# BeagleBone_Black_Wireless.net
KiCad netlist of a schematic drawn in EAGLE
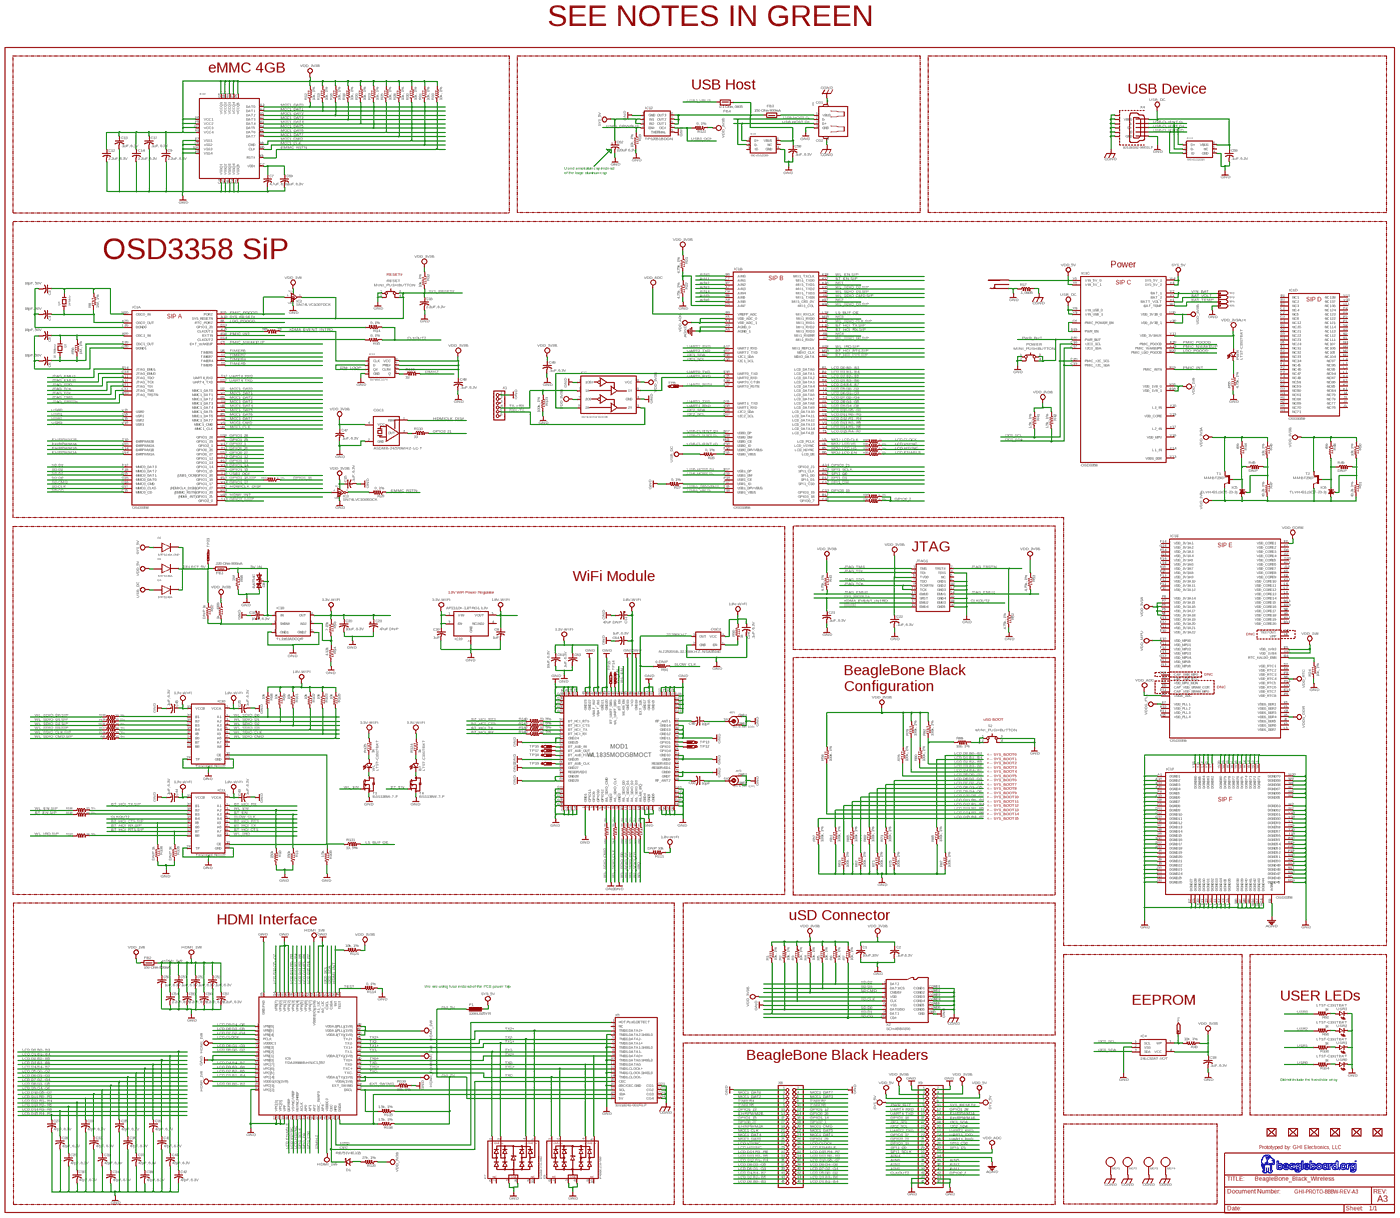
[diagram p0: schematic, sheet 1, overview]
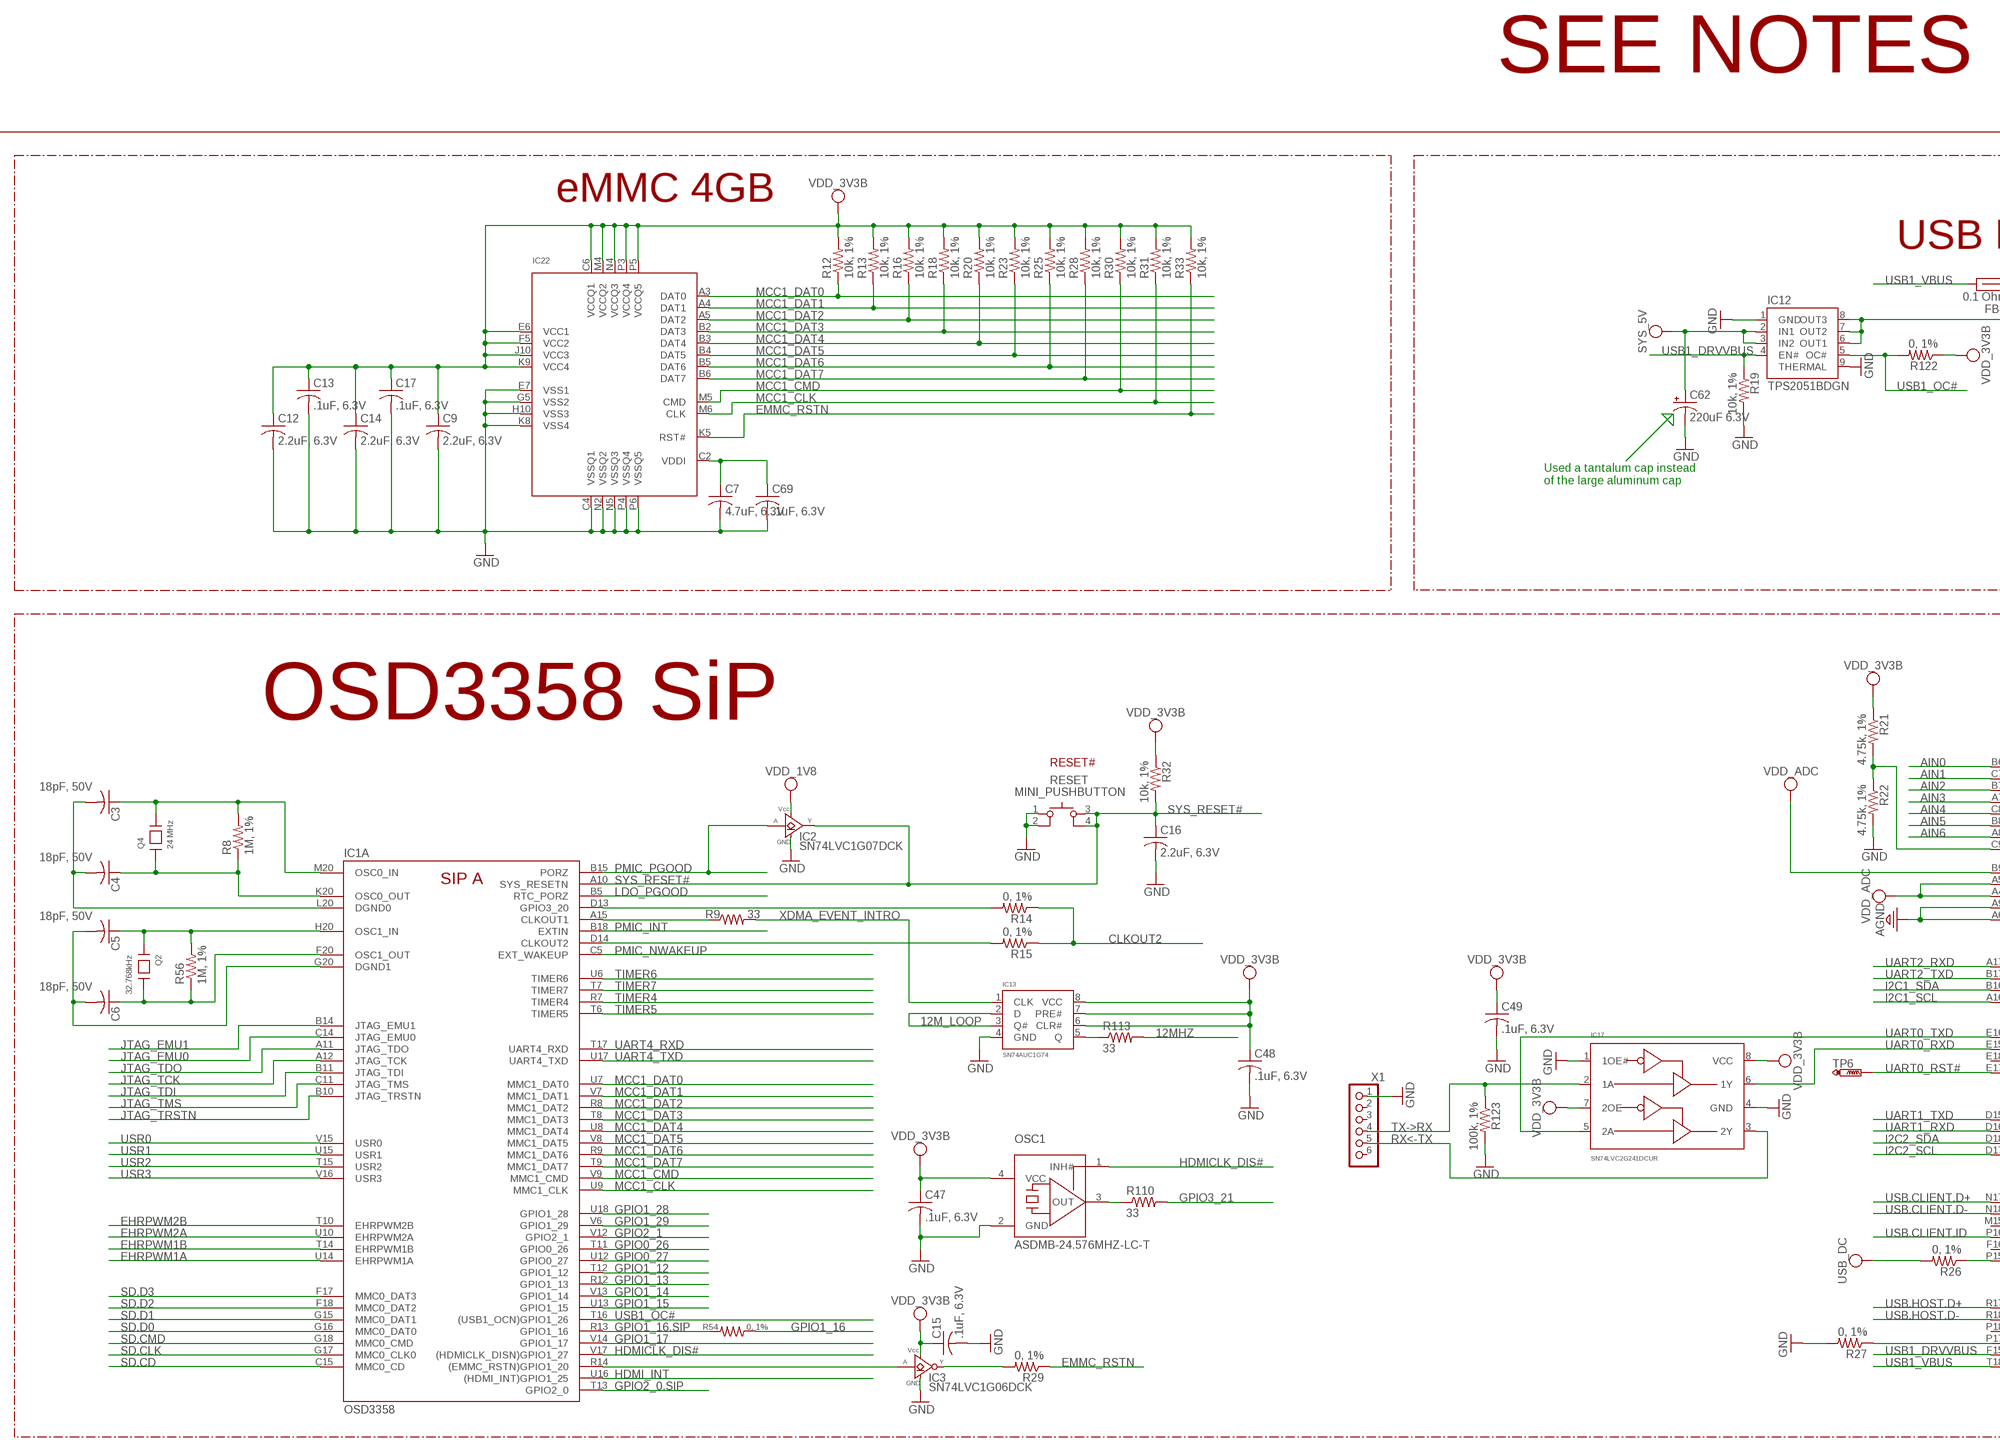
[diagram p1: schematic, sheet 1, part 1 of 4]
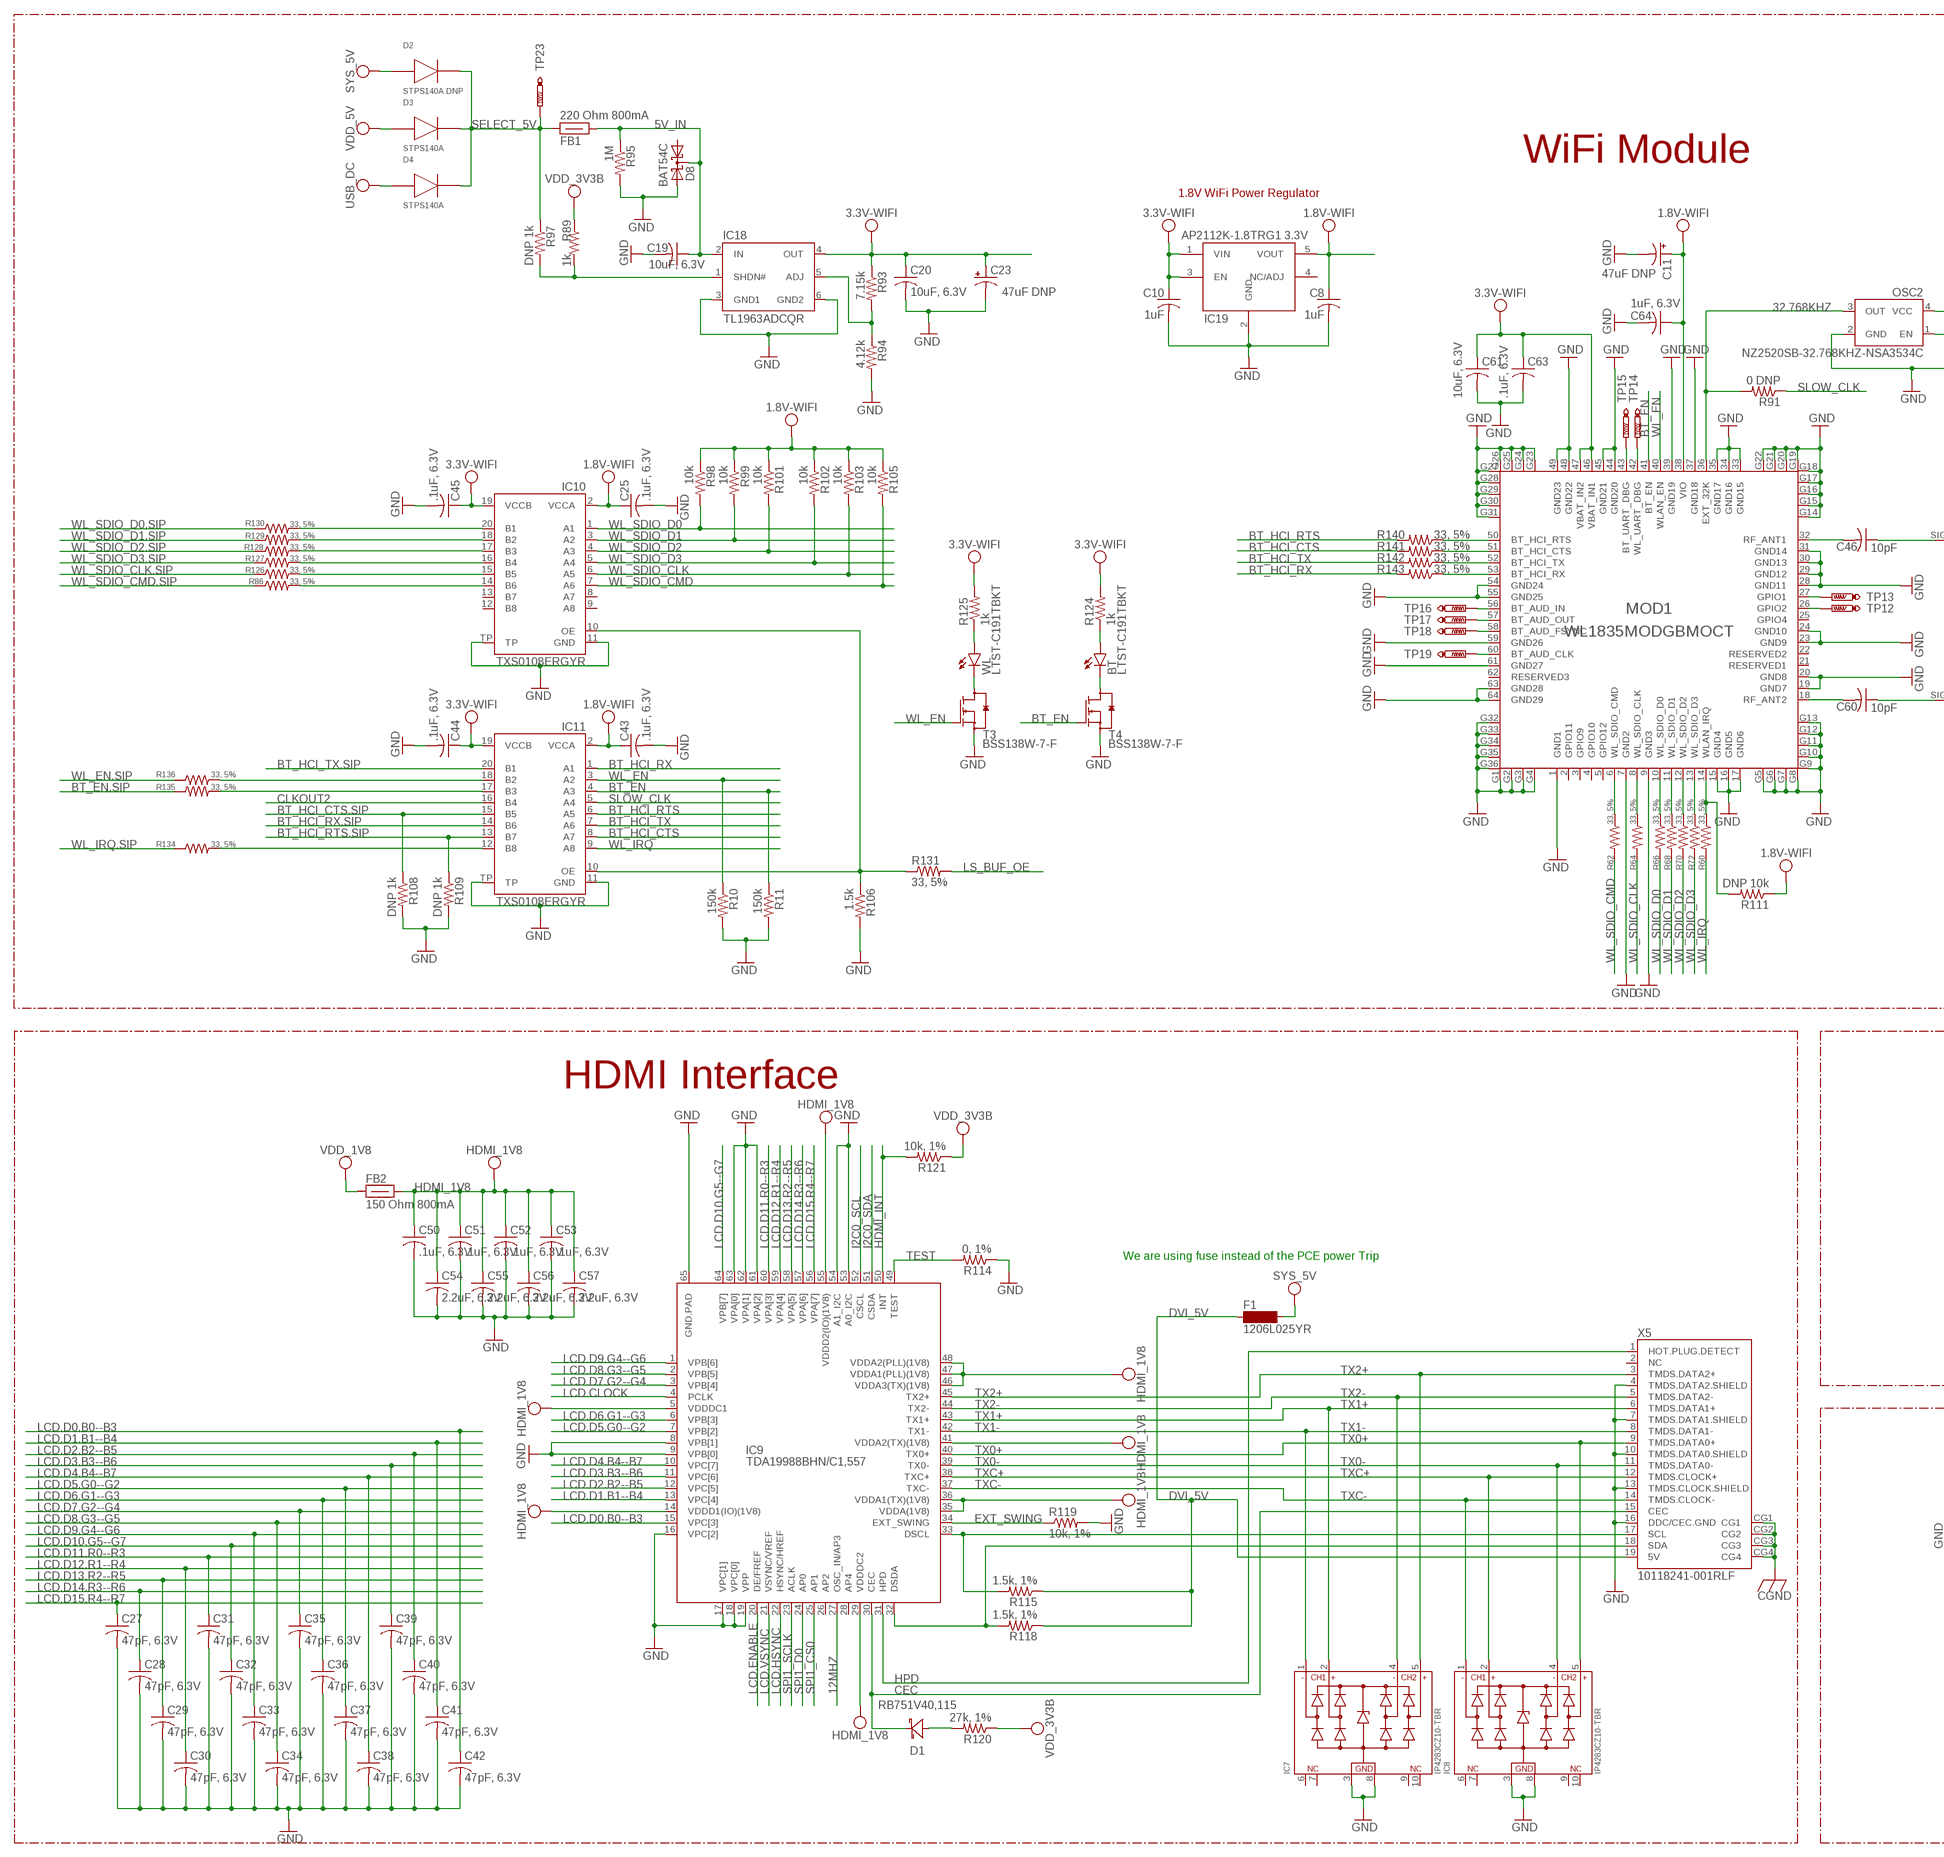
[diagram p2: schematic, sheet 1, part 2 of 4]
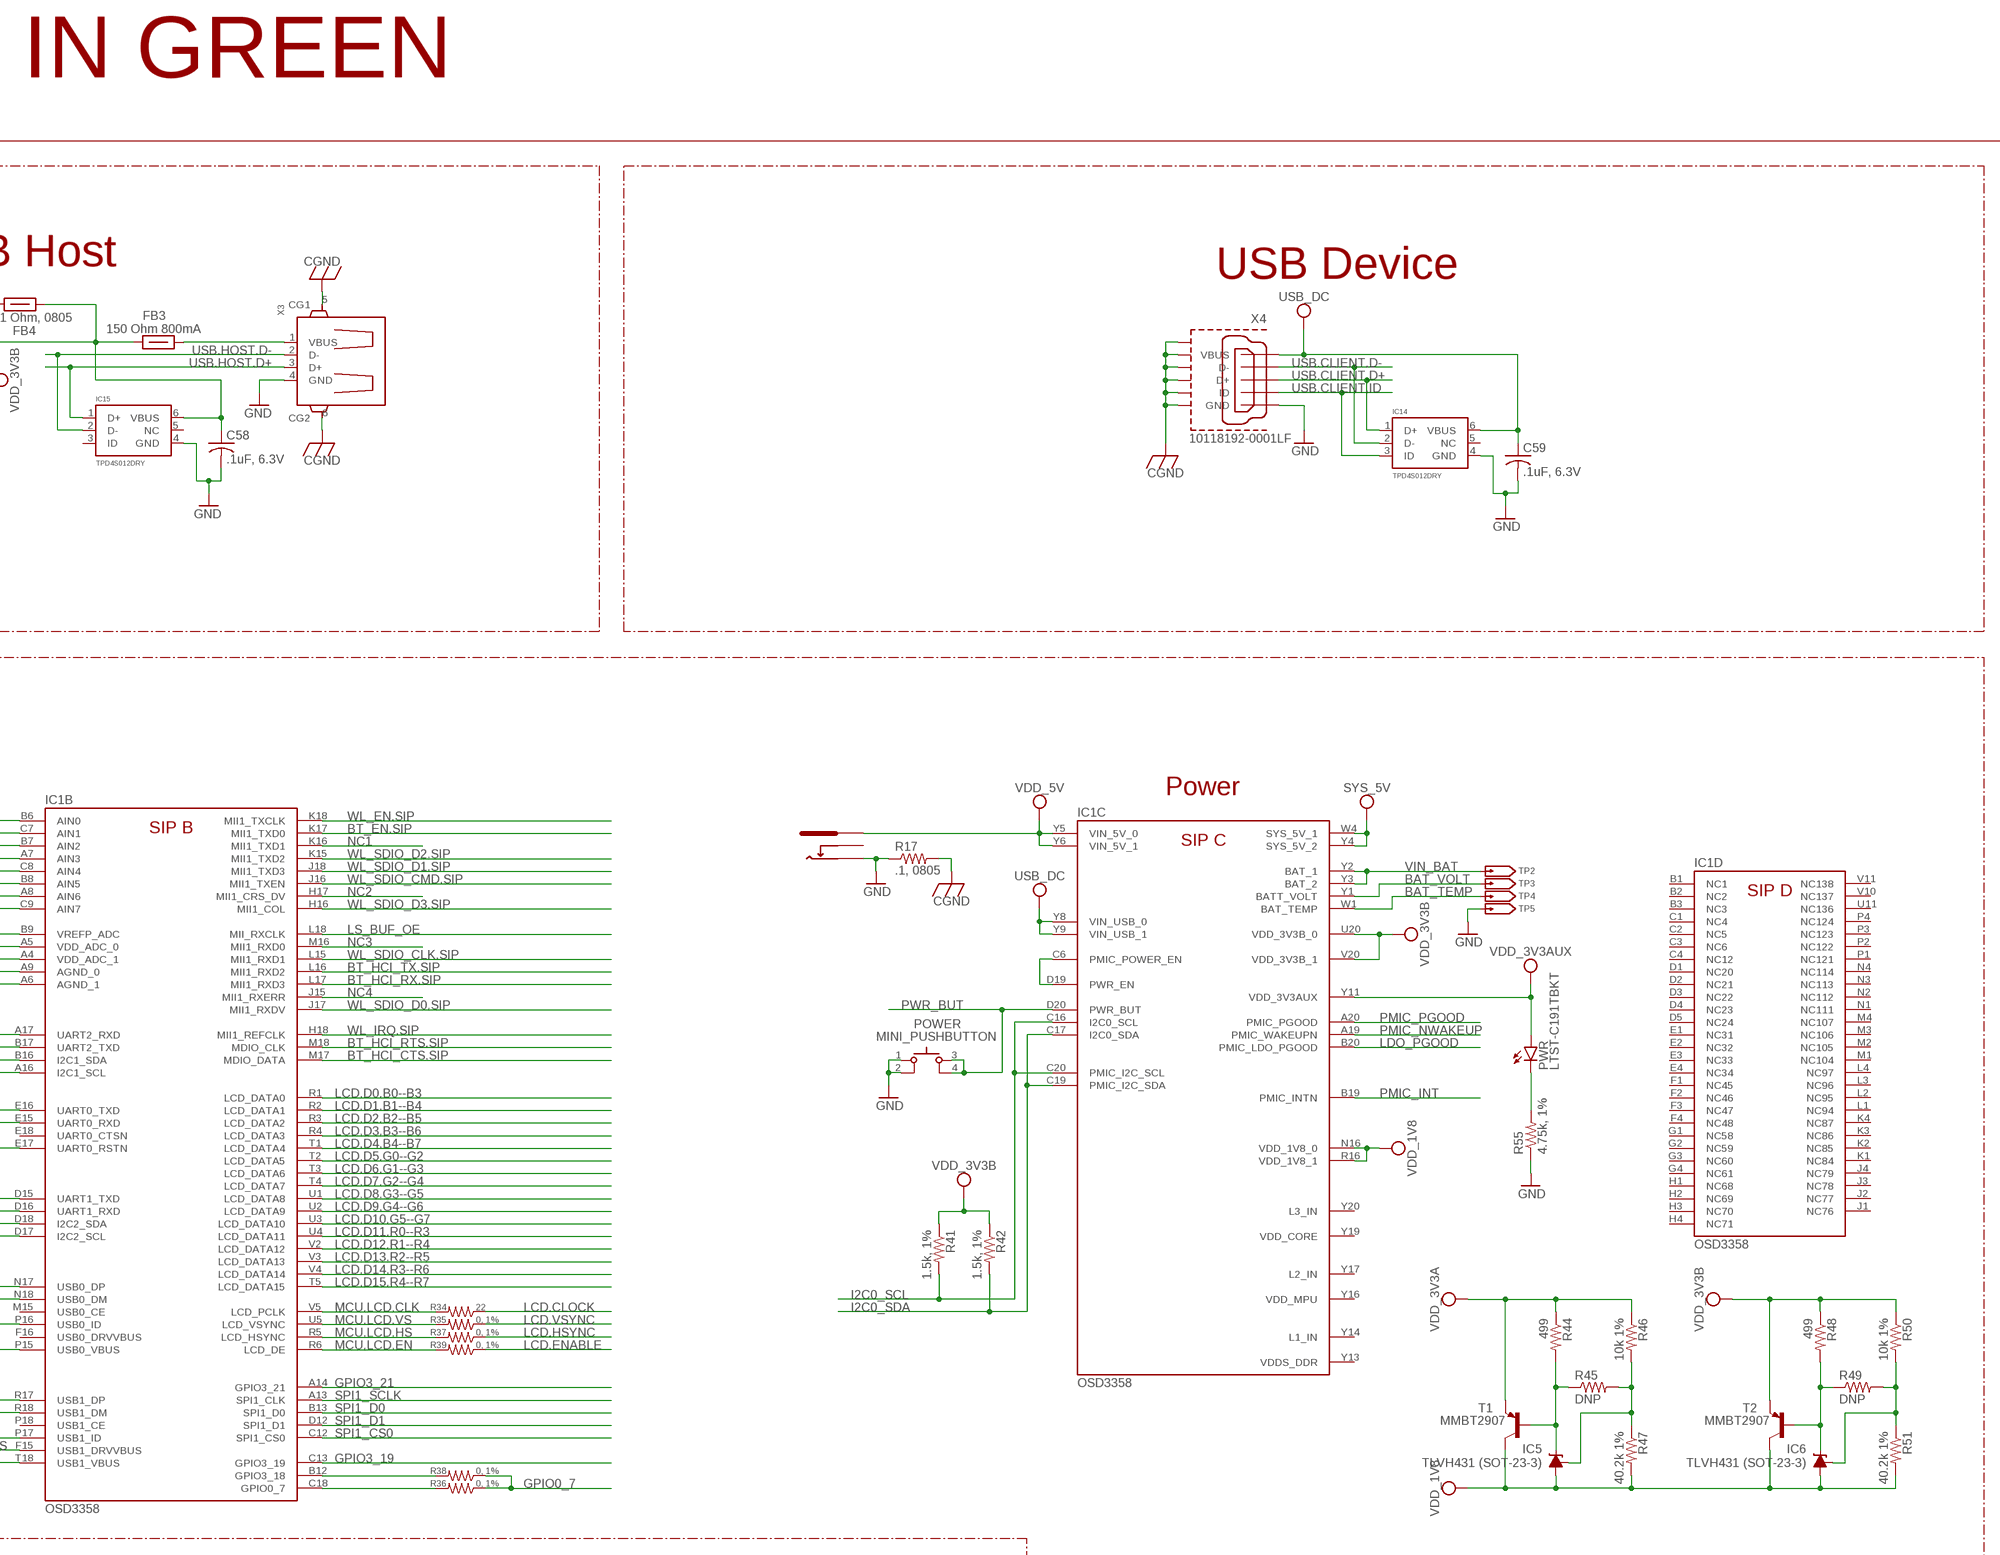
[diagram p3: schematic, sheet 1, part 3 of 4]
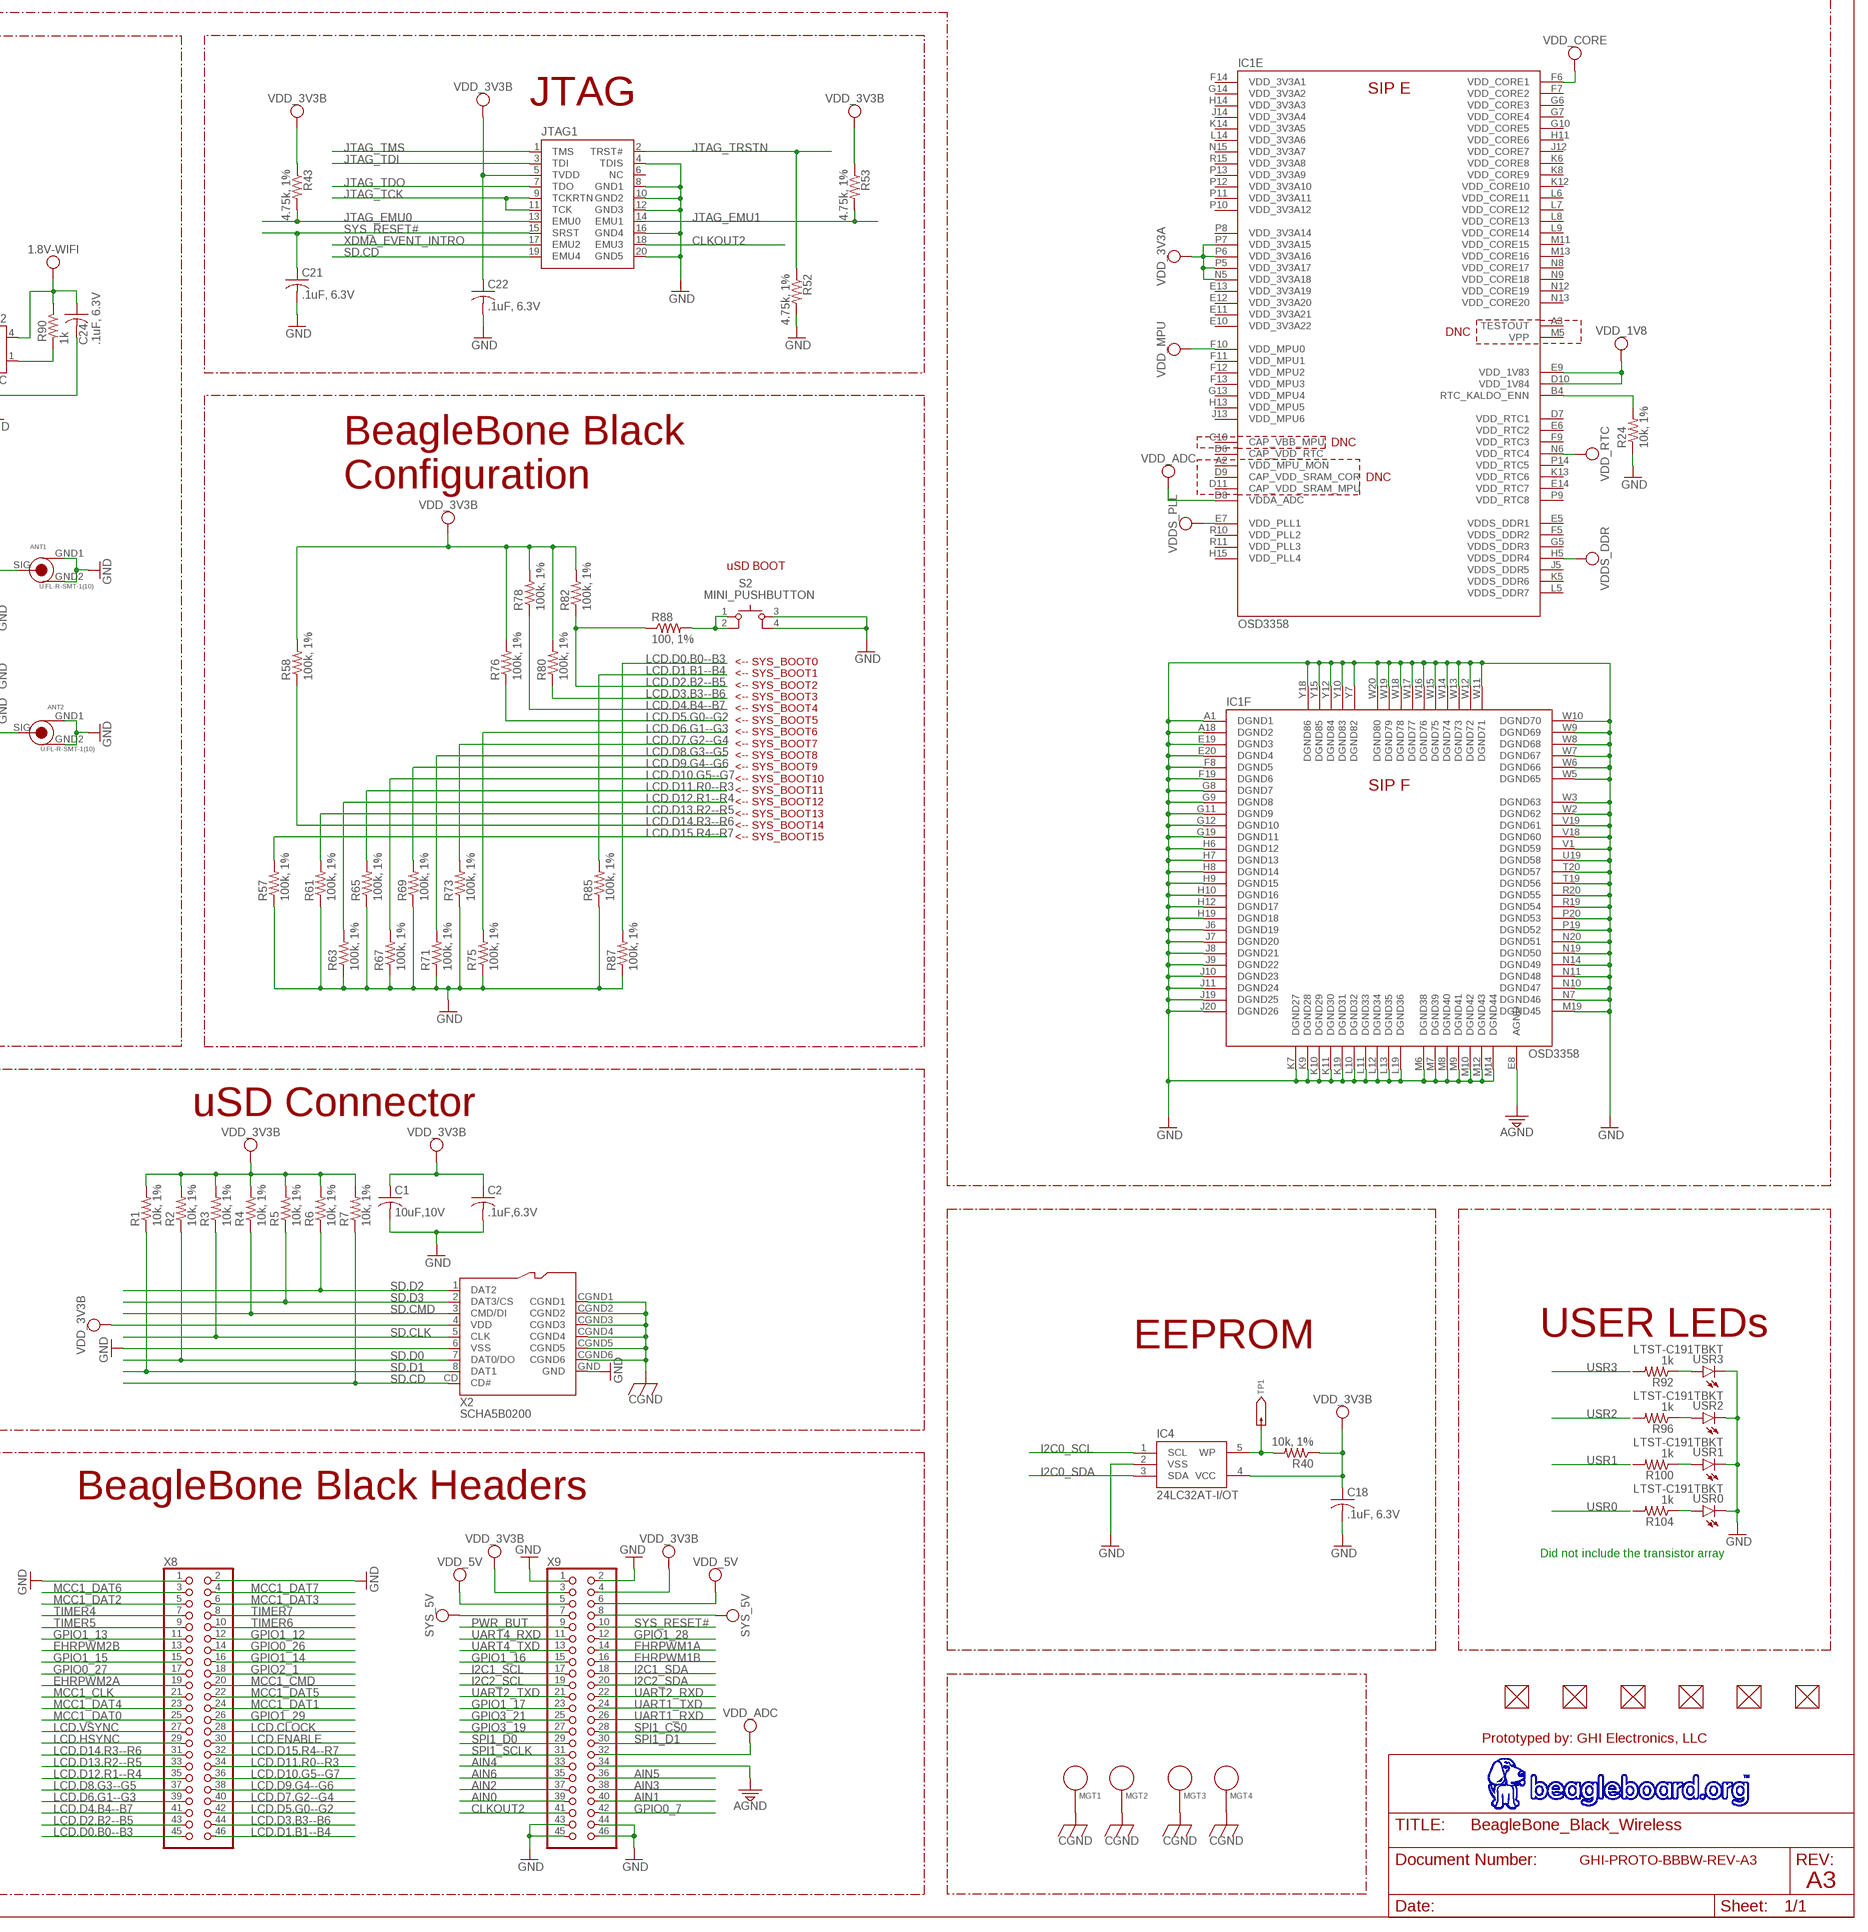
[diagram p4: schematic, sheet 1, part 4 of 4]

(export (version "E")
  (design (tool "Eeschema 10.0.6"))
  (components
    (comp (ref "ANT1")
      (value "U.FL-R-SMT-1(10)")
      (footprint "eagle-import:U.FL-R-SMT-1")
      (libsource (lib "eagle-import") (part "U.FL-R-SMT-1"))
    )
    (comp (ref "ANT2")
      (value "U.FL-R-SMT-1(10)")
      (footprint "eagle-import:U.FL-R-SMT-1")
      (libsource (lib "eagle-import") (part "U.FL-R-SMT-1"))
    )
    (comp (ref "BT")
      (value "LTST-C191TBKT")
      (footprint "eagle-import:0603-LED")
      (libsource (lib "eagle-import") (part "LED-(INCH)-0603"))
    )
    (comp (ref "C1")
      (value "10uF,10V")
      (footprint "eagle-import:C0603K")
      (libsource (lib "eagle-import") (part "C-USC0603K"))
    )
    (comp (ref "C2")
      (value ".1uF,6.3V")
      (footprint "eagle-import:C0402K")
      (libsource (lib "eagle-import") (part "C-USC0402K"))
    )
    (comp (ref "C3")
      (value "18pF, 50V")
      (footprint "eagle-import:C0402K")
      (libsource (lib "eagle-import") (part "C-USC0402K"))
    )
    (comp (ref "C4")
      (value "18pF, 50V")
      (footprint "eagle-import:C0402K")
      (libsource (lib "eagle-import") (part "C-USC0402K"))
    )
    (comp (ref "C5")
      (value "18pF, 50V")
      (footprint "eagle-import:C0402K")
      (libsource (lib "eagle-import") (part "C-USC0402K"))
    )
    (comp (ref "C6")
      (value "18pF, 50V")
      (footprint "eagle-import:C0402K")
      (libsource (lib "eagle-import") (part "C-USC0402K"))
    )
    (comp (ref "C7")
      (value "4.7uF, 6.3V")
      (footprint "eagle-import:C0805K")
      (libsource (lib "eagle-import") (part "C-USC0805K"))
    )
    (comp (ref "C8")
      (value "1uF")
      (footprint "eagle-import:C0402K")
      (libsource (lib "eagle-import") (part "C-USC0402K"))
    )
    (comp (ref "C9")
      (value "2.2uF, 6.3V")
      (footprint "eagle-import:C0805K")
      (libsource (lib "eagle-import") (part "C-USC0805K"))
    )
    (comp (ref "C10")
      (value "1uF")
      (footprint "eagle-import:C0402K")
      (libsource (lib "eagle-import") (part "C-USC0402K"))
    )
    (comp (ref "C11")
      (value "47uF DNP")
      (footprint "eagle-import:CT3528")
      (libsource (lib "eagle-import") (part "CPOL-USCT3528"))
    )
    (comp (ref "C12")
      (value "2.2uF, 6.3V")
      (footprint "eagle-import:C0805K")
      (libsource (lib "eagle-import") (part "C-USC0805K"))
    )
    (comp (ref "C13")
      (value ".1uF, 6.3V")
      (footprint "eagle-import:C0402K")
      (libsource (lib "eagle-import") (part "C-USC0402K"))
    )
    (comp (ref "C14")
      (value "2.2uF, 6.3V")
      (footprint "eagle-import:C0805K")
      (libsource (lib "eagle-import") (part "C-USC0805K"))
    )
    (comp (ref "C15")
      (value ".1uF, 6.3V")
      (footprint "eagle-import:C0402K")
      (libsource (lib "eagle-import") (part "C-USC0402K"))
    )
    (comp (ref "C16")
      (value "2.2uF, 6.3V")
      (footprint "eagle-import:C0603K")
      (libsource (lib "eagle-import") (part "C-USC0603K"))
    )
    (comp (ref "C17")
      (value ".1uF, 6.3V")
      (footprint "eagle-import:C0402K")
      (libsource (lib "eagle-import") (part "C-USC0402K"))
    )
    (comp (ref "C18")
      (value ".1uF, 6.3V")
      (footprint "eagle-import:C0402K")
      (libsource (lib "eagle-import") (part "C-USC0402K"))
    )
    (comp (ref "C19")
      (value "10uF, 6.3V")
      (footprint "eagle-import:C0603K")
      (libsource (lib "eagle-import") (part "C-USC0603K"))
    )
    (comp (ref "C20")
      (value "10uF, 6.3V")
      (footprint "eagle-import:C0603K")
      (libsource (lib "eagle-import") (part "C-USC0603K"))
    )
    (comp (ref "C21")
      (value ".1uF, 6.3V")
      (footprint "eagle-import:C0402K")
      (libsource (lib "eagle-import") (part "C-USC0402K"))
    )
    (comp (ref "C22")
      (value ".1uF, 6.3V")
      (footprint "eagle-import:C0402K")
      (libsource (lib "eagle-import") (part "C-USC0402K"))
    )
    (comp (ref "C23")
      (value "47uF DNP")
      (footprint "eagle-import:CT3528")
      (libsource (lib "eagle-import") (part "CPOL-USCT3528"))
    )
    (comp (ref "C24")
      (value ".1uF, 6.3V")
      (footprint "eagle-import:C0402K")
      (libsource (lib "eagle-import") (part "C-USC0402K"))
    )
    (comp (ref "C25")
      (value ".1uF, 6.3V")
      (footprint "eagle-import:C0402K")
      (libsource (lib "eagle-import") (part "C-USC0402K"))
    )
    (comp (ref "C27")
      (value "47pF, 6.3V")
      (footprint "eagle-import:C0402K")
      (libsource (lib "eagle-import") (part "C-USC0402K"))
    )
    (comp (ref "C28")
      (value "47pF, 6.3V")
      (footprint "eagle-import:C0402K")
      (libsource (lib "eagle-import") (part "C-USC0402K"))
    )
    (comp (ref "C29")
      (value "47pF, 6.3V")
      (footprint "eagle-import:C0402K")
      (libsource (lib "eagle-import") (part "C-USC0402K"))
    )
    (comp (ref "C30")
      (value "47pF, 6.3V")
      (footprint "eagle-import:C0402K")
      (libsource (lib "eagle-import") (part "C-USC0402K"))
    )
    (comp (ref "C31")
      (value "47pF, 6.3V")
      (footprint "eagle-import:C0402K")
      (libsource (lib "eagle-import") (part "C-USC0402K"))
    )
    (comp (ref "C32")
      (value "47pF, 6.3V")
      (footprint "eagle-import:C0402K")
      (libsource (lib "eagle-import") (part "C-USC0402K"))
    )
    (comp (ref "C33")
      (value "47pF, 6.3V")
      (footprint "eagle-import:C0402K")
      (libsource (lib "eagle-import") (part "C-USC0402K"))
    )
    (comp (ref "C34")
      (value "47pF, 6.3V")
      (footprint "eagle-import:C0402K")
      (libsource (lib "eagle-import") (part "C-USC0402K"))
    )
    (comp (ref "C35")
      (value "47pF, 6.3V")
      (footprint "eagle-import:C0402K")
      (libsource (lib "eagle-import") (part "C-USC0402K"))
    )
    (comp (ref "C36")
      (value "47pF, 6.3V")
      (footprint "eagle-import:C0402K")
      (libsource (lib "eagle-import") (part "C-USC0402K"))
    )
    (comp (ref "C37")
      (value "47pF, 6.3V")
      (footprint "eagle-import:C0402K")
      (libsource (lib "eagle-import") (part "C-USC0402K"))
    )
    (comp (ref "C38")
      (value "47pF, 6.3V")
      (footprint "eagle-import:C0402K")
      (libsource (lib "eagle-import") (part "C-USC0402K"))
    )
    (comp (ref "C39")
      (value "47pF, 6.3V")
      (footprint "eagle-import:C0402K")
      (libsource (lib "eagle-import") (part "C-USC0402K"))
    )
    (comp (ref "C40")
      (value "47pF, 6.3V")
      (footprint "eagle-import:C0402K")
      (libsource (lib "eagle-import") (part "C-USC0402K"))
    )
    (comp (ref "C41")
      (value "47pF, 6.3V")
      (footprint "eagle-import:C0402K")
      (libsource (lib "eagle-import") (part "C-USC0402K"))
    )
    (comp (ref "C42")
      (value "47pF, 6.3V")
      (footprint "eagle-import:C0402K")
      (libsource (lib "eagle-import") (part "C-USC0402K"))
    )
    (comp (ref "C43")
      (value ".1uF, 6.3V")
      (footprint "eagle-import:C0402K")
      (libsource (lib "eagle-import") (part "C-USC0402K"))
    )
    (comp (ref "C44")
      (value ".1uF, 6.3V")
      (footprint "eagle-import:C0402K")
      (libsource (lib "eagle-import") (part "C-USC0402K"))
    )
    (comp (ref "C45")
      (value ".1uF, 6.3V")
      (footprint "eagle-import:C0402K")
      (libsource (lib "eagle-import") (part "C-USC0402K"))
    )
    (comp (ref "C46")
      (value "10pF")
      (footprint "eagle-import:C0402K")
      (libsource (lib "eagle-import") (part "C-USC0402K"))
    )
    (comp (ref "C47")
      (value ".1uF, 6.3V")
      (footprint "eagle-import:C0402K")
      (libsource (lib "eagle-import") (part "C-USC0402K"))
    )
    (comp (ref "C48")
      (value ".1uF, 6.3V")
      (footprint "eagle-import:C0402K")
      (libsource (lib "eagle-import") (part "C-USC0402K"))
    )
    (comp (ref "C49")
      (value ".1uF, 6.3V")
      (footprint "eagle-import:C0402K")
      (libsource (lib "eagle-import") (part "C-USC0402K"))
    )
    (comp (ref "C50")
      (value ".1uF, 6.3V")
      (footprint "eagle-import:C0402K")
      (libsource (lib "eagle-import") (part "C-USC0402K"))
    )
    (comp (ref "C51")
      (value ".1uF, 6.3V")
      (footprint "eagle-import:C0402K")
      (libsource (lib "eagle-import") (part "C-USC0402K"))
    )
    (comp (ref "C52")
      (value ".1uF, 6.3V")
      (footprint "eagle-import:C0402K")
      (libsource (lib "eagle-import") (part "C-USC0402K"))
    )
    (comp (ref "C53")
      (value ".1uF, 6.3V")
      (footprint "eagle-import:C0402K")
      (libsource (lib "eagle-import") (part "C-USC0402K"))
    )
    (comp (ref "C54")
      (value "2.2uF, 6.3V")
      (footprint "eagle-import:C0603K")
      (libsource (lib "eagle-import") (part "C-USC0603K"))
    )
    (comp (ref "C55")
      (value "2.2uF, 6.3V")
      (footprint "eagle-import:C0603K")
      (libsource (lib "eagle-import") (part "C-USC0603K"))
    )
    (comp (ref "C56")
      (value "2.2uF, 6.3V")
      (footprint "eagle-import:C0603K")
      (libsource (lib "eagle-import") (part "C-USC0603K"))
    )
    (comp (ref "C57")
      (value "2.2uF, 6.3V")
      (footprint "eagle-import:C0603K")
      (libsource (lib "eagle-import") (part "C-USC0603K"))
    )
    (comp (ref "C58")
      (value ".1uF, 6.3V")
      (footprint "eagle-import:C0402K")
      (libsource (lib "eagle-import") (part "C-USC0402K"))
    )
    (comp (ref "C59")
      (value ".1uF, 6.3V")
      (footprint "eagle-import:C0402K")
      (libsource (lib "eagle-import") (part "C-USC0402K"))
    )
    (comp (ref "C60")
      (value "10pF")
      (footprint "eagle-import:C0402K")
      (libsource (lib "eagle-import") (part "C-USC0402K"))
    )
    (comp (ref "C61")
      (value "10uF, 6.3V")
      (footprint "eagle-import:C0603K")
      (libsource (lib "eagle-import") (part "C-USC0603K"))
    )
    (comp (ref "C62")
      (value "220uF 6.3V")
      (footprint "eagle-import:D_7343-31W")
      (libsource (lib "eagle-import") (part "CPOL-USD/7343-31W"))
    )
    (comp (ref "C63")
      (value ".1uF, 6.3V")
      (footprint "eagle-import:C0402K")
      (libsource (lib "eagle-import") (part "C-USC0402K"))
    )
    (comp (ref "C64")
      (value "1uF, 6.3V")
      (footprint "eagle-import:C0402K")
      (libsource (lib "eagle-import") (part "C-USC0402K"))
    )
    (comp (ref "C69")
      (value ".1uF, 6.3V")
      (footprint "eagle-import:C0402K")
      (libsource (lib "eagle-import") (part "C-USC0402K"))
    )
    (comp (ref "D1")
      (value "RB751V40,115")
      (footprint "eagle-import:SOD323(NXP)REFLOW")
      (libsource (lib "eagle-import") (part "DIODE-SCHOTTKY-(NXP)-SOD323-(REFLOW)"))
    )
    (comp (ref "D2")
      (value "STPS140A DNP")
      (footprint "eagle-import:DIODE_SMA")
      (libsource (lib "eagle-import") (part "DIODE_SMA"))
    )
    (comp (ref "D3")
      (value "STPS140A")
      (footprint "eagle-import:DIODE_SMA")
      (libsource (lib "eagle-import") (part "DIODE_SMA"))
    )
    (comp (ref "D4")
      (value "STPS140A")
      (footprint "eagle-import:DIODE_SMA")
      (libsource (lib "eagle-import") (part "DIODE_SMA"))
    )
    (comp (ref "D8")
      (value "BAT54C")
      (footprint "eagle-import:SOT23")
      (libsource (lib "eagle-import") (part "BAT54C"))
    )
    (comp (ref "F1")
      (value "1206L025YR")
      (footprint "eagle-import:SM-1206")
      (libsource (lib "eagle-import") (part "SM-1206"))
    )
    (comp (ref "FB1")
      (value "220 Ohm 800mA")
      (footprint "eagle-import:0805-RESISTOR")
      (libsource (lib "eagle-import") (part "FB-(INCH)-0805"))
    )
    (comp (ref "FB2")
      (value "150 Ohm 800mA")
      (footprint "eagle-import:0805-RESISTOR")
      (libsource (lib "eagle-import") (part "FB-(INCH)-0805"))
    )
    (comp (ref "FB3")
      (value "150 Ohm 800mA")
      (footprint "eagle-import:0805-RESISTOR")
      (libsource (lib "eagle-import") (part "FB-(INCH)-0805"))
    )
    (comp (ref "FB4")
      (value "0.1 Ohm, 0805")
      (footprint "eagle-import:0805-RESISTOR")
      (libsource (lib "eagle-import") (part "FB-(INCH)-0805"))
    )
    (comp (ref "FUD1")
      (value "FIDUCIAL")
      (footprint "eagle-import:FIDUCIAL_40MIL")
      (libsource (lib "eagle-import") (part "FIDUCIAL"))
    )
    (comp (ref "FUD2")
      (value "FIDUCIAL")
      (footprint "eagle-import:FIDUCIAL_40MIL")
      (libsource (lib "eagle-import") (part "FIDUCIAL"))
    )
    (comp (ref "FUD3")
      (value "FIDUCIAL")
      (footprint "eagle-import:FIDUCIAL_40MIL")
      (libsource (lib "eagle-import") (part "FIDUCIAL"))
    )
    (comp (ref "FUD4")
      (value "FIDUCIAL")
      (footprint "eagle-import:FIDUCIAL_40MIL")
      (libsource (lib "eagle-import") (part "FIDUCIAL"))
    )
    (comp (ref "FUD5")
      (value "FIDUCIAL")
      (footprint "eagle-import:FIDUCIAL_40MIL")
      (libsource (lib "eagle-import") (part "FIDUCIAL"))
    )
    (comp (ref "FUD6")
      (value "FIDUCIAL")
      (footprint "eagle-import:FIDUCIAL_40MIL")
      (libsource (lib "eagle-import") (part "FIDUCIAL"))
    )
    (comp (ref "IC1")
      (value "OSD3358")
      (footprint "eagle-import:OSD3358")
      (libsource (lib "eagle-import") (part "SIP1000"))
    )
    (comp (ref "IC2")
      (value "SN74LVC1G07DCK")
      (footprint "eagle-import:SC70(TI-DCK)")
      (libsource (lib "eagle-import") (part "SN74LVC1G07DCK"))
    )
    (comp (ref "IC3")
      (value "SN74LVC1G06DCK")
      (footprint "eagle-import:SC70(TI-DCK)")
      (libsource (lib "eagle-import") (part "SN74LVC1G06DCK"))
    )
    (comp (ref "IC4")
      (value "24LC32AT-I/OT")
      (footprint "eagle-import:SOT23-5(MICROCHIP)")
      (libsource (lib "eagle-import") (part "24LC32A{dblquote}"))
    )
    (comp (ref "IC5")
      (value "TLVH431 (SOT-23-3)")
      (footprint "eagle-import:DBZ_R-PDSO-G3")
      (fields (field (name "MF") "TEXAS INSTRUMENT CONNECTORS") (field (name "MPN") "LM4041DIDBZR"))
      (libsource (lib "eagle-import") (part "LM4041IDBZD"))
    )
    (comp (ref "IC6")
      (value "TLVH431 (SOT-23-3)")
      (footprint "eagle-import:DBZ_R-PDSO-G3")
      (fields (field (name "MF") "TEXAS INSTRUMENT CONNECTORS") (field (name "MPN") "LM4041DIDBZR"))
      (libsource (lib "eagle-import") (part "LM4041IDBZD"))
    )
    (comp (ref "IC7")
      (value "IP4283CZ10-TBR")
      (footprint "eagle-import:SOT1176-1(NXP)")
      (libsource (lib "eagle-import") (part "IP4283CZ10IP4283CZ10-TBR"))
    )
    (comp (ref "IC8")
      (value "IP4283CZ10-TBR")
      (footprint "eagle-import:SOT1176-1(NXP)")
      (libsource (lib "eagle-import") (part "IP4283CZ10IP4283CZ10-TBR"))
    )
    (comp (ref "IC9")
      (value "TDA19988BHN/C1,557")
      (footprint "eagle-import:SOT804-4(NXP)")
      (libsource (lib "eagle-import") (part "TDA19988BHN/C1"))
    )
    (comp (ref "IC10")
      (value "TXS0108ERGYR")
      (footprint "eagle-import:R-PVQFN-N20(TI)")
      (libsource (lib "eagle-import") (part "TXS0108ERGYR"))
    )
    (comp (ref "IC11")
      (value "TXS0108ERGYR")
      (footprint "eagle-import:R-PVQFN-N20(TI)")
      (libsource (lib "eagle-import") (part "TXS0108ERGYR"))
    )
    (comp (ref "IC12")
      (value "TPS2051BDGN")
      (footprint "eagle-import:MSOP-POWER.PAD-8(TI)")
      (libsource (lib "eagle-import") (part "TPS2051B"))
    )
    (comp (ref "IC13")
      (value "SN74AUC1G74")
      (footprint "eagle-import:SM8-8(TI)")
      (libsource (lib "eagle-import") (part "SN74AUC1G74"))
    )
    (comp (ref "IC14")
      (value "TPD4S012DRY")
      (footprint "eagle-import:SON-6(TI)-DRY")
      (libsource (lib "eagle-import") (part "TPD4S012DRYR"))
    )
    (comp (ref "IC15")
      (value "TPD4S012DRY")
      (footprint "eagle-import:SON-6(TI)-DRY")
      (libsource (lib "eagle-import") (part "TPD4S012DRYR"))
    )
    (comp (ref "IC17")
      (value "SN74LVC2G241DCUR")
      (footprint "eagle-import:VSSOP8(TI)")
      (libsource (lib "eagle-import") (part "SN74LVC2G241DCUR"))
    )
    (comp (ref "IC18")
      (value "TL1963ADCQR")
      (footprint "eagle-import:SOT-223(DCQ_R-PDSO-G6_TI)")
      (libsource (lib "eagle-import") (part "TL1963A"))
    )
    (comp (ref "IC19")
      (value "AP2112K-1.8TRG1 3.3V")
      (footprint "eagle-import:SOT23-5")
      (libsource (lib "eagle-import") (part "5PIN_REG"))
    )
    (comp (ref "IC22")
      (value "EMMC04G-S100-B08U")
      (footprint "eagle-import:MICRON_EMMC_153")
      (libsource (lib "eagle-import") (part "EMMC04G-S100-B08U"))
    )
    (comp (ref "JTAG1")
      (value "JTAG")
      (footprint "eagle-import:JTAG")
      (libsource (lib "eagle-import") (part "JTAG"))
    )
    (comp (ref "MGT1")
      (value "MOUNTING_HOLE")
      (footprint "eagle-import:MOUNTING_HOLE")
      (libsource (lib "eagle-import") (part "MOUNTING_HOLE"))
    )
    (comp (ref "MGT2")
      (value "MOUNTING_HOLE")
      (footprint "eagle-import:MOUNTING_HOLE")
      (libsource (lib "eagle-import") (part "MOUNTING_HOLE"))
    )
    (comp (ref "MGT3")
      (value "MOUNTING_HOLE")
      (footprint "eagle-import:MOUNTING_HOLE")
      (libsource (lib "eagle-import") (part "MOUNTING_HOLE"))
    )
    (comp (ref "MGT4")
      (value "MOUNTING_HOLE")
      (footprint "eagle-import:MOUNTING_HOLE")
      (libsource (lib "eagle-import") (part "MOUNTING_HOLE"))
    )
    (comp (ref "MOD1")
      (value "WL1835MODGBMOCT")
      (footprint "eagle-import:MOC-100(TI)")
      (libsource (lib "eagle-import") (part "WL1835MOD"))
    )
    (comp (ref "OSC1")
      (value "ASDMB-24.576MHZ-LC-T")
      (footprint "eagle-import:OSCILLATOR-2.5X2.0-BBB")
      (libsource (lib "eagle-import") (part "OSC-2.5X2.0"))
    )
    (comp (ref "OSC2")
      (value "NZ2520SB-32.768KHZ-NSA3534C")
      (footprint "eagle-import:NZ2520S")
      (libsource (lib "eagle-import") (part "OSCILLATOR"))
    )
    (comp (ref "POWER")
      (value "MINI_PUSHBUTTON")
      (footprint "eagle-import:MINI_PUSHBUTTON")
      (libsource (lib "eagle-import") (part "MINI_PUSHBUTTON"))
    )
    (comp (ref "PWR")
      (value "LTST-C191TBKT")
      (footprint "eagle-import:0603-LED")
      (libsource (lib "eagle-import") (part "LED-(INCH)-0603"))
    )
    (comp (ref "Q2")
      (value "32.768kHz")
      (footprint "eagle-import:CRYSTAL_3.2X1.5")
      (libsource (lib "eagle-import") (part "CRYSTAL_3.2X1.5"))
    )
    (comp (ref "Q4")
      (value "24 MHz")
      (footprint "eagle-import:CRYSTAL_5X3.2MM")
      (libsource (lib "eagle-import") (part "CRYSTAL_5X3.2MM"))
    )
    (comp (ref "R1")
      (value "10k, 1%")
      (footprint "eagle-import:R0402")
      (libsource (lib "eagle-import") (part "R-US_R0402"))
    )
    (comp (ref "R2")
      (value "10k, 1%")
      (footprint "eagle-import:R0402")
      (libsource (lib "eagle-import") (part "R-US_R0402"))
    )
    (comp (ref "R3")
      (value "10k, 1%")
      (footprint "eagle-import:R0402")
      (libsource (lib "eagle-import") (part "R-US_R0402"))
    )
    (comp (ref "R4")
      (value "10k, 1%")
      (footprint "eagle-import:R0402")
      (libsource (lib "eagle-import") (part "R-US_R0402"))
    )
    (comp (ref "R5")
      (value "10k, 1%")
      (footprint "eagle-import:R0402")
      (libsource (lib "eagle-import") (part "R-US_R0402"))
    )
    (comp (ref "R6")
      (value "10k, 1%")
      (footprint "eagle-import:R0402")
      (libsource (lib "eagle-import") (part "R-US_R0402"))
    )
    (comp (ref "R7")
      (value "10k, 1%")
      (footprint "eagle-import:R0402")
      (libsource (lib "eagle-import") (part "R-US_R0402"))
    )
    (comp (ref "R8")
      (value "1M, 1%")
      (footprint "eagle-import:R0402")
      (libsource (lib "eagle-import") (part "R-US_R0402"))
    )
    (comp (ref "R9")
      (value "33")
      (footprint "eagle-import:R0402")
      (libsource (lib "eagle-import") (part "R-US_R0402"))
    )
    (comp (ref "R10")
      (value "150k")
      (footprint "eagle-import:R0402")
      (libsource (lib "eagle-import") (part "R-US_R0402"))
    )
    (comp (ref "R11")
      (value "150k")
      (footprint "eagle-import:R0402")
      (libsource (lib "eagle-import") (part "R-US_R0402"))
    )
    (comp (ref "R12")
      (value "10k, 1%")
      (footprint "eagle-import:R0402")
      (libsource (lib "eagle-import") (part "R-US_R0402"))
    )
    (comp (ref "R13")
      (value "10k, 1%")
      (footprint "eagle-import:R0402")
      (libsource (lib "eagle-import") (part "R-US_R0402"))
    )
    (comp (ref "R14")
      (value "0, 1%")
      (footprint "eagle-import:R0402")
      (libsource (lib "eagle-import") (part "R-US_R0402"))
    )
    (comp (ref "R15")
      (value "0, 1%")
      (footprint "eagle-import:R0402")
      (libsource (lib "eagle-import") (part "R-US_R0402"))
    )
    (comp (ref "R16")
      (value "10k, 1%")
      (footprint "eagle-import:R0402")
      (libsource (lib "eagle-import") (part "R-US_R0402"))
    )
    (comp (ref "R17")
      (value ".1, 0805")
      (footprint "eagle-import:R0805")
      (libsource (lib "eagle-import") (part "R-US_R0805"))
    )
    (comp (ref "R18")
      (value "10k, 1%")
      (footprint "eagle-import:R0402")
      (libsource (lib "eagle-import") (part "R-US_R0402"))
    )
    (comp (ref "R19")
      (value "10k, 1%")
      (footprint "eagle-import:R0402")
      (libsource (lib "eagle-import") (part "R-US_R0402"))
    )
    (comp (ref "R20")
      (value "10k, 1%")
      (footprint "eagle-import:R0402")
      (libsource (lib "eagle-import") (part "R-US_R0402"))
    )
    (comp (ref "R21")
      (value "4.75k, 1%")
      (footprint "eagle-import:R0402")
      (libsource (lib "eagle-import") (part "R-US_R0402"))
    )
    (comp (ref "R22")
      (value "4.75k, 1%")
      (footprint "eagle-import:R0402")
      (libsource (lib "eagle-import") (part "R-US_R0402"))
    )
    (comp (ref "R23")
      (value "10k, 1%")
      (footprint "eagle-import:R0402")
      (libsource (lib "eagle-import") (part "R-US_R0402"))
    )
    (comp (ref "R24")
      (value "10k, 1%")
      (footprint "eagle-import:R0402")
      (libsource (lib "eagle-import") (part "R-US_R0402"))
    )
    (comp (ref "R25")
      (value "10k, 1%")
      (footprint "eagle-import:R0402")
      (libsource (lib "eagle-import") (part "R-US_R0402"))
    )
    (comp (ref "R26")
      (value "0, 1%")
      (footprint "eagle-import:R0402")
      (libsource (lib "eagle-import") (part "R-US_R0402"))
    )
    (comp (ref "R27")
      (value "0, 1%")
      (footprint "eagle-import:R0402")
      (libsource (lib "eagle-import") (part "R-US_R0402"))
    )
    (comp (ref "R28")
      (value "10k, 1%")
      (footprint "eagle-import:R0402")
      (libsource (lib "eagle-import") (part "R-US_R0402"))
    )
    (comp (ref "R29")
      (value "0, 1%")
      (footprint "eagle-import:R0402")
      (libsource (lib "eagle-import") (part "R-US_R0402"))
    )
    (comp (ref "R30")
      (value "10k, 1%")
      (footprint "eagle-import:R0402")
      (libsource (lib "eagle-import") (part "R-US_R0402"))
    )
    (comp (ref "R31")
      (value "10k, 1%")
      (footprint "eagle-import:R0402")
      (libsource (lib "eagle-import") (part "R-US_R0402"))
    )
    (comp (ref "R32")
      (value "10k, 1%")
      (footprint "eagle-import:R0402")
      (libsource (lib "eagle-import") (part "R-US_R0402"))
    )
    (comp (ref "R33")
      (value "10k, 1%")
      (footprint "eagle-import:R0402")
      (libsource (lib "eagle-import") (part "R-US_R0402"))
    )
    (comp (ref "R34")
      (value "22")
      (footprint "eagle-import:R0402")
      (libsource (lib "eagle-import") (part "R-US_R0402"))
    )
    (comp (ref "R35")
      (value "0, 1%")
      (footprint "eagle-import:R0402")
      (libsource (lib "eagle-import") (part "R-US_R0402"))
    )
    (comp (ref "R36")
      (value "0, 1%")
      (footprint "eagle-import:R0402")
      (libsource (lib "eagle-import") (part "R-US_R0402"))
    )
    (comp (ref "R37")
      (value "0, 1%")
      (footprint "eagle-import:R0402")
      (libsource (lib "eagle-import") (part "R-US_R0402"))
    )
    (comp (ref "R38")
      (value "0, 1%")
      (footprint "eagle-import:R0402")
      (libsource (lib "eagle-import") (part "R-US_R0402"))
    )
    (comp (ref "R39")
      (value "0, 1%")
      (footprint "eagle-import:R0402")
      (libsource (lib "eagle-import") (part "R-US_R0402"))
    )
    (comp (ref "R40")
      (value "10k, 1%")
      (footprint "eagle-import:R0402")
      (libsource (lib "eagle-import") (part "R-US_R0402"))
    )
    (comp (ref "R41")
      (value "1.5k, 1%")
      (footprint "eagle-import:R0402")
      (libsource (lib "eagle-import") (part "R-US_R0402"))
    )
    (comp (ref "R42")
      (value "1.5k, 1%")
      (footprint "eagle-import:R0402")
      (libsource (lib "eagle-import") (part "R-US_R0402"))
    )
    (comp (ref "R43")
      (value "4.75k, 1%")
      (footprint "eagle-import:R0402")
      (libsource (lib "eagle-import") (part "R-US_R0402"))
    )
    (comp (ref "R44")
      (value "499")
      (footprint "eagle-import:R0402")
      (libsource (lib "eagle-import") (part "R-US_R0402"))
    )
    (comp (ref "R45")
      (value "DNP")
      (footprint "eagle-import:R0402")
      (libsource (lib "eagle-import") (part "R-US_R0402"))
    )
    (comp (ref "R46")
      (value "10k 1%")
      (footprint "eagle-import:R0402")
      (libsource (lib "eagle-import") (part "R-US_R0402"))
    )
    (comp (ref "R47")
      (value "40.2k 1%")
      (footprint "eagle-import:R0402")
      (libsource (lib "eagle-import") (part "R-US_R0402"))
    )
    (comp (ref "R48")
      (value "499")
      (footprint "eagle-import:R0402")
      (libsource (lib "eagle-import") (part "R-US_R0402"))
    )
    (comp (ref "R49")
      (value "DNP")
      (footprint "eagle-import:R0402")
      (libsource (lib "eagle-import") (part "R-US_R0402"))
    )
    (comp (ref "R50")
      (value "10k 1%")
      (footprint "eagle-import:R0402")
      (libsource (lib "eagle-import") (part "R-US_R0402"))
    )
    (comp (ref "R51")
      (value "40.2k 1%")
      (footprint "eagle-import:R0402")
      (libsource (lib "eagle-import") (part "R-US_R0402"))
    )
    (comp (ref "R52")
      (value "4.75k, 1%")
      (footprint "eagle-import:R0402")
      (libsource (lib "eagle-import") (part "R-US_R0402"))
    )
    (comp (ref "R53")
      (value "4.75k, 1%")
      (footprint "eagle-import:R0402")
      (libsource (lib "eagle-import") (part "R-US_R0402"))
    )
    (comp (ref "R54")
      (value "0, 1%")
      (footprint "eagle-import:R0402")
      (libsource (lib "eagle-import") (part "R-US_R0402"))
    )
    (comp (ref "R55")
      (value "4.75k, 1%")
      (footprint "eagle-import:R0402")
      (libsource (lib "eagle-import") (part "R-US_R0402"))
    )
    (comp (ref "R56")
      (value "1M, 1%")
      (footprint "eagle-import:R0402")
      (libsource (lib "eagle-import") (part "R-US_R0402"))
    )
    (comp (ref "R57")
      (value "100k, 1%")
      (footprint "eagle-import:R0402")
      (libsource (lib "eagle-import") (part "R-US_R0402"))
    )
    (comp (ref "R58")
      (value "100k, 1%")
      (footprint "eagle-import:R0402")
      (libsource (lib "eagle-import") (part "R-US_R0402"))
    )
    (comp (ref "R60")
      (value "33, 5%")
      (footprint "eagle-import:R0402")
      (libsource (lib "eagle-import") (part "R-US_R0402"))
    )
    (comp (ref "R61")
      (value "100k, 1%")
      (footprint "eagle-import:R0402")
      (libsource (lib "eagle-import") (part "R-US_R0402"))
    )
    (comp (ref "R62")
      (value "33, 5%")
      (footprint "eagle-import:R0402")
      (libsource (lib "eagle-import") (part "R-US_R0402"))
    )
    (comp (ref "R63")
      (value "100k, 1%")
      (footprint "eagle-import:R0402")
      (libsource (lib "eagle-import") (part "R-US_R0402"))
    )
    (comp (ref "R64")
      (value "33, 5%")
      (footprint "eagle-import:R0402")
      (libsource (lib "eagle-import") (part "R-US_R0402"))
    )
    (comp (ref "R65")
      (value "100k, 1%")
      (footprint "eagle-import:R0402")
      (libsource (lib "eagle-import") (part "R-US_R0402"))
    )
    (comp (ref "R66")
      (value "33, 5%")
      (footprint "eagle-import:R0402")
      (libsource (lib "eagle-import") (part "R-US_R0402"))
    )
    (comp (ref "R67")
      (value "100k, 1%")
      (footprint "eagle-import:R0402")
      (libsource (lib "eagle-import") (part "R-US_R0402"))
    )
    (comp (ref "R68")
      (value "33, 5%")
      (footprint "eagle-import:R0402")
      (libsource (lib "eagle-import") (part "R-US_R0402"))
    )
    (comp (ref "R69")
      (value "100k, 1%")
      (footprint "eagle-import:R0402")
      (libsource (lib "eagle-import") (part "R-US_R0402"))
    )
    (comp (ref "R70")
      (value "33, 5%")
      (footprint "eagle-import:R0402")
      (libsource (lib "eagle-import") (part "R-US_R0402"))
    )
    (comp (ref "R71")
      (value "100k, 1%")
      (footprint "eagle-import:R0402")
      (libsource (lib "eagle-import") (part "R-US_R0402"))
    )
    (comp (ref "R72")
      (value "33, 5%")
      (footprint "eagle-import:R0402")
      (libsource (lib "eagle-import") (part "R-US_R0402"))
    )
    (comp (ref "R73")
      (value "100k, 1%")
      (footprint "eagle-import:R0402")
      (libsource (lib "eagle-import") (part "R-US_R0402"))
    )
    (comp (ref "R75")
      (value "100k, 1%")
      (footprint "eagle-import:R0402")
      (libsource (lib "eagle-import") (part "R-US_R0402"))
    )
    (comp (ref "R76")
      (value "100k, 1%")
      (footprint "eagle-import:R0402")
      (libsource (lib "eagle-import") (part "R-US_R0402"))
    )
    (comp (ref "R78")
      (value "100k, 1%")
      (footprint "eagle-import:R0402")
      (libsource (lib "eagle-import") (part "R-US_R0402"))
    )
    (comp (ref "R80")
      (value "100k, 1%")
      (footprint "eagle-import:R0402")
      (libsource (lib "eagle-import") (part "R-US_R0402"))
    )
    (comp (ref "R82")
      (value "100k, 1%")
      (footprint "eagle-import:R0402")
      (libsource (lib "eagle-import") (part "R-US_R0402"))
    )
    (comp (ref "R85")
      (value "100k, 1%")
      (footprint "eagle-import:R0402")
      (libsource (lib "eagle-import") (part "R-US_R0402"))
    )
    (comp (ref "R86")
      (value "33, 5%")
      (footprint "eagle-import:R0603")
      (libsource (lib "eagle-import") (part "R-US_R0603"))
    )
    (comp (ref "R87")
      (value "100k, 1%")
      (footprint "eagle-import:R0402")
      (libsource (lib "eagle-import") (part "R-US_R0402"))
    )
    (comp (ref "R88")
      (value "100, 1%")
      (footprint "eagle-import:R0402")
      (libsource (lib "eagle-import") (part "R-US_R0402"))
    )
    (comp (ref "R89")
      (value "1k")
      (footprint "eagle-import:R0402")
      (libsource (lib "eagle-import") (part "R-US_R0402"))
    )
    (comp (ref "R90")
      (value "1k")
      (footprint "eagle-import:R0402")
      (libsource (lib "eagle-import") (part "R-US_R0402"))
    )
    (comp (ref "R91")
      (value "0 DNP")
      (footprint "eagle-import:R0402")
      (libsource (lib "eagle-import") (part "R-US_R0402"))
    )
    (comp (ref "R92")
      (value "1k")
      (footprint "eagle-import:R0402")
      (libsource (lib "eagle-import") (part "R-US_R0402"))
    )
    (comp (ref "R93")
      (value "7.15k")
      (footprint "eagle-import:R0402")
      (libsource (lib "eagle-import") (part "R-US_R0402"))
    )
    (comp (ref "R94")
      (value "4.12k")
      (footprint "eagle-import:R0402")
      (libsource (lib "eagle-import") (part "R-US_R0402"))
    )
    (comp (ref "R95")
      (value "1M")
      (footprint "eagle-import:R0402")
      (libsource (lib "eagle-import") (part "R-US_R0402"))
    )
    (comp (ref "R96")
      (value "1k")
      (footprint "eagle-import:R0402")
      (libsource (lib "eagle-import") (part "R-US_R0402"))
    )
    (comp (ref "R97")
      (value "DNP 1k")
      (footprint "eagle-import:R0402")
      (libsource (lib "eagle-import") (part "R-US_R0402"))
    )
    (comp (ref "R98")
      (value "10k")
      (footprint "eagle-import:R0402")
      (libsource (lib "eagle-import") (part "R-US_R0402"))
    )
    (comp (ref "R99")
      (value "10k")
      (footprint "eagle-import:R0402")
      (libsource (lib "eagle-import") (part "R-US_R0402"))
    )
    (comp (ref "R100")
      (value "1k")
      (footprint "eagle-import:R0402")
      (libsource (lib "eagle-import") (part "R-US_R0402"))
    )
    (comp (ref "R101")
      (value "10k")
      (footprint "eagle-import:R0402")
      (libsource (lib "eagle-import") (part "R-US_R0402"))
    )
    (comp (ref "R102")
      (value "10k")
      (footprint "eagle-import:R0402")
      (libsource (lib "eagle-import") (part "R-US_R0402"))
    )
    (comp (ref "R103")
      (value "10k")
      (footprint "eagle-import:R0402")
      (libsource (lib "eagle-import") (part "R-US_R0402"))
    )
    (comp (ref "R104")
      (value "1k")
      (footprint "eagle-import:R0402")
      (libsource (lib "eagle-import") (part "R-US_R0402"))
    )
    (comp (ref "R105")
      (value "10k")
      (footprint "eagle-import:R0402")
      (libsource (lib "eagle-import") (part "R-US_R0402"))
    )
    (comp (ref "R106")
      (value "1.5k")
      (footprint "eagle-import:R0402")
      (libsource (lib "eagle-import") (part "R-US_R0402"))
    )
    (comp (ref "R108")
      (value "DNP 1k")
      (footprint "eagle-import:R0402")
      (libsource (lib "eagle-import") (part "R-US_R0402"))
    )
    (comp (ref "R109")
      (value "DNP 1k")
      (footprint "eagle-import:R0402")
      (libsource (lib "eagle-import") (part "R-US_R0402"))
    )
    (comp (ref "R110")
      (value "33")
      (footprint "eagle-import:R0402")
      (libsource (lib "eagle-import") (part "R-US_R0402"))
    )
    (comp (ref "R111")
      (value "DNP 10k")
      (footprint "eagle-import:R0402")
      (libsource (lib "eagle-import") (part "R-US_R0402"))
    )
    (comp (ref "R113")
      (value "33")
      (footprint "eagle-import:R0402")
      (libsource (lib "eagle-import") (part "R-US_R0402"))
    )
    (comp (ref "R114")
      (value "0, 1%")
      (footprint "eagle-import:R0402")
      (libsource (lib "eagle-import") (part "R-US_R0402"))
    )
    (comp (ref "R115")
      (value "1.5k, 1%")
      (footprint "eagle-import:R0402")
      (libsource (lib "eagle-import") (part "R-US_R0402"))
    )
    (comp (ref "R118")
      (value "1.5k, 1%")
      (footprint "eagle-import:R0402")
      (libsource (lib "eagle-import") (part "R-US_R0402"))
    )
    (comp (ref "R119")
      (value "10k, 1%")
      (footprint "eagle-import:R0402")
      (libsource (lib "eagle-import") (part "R-US_R0402"))
    )
    (comp (ref "R120")
      (value "27k, 1%")
      (footprint "eagle-import:R0402")
      (libsource (lib "eagle-import") (part "R-US_R0402"))
    )
    (comp (ref "R121")
      (value "10k, 1%")
      (footprint "eagle-import:R0402")
      (libsource (lib "eagle-import") (part "R-US_R0402"))
    )
    (comp (ref "R122")
      (value "0, 1%")
      (footprint "eagle-import:R0402")
      (libsource (lib "eagle-import") (part "R-US_R0402"))
    )
    (comp (ref "R123")
      (value "100k, 1%")
      (footprint "eagle-import:R0402")
      (libsource (lib "eagle-import") (part "R-US_R0402"))
    )
    (comp (ref "R124")
      (value "1k")
      (footprint "eagle-import:R0402")
      (libsource (lib "eagle-import") (part "R-US_R0402"))
    )
    (comp (ref "R125")
      (value "1k")
      (footprint "eagle-import:R0402")
      (libsource (lib "eagle-import") (part "R-US_R0402"))
    )
    (comp (ref "R126")
      (value "33, 5%")
      (footprint "eagle-import:R0603")
      (libsource (lib "eagle-import") (part "R-US_R0603"))
    )
    (comp (ref "R127")
      (value "33, 5%")
      (footprint "eagle-import:R0603")
      (libsource (lib "eagle-import") (part "R-US_R0603"))
    )
    (comp (ref "R128")
      (value "33, 5%")
      (footprint "eagle-import:R0603")
      (libsource (lib "eagle-import") (part "R-US_R0603"))
    )
    (comp (ref "R129")
      (value "33, 5%")
      (footprint "eagle-import:R0603")
      (libsource (lib "eagle-import") (part "R-US_R0603"))
    )
    (comp (ref "R130")
      (value "33, 5%")
      (footprint "eagle-import:R0603")
      (libsource (lib "eagle-import") (part "R-US_R0603"))
    )
    (comp (ref "R131")
      (value "33, 5%")
      (footprint "eagle-import:R0603")
      (libsource (lib "eagle-import") (part "R-US_R0603"))
    )
    (comp (ref "R134")
      (value "33, 5%")
      (footprint "eagle-import:R0603")
      (libsource (lib "eagle-import") (part "R-US_R0603"))
    )
    (comp (ref "R135")
      (value "33, 5%")
      (footprint "eagle-import:R0603")
      (libsource (lib "eagle-import") (part "R-US_R0603"))
    )
    (comp (ref "R136")
      (value "33, 5%")
      (footprint "eagle-import:R0603")
      (libsource (lib "eagle-import") (part "R-US_R0603"))
    )
    (comp (ref "R140")
      (value "33, 5%")
      (footprint "eagle-import:R0402")
      (libsource (lib "eagle-import") (part "R-US_R0402"))
    )
    (comp (ref "R141")
      (value "33, 5%")
      (footprint "eagle-import:R0402")
      (libsource (lib "eagle-import") (part "R-US_R0402"))
    )
    (comp (ref "R142")
      (value "33, 5%")
      (footprint "eagle-import:R0402")
      (libsource (lib "eagle-import") (part "R-US_R0402"))
    )
    (comp (ref "R143")
      (value "33, 5%")
      (footprint "eagle-import:R0402")
      (libsource (lib "eagle-import") (part "R-US_R0402"))
    )
    (comp (ref "RESET")
      (value "MINI_PUSHBUTTON")
      (footprint "eagle-import:MINI_PUSHBUTTON")
      (libsource (lib "eagle-import") (part "MINI_PUSHBUTTON"))
    )
    (comp (ref "S2")
      (value "MINI_PUSHBUTTON")
      (footprint "eagle-import:MINI_PUSHBUTTON")
      (libsource (lib "eagle-import") (part "MINI_PUSHBUTTON"))
    )
    (comp (ref "T1")
      (value "MMBT2907")
      (footprint "eagle-import:SOT23-BEC")
      (libsource (lib "eagle-import") (part "MMBT2907SMDALT1"))
    )
    (comp (ref "T2")
      (value "MMBT2907")
      (footprint "eagle-import:SOT23-BEC")
      (libsource (lib "eagle-import") (part "MMBT2907SMDALT1"))
    )
    (comp (ref "T3")
      (value "BSS138W-7-F")
      (footprint "eagle-import:SOT-323(DIODES)")
      (libsource (lib "eagle-import") (part "BSS138W-7-F"))
    )
    (comp (ref "T4")
      (value "BSS138W-7-F")
      (footprint "eagle-import:SOT-323(DIODES)")
      (libsource (lib "eagle-import") (part "BSS138W-7-F"))
    )
    (comp (ref "TP1")
      (value "TESTPAD/W_HOLE_1X1")
      (footprint "eagle-import:TESTPAD_W_HOLE_1X1")
      (libsource (lib "eagle-import") (part "TESTPAD/W_HOLE_1X1"))
    )
    (comp (ref "TP2")
      (value "TESTPAD/W_HOLE_1X1")
      (footprint "eagle-import:TESTPAD_W_HOLE_1X1")
      (libsource (lib "eagle-import") (part "TESTPAD/W_HOLE_1X1"))
    )
    (comp (ref "TP3")
      (value "TESTPAD/W_HOLE_1X1")
      (footprint "eagle-import:TESTPAD_W_HOLE_1X1")
      (libsource (lib "eagle-import") (part "TESTPAD/W_HOLE_1X1"))
    )
    (comp (ref "TP4")
      (value "TESTPAD/W_HOLE_1X1")
      (footprint "eagle-import:TESTPAD_W_HOLE_1X1")
      (libsource (lib "eagle-import") (part "TESTPAD/W_HOLE_1X1"))
    )
    (comp (ref "TP5")
      (value "TESTPAD/W_HOLE_1X1")
      (footprint "eagle-import:TESTPAD_W_HOLE_1X1")
      (libsource (lib "eagle-import") (part "TESTPAD/W_HOLE_1X1"))
    )
    (comp (ref "TP6")
      (value "PTR1B1,27")
      (footprint "eagle-import:B1,27")
      (libsource (lib "eagle-import") (part "PTR1B1,27"))
    )
    (comp (ref "TP12")
      (value "PTR1B1,27")
      (footprint "eagle-import:B1,27")
      (libsource (lib "eagle-import") (part "PTR1B1,27"))
    )
    (comp (ref "TP13")
      (value "PTR1B1,27")
      (footprint "eagle-import:B1,27")
      (libsource (lib "eagle-import") (part "PTR1B1,27"))
    )
    (comp (ref "TP14")
      (value "PTR1B1,27")
      (footprint "eagle-import:B1,27")
      (libsource (lib "eagle-import") (part "PTR1B1,27"))
    )
    (comp (ref "TP15")
      (value "PTR1B1,27")
      (footprint "eagle-import:B1,27")
      (libsource (lib "eagle-import") (part "PTR1B1,27"))
    )
    (comp (ref "TP16")
      (value "PTR1B1,27")
      (footprint "eagle-import:B1,27")
      (libsource (lib "eagle-import") (part "PTR1B1,27"))
    )
    (comp (ref "TP17")
      (value "PTR1B1,27")
      (footprint "eagle-import:B1,27")
      (libsource (lib "eagle-import") (part "PTR1B1,27"))
    )
    (comp (ref "TP18")
      (value "PTR1B1,27")
      (footprint "eagle-import:B1,27")
      (libsource (lib "eagle-import") (part "PTR1B1,27"))
    )
    (comp (ref "TP19")
      (value "PTR1B1,27")
      (footprint "eagle-import:B1,27")
      (libsource (lib "eagle-import") (part "PTR1B1,27"))
    )
    (comp (ref "TP23")
      (value "PTR1B1,27")
      (footprint "eagle-import:B1,27")
      (libsource (lib "eagle-import") (part "PTR1B1,27"))
    )
    (comp (ref "USR0")
      (value "LTST-C191TBKT")
      (footprint "eagle-import:0603-LED")
      (libsource (lib "eagle-import") (part "LED-(INCH)-0603"))
    )
    (comp (ref "USR1")
      (value "LTST-C191TBKT")
      (footprint "eagle-import:0603-LED")
      (libsource (lib "eagle-import") (part "LED-(INCH)-0603"))
    )
    (comp (ref "USR2")
      (value "LTST-C191TBKT")
      (footprint "eagle-import:0603-LED")
      (libsource (lib "eagle-import") (part "LED-(INCH)-0603"))
    )
    (comp (ref "USR3")
      (value "LTST-C191TBKT")
      (footprint "eagle-import:0603-LED")
      (libsource (lib "eagle-import") (part "LED-(INCH)-0603"))
    )
    (comp (ref "WL")
      (value "LTST-C191TBKT")
      (footprint "eagle-import:0603-LED")
      (libsource (lib "eagle-import") (part "LED-(INCH)-0603"))
    )
    (comp (ref "X1")
      (value "1X6-(INCH)-0.1-TH")
      (footprint "eagle-import:TH-1X6")
      (libsource (lib "eagle-import") (part "1X6-(INCH)-0.1-TH"))
    )
    (comp (ref "X2")
      (value "SCHA5B0200")
      (footprint "eagle-import:SCHA5B0200")
      (libsource (lib "eagle-import") (part "SCHA5B0200(ALPS_USD)"))
    )
    (comp (ref "X3")
      (value "USB_HOST_W/CHASSIS_GND")
      (footprint "eagle-import:USB_HOST_HORIZONTAL_W_CHASSIS_GND")
      (libsource (lib "eagle-import") (part "USB_HOST_W/CHASSIS_GND"))
    )
    (comp (ref "X4")
      (value "10118192-0001LF")
      (footprint "eagle-import:10118192-0001LF(MICRO-USB-B-AMPHENOL-FCI)")
      (libsource (lib "eagle-import") (part "10118192-0001LF"))
    )
    (comp (ref "X5")
      (value "10118241-001RLF")
      (footprint "eagle-import:HDMI-TYPE-D-10118241")
      (libsource (lib "eagle-import") (part "HDMI-TYPE-D-10118241"))
    )
    (comp (ref "X8")
      (value "HEADER-2X23-(INCH)-0.1-TH")
      (footprint "eagle-import:TH-2X23")
      (libsource (lib "eagle-import") (part "HEADER-2X23-(INCH)-0.1-TH"))
    )
    (comp (ref "X9")
      (value "HEADER-2X23-(INCH)-0.1-TH")
      (footprint "eagle-import:TH-2X23")
      (libsource (lib "eagle-import") (part "HEADER-2X23-(INCH)-0.1-TH"))
    )
    (comp (ref "X12")
      (value "PJ-102B_POWER_CON")
      (footprint "eagle-import:PJ-102B_POWER_CON")
      (libsource (lib "eagle-import") (part "PJ-102B_POWER_CON"))
    )
  )
  (nets
    (net (code "1") (name "/5V_IN") (class "Default")
      (node (ref "C19") (pin "1") (pinfunction "1_1") (pintype "passive"))
      (node (ref "D8") (pin "3") (pinfunction "CC_3") (pintype "passive"))
      (node (ref "FB1") (pin "2") (pinfunction "P$2_2") (pintype "bidirectional"))
      (node (ref "IC18") (pin "2") (pinfunction "IN_2") (pintype "bidirectional"))
      (node (ref "R95") (pin "1") (pinfunction "1_1") (pintype "passive"))
    )
    (net (code "2") (name "/12MHZ") (class "Default")
      (node (ref "IC9") (pin "27") (pinfunction "OSC_IN/AP3_27") (pintype "bidirectional"))
      (node (ref "R113") (pin "2") (pinfunction "2_2") (pintype "passive"))
    )
    (net (code "3") (name "/12M_LOOP") (class "Default")
      (node (ref "IC13") (pin "2") (pinfunction "D_2") (pintype "bidirectional"))
      (node (ref "IC13") (pin "3") (pinfunction "Q#_3") (pintype "bidirectional"))
    )
    (net (code "4") (name "/32.768KHZ") (class "Default")
      (node (ref "MOD1") (pin "36") (pinfunction "EXT_32K_36") (pintype "bidirectional"))
      (node (ref "OSC2") (pin "3") (pinfunction "OUT_3") (pintype "bidirectional"))
      (node (ref "R91") (pin "2") (pinfunction "2_2") (pintype "passive"))
    )
    (net (code "5") (name "/AIN0") (class "Default")
      (node (ref "IC1") (pin "B6") (pinfunction "AIN0_B6") (pintype "bidirectional"))
      (node (ref "X9") (pin "39") (pinfunction "39_39") (pintype "passive"))
    )
    (net (code "6") (name "/AIN1") (class "Default")
      (node (ref "IC1") (pin "C7") (pinfunction "AIN1_C7") (pintype "bidirectional"))
      (node (ref "X9") (pin "40") (pinfunction "40_40") (pintype "passive"))
    )
    (net (code "7") (name "/AIN2") (class "Default")
      (node (ref "IC1") (pin "B7") (pinfunction "AIN2_B7") (pintype "bidirectional"))
      (node (ref "X9") (pin "37") (pinfunction "37_37") (pintype "passive"))
    )
    (net (code "8") (name "/AIN3") (class "Default")
      (node (ref "IC1") (pin "A7") (pinfunction "AIN3_A7") (pintype "bidirectional"))
      (node (ref "X9") (pin "38") (pinfunction "38_38") (pintype "passive"))
    )
    (net (code "9") (name "/AIN4") (class "Default")
      (node (ref "IC1") (pin "C8") (pinfunction "AIN4_C8") (pintype "bidirectional"))
      (node (ref "X9") (pin "33") (pinfunction "33_33") (pintype "passive"))
    )
    (net (code "10") (name "/AIN5") (class "Default")
      (node (ref "IC1") (pin "B8") (pinfunction "AIN5_B8") (pintype "bidirectional"))
      (node (ref "X9") (pin "36") (pinfunction "36_36") (pintype "passive"))
    )
    (net (code "11") (name "/AIN6") (class "Default")
      (node (ref "IC1") (pin "A8") (pinfunction "AIN6_A8") (pintype "bidirectional"))
      (node (ref "X9") (pin "35") (pinfunction "35_35") (pintype "passive"))
    )
    (net (code "12") (name "/BAT_TEMP") (class "Default")
      (node (ref "IC1") (pin "W1") (pinfunction "BAT_TEMP_W1") (pintype "bidirectional"))
      (node (ref "TP4") (pin "P$1") (pinfunction "TP_P$1") (pintype "bidirectional"))
    )
    (net (code "13") (name "/BAT_VOLT") (class "Default")
      (node (ref "IC1") (pin "Y1") (pinfunction "BATT_VOLT_Y1") (pintype "bidirectional"))
      (node (ref "TP3") (pin "P$1") (pinfunction "TP_P$1") (pintype "bidirectional"))
    )
    (net (code "14") (name "/BT_EN") (class "Default")
      (node (ref "IC11") (pin "4") (pinfunction "A3_4") (pintype "bidirectional"))
      (node (ref "MOD1") (pin "41") (pinfunction "BT_EN_41") (pintype "bidirectional"))
      (node (ref "R11") (pin "1") (pinfunction "1_1") (pintype "passive"))
      (node (ref "T4") (pin "G") (pinfunction "G_G") (pintype "bidirectional"))
    )
    (net (code "15") (name "/BT_EN.SIP") (class "Default")
      (node (ref "IC1") (pin "K17") (pinfunction "MII1_TXD0_K17") (pintype "bidirectional"))
      (node (ref "R135") (pin "1") (pinfunction "1_1") (pintype "passive"))
    )
    (net (code "16") (name "/BT_HCI_CTS") (class "Default")
      (node (ref "IC11") (pin "8") (pinfunction "A7_8") (pintype "bidirectional"))
      (node (ref "R141") (pin "2") (pinfunction "2_2") (pintype "passive"))
    )
    (net (code "17") (name "/BT_HCI_CTS.SIP") (class "Default")
      (node (ref "IC1") (pin "M17") (pinfunction "MDIO_DATA_M17") (pintype "bidirectional"))
      (node (ref "IC11") (pin "15") (pinfunction "B5_15") (pintype "bidirectional"))
      (node (ref "R108") (pin "1") (pinfunction "1_1") (pintype "passive"))
    )
    (net (code "18") (name "/BT_HCI_RTS") (class "Default")
      (node (ref "IC11") (pin "6") (pinfunction "A5_6") (pintype "bidirectional"))
      (node (ref "R140") (pin "2") (pinfunction "2_2") (pintype "passive"))
    )
    (net (code "19") (name "/BT_HCI_RTS.SIP") (class "Default")
      (node (ref "IC1") (pin "M18") (pinfunction "MDIO_CLK_M18") (pintype "bidirectional"))
      (node (ref "IC11") (pin "13") (pinfunction "B7_13") (pintype "bidirectional"))
      (node (ref "R109") (pin "1") (pinfunction "1_1") (pintype "passive"))
    )
    (net (code "20") (name "/BT_HCI_RX") (class "Default")
      (node (ref "IC11") (pin "1") (pinfunction "A1_1") (pintype "bidirectional"))
      (node (ref "R143") (pin "2") (pinfunction "2_2") (pintype "passive"))
    )
    (net (code "21") (name "/BT_HCI_RX.SIP") (class "Default")
      (node (ref "IC1") (pin "L17") (pinfunction "MII1_RXD3_L17") (pintype "bidirectional"))
      (node (ref "IC11") (pin "14") (pinfunction "B6_14") (pintype "bidirectional"))
    )
    (net (code "22") (name "/BT_HCI_TX") (class "Default")
      (node (ref "IC11") (pin "7") (pinfunction "A6_7") (pintype "bidirectional"))
      (node (ref "R142") (pin "2") (pinfunction "2_2") (pintype "passive"))
    )
    (net (code "23") (name "/BT_HCI_TX.SIP") (class "Default")
      (node (ref "IC1") (pin "L16") (pinfunction "MII1_RXD2_L16") (pintype "bidirectional"))
      (node (ref "IC11") (pin "20") (pinfunction "B1_20") (pintype "bidirectional"))
    )
    (net (code "24") (name "/CEC") (class "Default")
      (node (ref "D1") (pin "C") (pinfunction "CATHODE_C") (pintype "bidirectional"))
      (node (ref "IC9") (pin "30") (pinfunction "CEC_30") (pintype "bidirectional"))
      (node (ref "X5") (pin "15") (pinfunction "CEC_15") (pintype "bidirectional"))
    )
    (net (code "25") (name "/CLKOUT2") (class "Default")
      (node (ref "IC11") (pin "16") (pinfunction "B4_16") (pintype "bidirectional"))
      (node (ref "JTAG1") (pin "18") (pinfunction "EMU3_18") (pintype "bidirectional"))
      (node (ref "R14") (pin "1") (pinfunction "1_1") (pintype "passive"))
      (node (ref "R15") (pin "1") (pinfunction "1_1") (pintype "passive"))
      (node (ref "X9") (pin "41") (pinfunction "41_41") (pintype "passive"))
    )
    (net (code "26") (name "/DVI_5V") (class "Default")
      (node (ref "F1") (pin "1") (pinfunction "1_1") (pintype "passive"))
      (node (ref "R115") (pin "1") (pinfunction "1_1") (pintype "passive"))
      (node (ref "R118") (pin "1") (pinfunction "1_1") (pintype "passive"))
      (node (ref "X5") (pin "19") (pinfunction "5V_19") (pintype "bidirectional"))
    )
    (net (code "27") (name "/EHRPWM1A") (class "Default")
      (node (ref "IC1") (pin "U14") (pinfunction "EHRPWM1A_U14") (pintype "bidirectional"))
      (node (ref "X9") (pin "14") (pinfunction "14_14") (pintype "passive"))
    )
    (net (code "28") (name "/EHRPWM1B") (class "Default")
      (node (ref "IC1") (pin "T14") (pinfunction "EHRPWM1B_T14") (pintype "bidirectional"))
      (node (ref "X9") (pin "16") (pinfunction "16_16") (pintype "passive"))
    )
    (net (code "29") (name "/EHRPWM2A") (class "Default")
      (node (ref "IC1") (pin "U10") (pinfunction "EHRPWM2A_U10") (pintype "bidirectional"))
      (node (ref "X8") (pin "19") (pinfunction "19_19") (pintype "passive"))
    )
    (net (code "30") (name "/EHRPWM2B") (class "Default")
      (node (ref "IC1") (pin "T10") (pinfunction "EHRPWM2B_T10") (pintype "bidirectional"))
      (node (ref "X8") (pin "13") (pinfunction "13_13") (pintype "passive"))
    )
    (net (code "31") (name "/EMMC_RSTN") (class "Default")
      (node (ref "IC22") (pin "K5") (pinfunction "RST#_K5") (pintype "bidirectional"))
      (node (ref "R29") (pin "1") (pinfunction "1_1") (pintype "passive"))
      (node (ref "R33") (pin "1") (pinfunction "1_1") (pintype "passive"))
    )
    (net (code "32") (name "/EXT_SWING") (class "Default")
      (node (ref "IC9") (pin "34") (pinfunction "EXT_SWING_34") (pintype "bidirectional"))
      (node (ref "R119") (pin "1") (pinfunction "1_1") (pintype "passive"))
    )
    (net (code "33") (name "/GPIO0_7") (class "Default")
      (node (ref "R36") (pin "1") (pinfunction "1_1") (pintype "passive"))
      (node (ref "R38") (pin "1") (pinfunction "1_1") (pintype "passive"))
      (node (ref "X9") (pin "42") (pinfunction "42_42") (pintype "passive"))
    )
    (net (code "34") (name "/GPIO0_26") (class "Default")
      (node (ref "IC1") (pin "T11") (pinfunction "GPIO0_26_T11") (pintype "bidirectional"))
      (node (ref "X8") (pin "14") (pinfunction "14_14") (pintype "passive"))
    )
    (net (code "35") (name "/GPIO0_27") (class "Default")
      (node (ref "IC1") (pin "U12") (pinfunction "GPIO0_27_U12") (pintype "bidirectional"))
      (node (ref "X8") (pin "17") (pinfunction "17_17") (pintype "passive"))
    )
    (net (code "36") (name "/GPIO1_12") (class "Default")
      (node (ref "IC1") (pin "T12") (pinfunction "GPIO1_12_T12") (pintype "bidirectional"))
      (node (ref "X8") (pin "12") (pinfunction "12_12") (pintype "passive"))
    )
    (net (code "37") (name "/GPIO1_13") (class "Default")
      (node (ref "IC1") (pin "R12") (pinfunction "GPIO1_13_R12") (pintype "bidirectional"))
      (node (ref "X8") (pin "11") (pinfunction "11_11") (pintype "passive"))
    )
    (net (code "38") (name "/GPIO1_14") (class "Default")
      (node (ref "IC1") (pin "V13") (pinfunction "GPIO1_14_V13") (pintype "bidirectional"))
      (node (ref "X8") (pin "16") (pinfunction "16_16") (pintype "passive"))
    )
    (net (code "39") (name "/GPIO1_15") (class "Default")
      (node (ref "IC1") (pin "U13") (pinfunction "GPIO1_15_U13") (pintype "bidirectional"))
      (node (ref "X8") (pin "15") (pinfunction "15_15") (pintype "passive"))
    )
    (net (code "40") (name "/GPIO1_16") (class "Default")
      (node (ref "R54") (pin "1") (pinfunction "1_1") (pintype "passive"))
      (node (ref "X9") (pin "15") (pinfunction "15_15") (pintype "passive"))
    )
    (net (code "41") (name "/GPIO1_16.SIP") (class "Default")
      (node (ref "IC1") (pin "R13") (pinfunction "GPIO1_16_R13") (pintype "bidirectional"))
      (node (ref "R54") (pin "2") (pinfunction "2_2") (pintype "passive"))
    )
    (net (code "42") (name "/GPIO1_17") (class "Default")
      (node (ref "IC1") (pin "V14") (pinfunction "GPIO1_17_V14") (pintype "bidirectional"))
      (node (ref "X9") (pin "23") (pinfunction "23_23") (pintype "passive"))
    )
    (net (code "43") (name "/GPIO1_28") (class "Default")
      (node (ref "IC1") (pin "U18") (pinfunction "GPIO1_28_U18") (pintype "bidirectional"))
      (node (ref "X9") (pin "12") (pinfunction "12_12") (pintype "passive"))
    )
    (net (code "44") (name "/GPIO1_29") (class "Default")
      (node (ref "IC1") (pin "V6") (pinfunction "GPIO1_29_V6") (pintype "bidirectional"))
      (node (ref "X8") (pin "26") (pinfunction "26_26") (pintype "passive"))
    )
    (net (code "45") (name "/GPIO2_0.SIP") (class "Default")
      (node (ref "IC1") (pin "T13") (pinfunction "GPIO2_0_T13") (pintype "bidirectional"))
    )
    (net (code "46") (name "/GPIO2_1") (class "Default")
      (node (ref "IC1") (pin "V12") (pinfunction "GPIO2_1_V12") (pintype "bidirectional"))
      (node (ref "X8") (pin "18") (pinfunction "18_18") (pintype "passive"))
    )
    (net (code "47") (name "/GPIO3_19") (class "Default")
      (node (ref "IC1") (pin "C13") (pinfunction "GPIO3_19_C13") (pintype "bidirectional"))
      (node (ref "X9") (pin "27") (pinfunction "27_27") (pintype "passive"))
    )
    (net (code "48") (name "/GPIO3_21") (class "Default")
      (node (ref "IC1") (pin "A14") (pinfunction "GPIO3_21_A14") (pintype "bidirectional"))
      (node (ref "R110") (pin "2") (pinfunction "2_2") (pintype "passive"))
      (node (ref "X9") (pin "25") (pinfunction "25_25") (pintype "passive"))
    )
    (net (code "49") (name "/HDMICLK_DIS#") (class "Default")
      (node (ref "IC1") (pin "V17") (pinfunction "(HDMICLK_DISN)GPIO1_27_V17") (pintype "bidirectional"))
      (node (ref "OSC1") (pin "1") (pinfunction "INH#_1") (pintype "bidirectional"))
    )
    (net (code "50") (name "/HDMI_INT") (class "Default")
      (node (ref "IC1") (pin "U16") (pinfunction "(HDMI_INT)GPIO1_25_U16") (pintype "bidirectional"))
      (node (ref "IC9") (pin "50") (pinfunction "INT_50") (pintype "bidirectional"))
      (node (ref "R121") (pin "2") (pinfunction "2_2") (pintype "passive"))
    )
    (net (code "51") (name "/HPD") (class "Default")
      (node (ref "IC9") (pin "31") (pinfunction "HPD_31") (pintype "bidirectional"))
      (node (ref "X5") (pin "1") (pinfunction "HOT.PLUG.DETECT_1") (pintype "bidirectional"))
    )
    (net (code "52") (name "/I2C0_SCL") (class "Default")
      (node (ref "IC1") (pin "C16") (pinfunction "I2C0_SCL_C16") (pintype "bidirectional"))
      (node (ref "IC1") (pin "C20") (pinfunction "PMIC_I2C_SCL_C20") (pintype "bidirectional"))
      (node (ref "IC4") (pin "1") (pinfunction "SCL_1") (pintype "bidirectional"))
      (node (ref "IC9") (pin "52") (pinfunction "CSCL_52") (pintype "bidirectional"))
      (node (ref "R41") (pin "2") (pinfunction "2_2") (pintype "passive"))
    )
    (net (code "53") (name "/I2C0_SDA") (class "Default")
      (node (ref "IC1") (pin "C17") (pinfunction "I2C0_SDA_C17") (pintype "bidirectional"))
      (node (ref "IC1") (pin "C19") (pinfunction "PMIC_I2C_SDA_C19") (pintype "bidirectional"))
      (node (ref "IC4") (pin "3") (pinfunction "SDA_3") (pintype "bidirectional"))
      (node (ref "IC9") (pin "51") (pinfunction "CSDA_51") (pintype "bidirectional"))
      (node (ref "R42") (pin "2") (pinfunction "2_2") (pintype "passive"))
    )
    (net (code "54") (name "/I2C1_SCL") (class "Default")
      (node (ref "IC1") (pin "A16") (pinfunction "I2C1_SCL_A16") (pintype "bidirectional"))
      (node (ref "X9") (pin "17") (pinfunction "17_17") (pintype "passive"))
    )
    (net (code "55") (name "/I2C1_SDA") (class "Default")
      (node (ref "IC1") (pin "B16") (pinfunction "I2C1_SDA_B16") (pintype "bidirectional"))
      (node (ref "X9") (pin "18") (pinfunction "18_18") (pintype "passive"))
    )
    (net (code "56") (name "/I2C2_SCL") (class "Default")
      (node (ref "IC1") (pin "D17") (pinfunction "I2C2_SCL_D17") (pintype "bidirectional"))
      (node (ref "X9") (pin "19") (pinfunction "19_19") (pintype "passive"))
    )
    (net (code "57") (name "/I2C2_SDA") (class "Default")
      (node (ref "IC1") (pin "D18") (pinfunction "I2C2_SDA_D18") (pintype "bidirectional"))
      (node (ref "X9") (pin "20") (pinfunction "20_20") (pintype "passive"))
    )
    (net (code "58") (name "/JTAG_EMU0") (class "Default")
      (node (ref "IC1") (pin "C14") (pinfunction "JTAG_EMU0_C14") (pintype "bidirectional"))
      (node (ref "JTAG1") (pin "13") (pinfunction "EMU0_13") (pintype "bidirectional"))
      (node (ref "R43") (pin "2") (pinfunction "2_2") (pintype "passive"))
    )
    (net (code "59") (name "/JTAG_EMU1") (class "Default")
      (node (ref "IC1") (pin "B14") (pinfunction "JTAG_EMU1_B14") (pintype "bidirectional"))
      (node (ref "JTAG1") (pin "14") (pinfunction "EMU1_14") (pintype "bidirectional"))
      (node (ref "R53") (pin "2") (pinfunction "2_2") (pintype "passive"))
    )
    (net (code "60") (name "/JTAG_TCK") (class "Default")
      (node (ref "IC1") (pin "A12") (pinfunction "JTAG_TCK_A12") (pintype "bidirectional"))
      (node (ref "JTAG1") (pin "11") (pinfunction "TCK_11") (pintype "bidirectional"))
      (node (ref "JTAG1") (pin "9") (pinfunction "TCKRTN_9") (pintype "bidirectional"))
    )
    (net (code "61") (name "/JTAG_TDI") (class "Default")
      (node (ref "IC1") (pin "B11") (pinfunction "JTAG_TDI_B11") (pintype "bidirectional"))
      (node (ref "JTAG1") (pin "3") (pinfunction "TDI_3") (pintype "bidirectional"))
    )
    (net (code "62") (name "/JTAG_TDO") (class "Default")
      (node (ref "IC1") (pin "A11") (pinfunction "JTAG_TDO_A11") (pintype "bidirectional"))
      (node (ref "JTAG1") (pin "7") (pinfunction "TDO_7") (pintype "bidirectional"))
    )
    (net (code "63") (name "/JTAG_TMS") (class "Default")
      (node (ref "IC1") (pin "C11") (pinfunction "JTAG_TMS_C11") (pintype "bidirectional"))
      (node (ref "JTAG1") (pin "1") (pinfunction "TMS_1") (pintype "bidirectional"))
    )
    (net (code "64") (name "/JTAG_TRSTN") (class "Default")
      (node (ref "IC1") (pin "B10") (pinfunction "JTAG_TRSTN_B10") (pintype "bidirectional"))
      (node (ref "JTAG1") (pin "2") (pinfunction "TRST#_2") (pintype "bidirectional"))
      (node (ref "R52") (pin "1") (pinfunction "1_1") (pintype "passive"))
    )
    (net (code "65") (name "/LCD.CLOCK") (class "Default")
      (node (ref "IC9") (pin "4") (pinfunction "PCLK_4") (pintype "bidirectional"))
      (node (ref "R34") (pin "1") (pinfunction "1_1") (pintype "passive"))
      (node (ref "X8") (pin "28") (pinfunction "28_28") (pintype "passive"))
    )
    (net (code "66") (name "/LCD.D0.B0--B3") (class "Default")
      (node (ref "C42") (pin "1") (pinfunction "1_1") (pintype "passive"))
      (node (ref "IC1") (pin "R1") (pinfunction "LCD_DATA0_R1") (pintype "bidirectional"))
      (node (ref "IC9") (pin "15") (pinfunction "VPC[3]_15") (pintype "bidirectional"))
      (node (ref "R87") (pin "2") (pinfunction "2_2") (pintype "passive"))
      (node (ref "X8") (pin "45") (pinfunction "45_45") (pintype "passive"))
    )
    (net (code "67") (name "/LCD.D1.B1--B4") (class "Default")
      (node (ref "C41") (pin "1") (pinfunction "1_1") (pintype "passive"))
      (node (ref "IC1") (pin "R2") (pinfunction "LCD_DATA1_R2") (pintype "bidirectional"))
      (node (ref "IC9") (pin "13") (pinfunction "VPC[4]_13") (pintype "bidirectional"))
      (node (ref "R85") (pin "2") (pinfunction "2_2") (pintype "passive"))
      (node (ref "X8") (pin "46") (pinfunction "46_46") (pintype "passive"))
    )
    (net (code "68") (name "/LCD.D2.B2--B5") (class "Default")
      (node (ref "C40") (pin "1") (pinfunction "1_1") (pintype "passive"))
      (node (ref "IC1") (pin "R3") (pinfunction "LCD_DATA2_R3") (pintype "bidirectional"))
      (node (ref "IC9") (pin "12") (pinfunction "VPC[5]_12") (pintype "bidirectional"))
      (node (ref "R82") (pin "1") (pinfunction "1_1") (pintype "passive"))
      (node (ref "R88") (pin "1") (pinfunction "1_1") (pintype "passive"))
      (node (ref "X8") (pin "43") (pinfunction "43_43") (pintype "passive"))
    )
    (net (code "69") (name "/LCD.D3.B3--B6") (class "Default")
      (node (ref "C39") (pin "1") (pinfunction "1_1") (pintype "passive"))
      (node (ref "IC1") (pin "R4") (pinfunction "LCD_DATA3_R4") (pintype "bidirectional"))
      (node (ref "IC9") (pin "11") (pinfunction "VPC[6]_11") (pintype "bidirectional"))
      (node (ref "R80") (pin "1") (pinfunction "1_1") (pintype "passive"))
      (node (ref "X8") (pin "44") (pinfunction "44_44") (pintype "passive"))
    )
    (net (code "70") (name "/LCD.D4.B4--B7") (class "Default")
      (node (ref "C38") (pin "1") (pinfunction "1_1") (pintype "passive"))
      (node (ref "IC1") (pin "T1") (pinfunction "LCD_DATA4_T1") (pintype "bidirectional"))
      (node (ref "IC9") (pin "10") (pinfunction "VPC[7]_10") (pintype "bidirectional"))
      (node (ref "R78") (pin "1") (pinfunction "1_1") (pintype "passive"))
      (node (ref "X8") (pin "41") (pinfunction "41_41") (pintype "passive"))
    )
    (net (code "71") (name "/LCD.D5.G0--G2") (class "Default")
      (node (ref "C37") (pin "1") (pinfunction "1_1") (pintype "passive"))
      (node (ref "IC1") (pin "T2") (pinfunction "LCD_DATA5_T2") (pintype "bidirectional"))
      (node (ref "IC9") (pin "7") (pinfunction "VPB[2]_7") (pintype "bidirectional"))
      (node (ref "R76") (pin "1") (pinfunction "1_1") (pintype "passive"))
      (node (ref "X8") (pin "42") (pinfunction "42_42") (pintype "passive"))
    )
    (net (code "72") (name "/LCD.D6.G1--G3") (class "Default")
      (node (ref "C36") (pin "1") (pinfunction "1_1") (pintype "passive"))
      (node (ref "IC1") (pin "T3") (pinfunction "LCD_DATA6_T3") (pintype "bidirectional"))
      (node (ref "IC9") (pin "6") (pinfunction "VPB[3]_6") (pintype "bidirectional"))
      (node (ref "R75") (pin "2") (pinfunction "2_2") (pintype "passive"))
      (node (ref "X8") (pin "39") (pinfunction "39_39") (pintype "passive"))
    )
    (net (code "73") (name "/LCD.D7.G2--G4") (class "Default")
      (node (ref "C35") (pin "1") (pinfunction "1_1") (pintype "passive"))
      (node (ref "IC1") (pin "T4") (pinfunction "LCD_DATA7_T4") (pintype "bidirectional"))
      (node (ref "IC9") (pin "3") (pinfunction "VPB[4]_3") (pintype "bidirectional"))
      (node (ref "R73") (pin "2") (pinfunction "2_2") (pintype "passive"))
      (node (ref "X8") (pin "40") (pinfunction "40_40") (pintype "passive"))
    )
    (net (code "74") (name "/LCD.D8.G3--G5") (class "Default")
      (node (ref "C34") (pin "1") (pinfunction "1_1") (pintype "passive"))
      (node (ref "IC1") (pin "U1") (pinfunction "LCD_DATA8_U1") (pintype "bidirectional"))
      (node (ref "IC9") (pin "2") (pinfunction "VPB[5]_2") (pintype "bidirectional"))
      (node (ref "R71") (pin "2") (pinfunction "2_2") (pintype "passive"))
      (node (ref "X8") (pin "37") (pinfunction "37_37") (pintype "passive"))
    )
    (net (code "75") (name "/LCD.D9.G4--G6") (class "Default")
      (node (ref "C33") (pin "1") (pinfunction "1_1") (pintype "passive"))
      (node (ref "IC1") (pin "U2") (pinfunction "LCD_DATA9_U2") (pintype "bidirectional"))
      (node (ref "IC9") (pin "1") (pinfunction "VPB[6]_1") (pintype "bidirectional"))
      (node (ref "R69") (pin "2") (pinfunction "2_2") (pintype "passive"))
      (node (ref "X8") (pin "38") (pinfunction "38_38") (pintype "passive"))
    )
    (net (code "76") (name "/LCD.D10.G5--G7") (class "Default")
      (node (ref "C32") (pin "1") (pinfunction "1_1") (pintype "passive"))
      (node (ref "IC1") (pin "U3") (pinfunction "LCD_DATA10_U3") (pintype "bidirectional"))
      (node (ref "IC9") (pin "64") (pinfunction "VPB[7]_64") (pintype "bidirectional"))
      (node (ref "R67") (pin "2") (pinfunction "2_2") (pintype "passive"))
      (node (ref "X8") (pin "36") (pinfunction "36_36") (pintype "passive"))
    )
    (net (code "77") (name "/LCD.D11.R0--R3") (class "Default")
      (node (ref "C31") (pin "1") (pinfunction "1_1") (pintype "passive"))
      (node (ref "IC1") (pin "U4") (pinfunction "LCD_DATA11_U4") (pintype "bidirectional"))
      (node (ref "IC9") (pin "60") (pinfunction "VPA[3]_60") (pintype "bidirectional"))
      (node (ref "R65") (pin "2") (pinfunction "2_2") (pintype "passive"))
      (node (ref "X8") (pin "34") (pinfunction "34_34") (pintype "passive"))
    )
    (net (code "78") (name "/LCD.D12.R1--R4") (class "Default")
      (node (ref "C30") (pin "1") (pinfunction "1_1") (pintype "passive"))
      (node (ref "IC1") (pin "V2") (pinfunction "LCD_DATA12_V2") (pintype "bidirectional"))
      (node (ref "IC9") (pin "59") (pinfunction "VPA[4]_59") (pintype "bidirectional"))
      (node (ref "R63") (pin "2") (pinfunction "2_2") (pintype "passive"))
      (node (ref "X8") (pin "35") (pinfunction "35_35") (pintype "passive"))
    )
    (net (code "79") (name "/LCD.D13.R2--R5") (class "Default")
      (node (ref "C29") (pin "1") (pinfunction "1_1") (pintype "passive"))
      (node (ref "IC1") (pin "V3") (pinfunction "LCD_DATA13_V3") (pintype "bidirectional"))
      (node (ref "IC9") (pin "58") (pinfunction "VPA[5]_58") (pintype "bidirectional"))
      (node (ref "R61") (pin "2") (pinfunction "2_2") (pintype "passive"))
      (node (ref "X8") (pin "33") (pinfunction "33_33") (pintype "passive"))
    )
    (net (code "80") (name "/LCD.D14.R3--R6") (class "Default")
      (node (ref "C28") (pin "1") (pinfunction "1_1") (pintype "passive"))
      (node (ref "IC1") (pin "V4") (pinfunction "LCD_DATA14_V4") (pintype "bidirectional"))
      (node (ref "IC9") (pin "57") (pinfunction "VPA[6]_57") (pintype "bidirectional"))
      (node (ref "R58") (pin "1") (pinfunction "1_1") (pintype "passive"))
      (node (ref "X8") (pin "31") (pinfunction "31_31") (pintype "passive"))
    )
    (net (code "81") (name "/LCD.D15.R4--R7") (class "Default")
      (node (ref "C27") (pin "1") (pinfunction "1_1") (pintype "passive"))
      (node (ref "IC1") (pin "T5") (pinfunction "LCD_DATA15_T5") (pintype "bidirectional"))
      (node (ref "IC9") (pin "56") (pinfunction "VPA[7]_56") (pintype "bidirectional"))
      (node (ref "R57") (pin "2") (pinfunction "2_2") (pintype "passive"))
      (node (ref "X8") (pin "32") (pinfunction "32_32") (pintype "passive"))
    )
    (net (code "82") (name "/LCD.ENABLE") (class "Default")
      (node (ref "IC9") (pin "20") (pinfunction "DE/FREF_20") (pintype "bidirectional"))
      (node (ref "R39") (pin "1") (pinfunction "1_1") (pintype "passive"))
      (node (ref "X8") (pin "30") (pinfunction "30_30") (pintype "passive"))
    )
    (net (code "83") (name "/LCD.HSYNC") (class "Default")
      (node (ref "IC9") (pin "22") (pinfunction "HSYNC/HREF_22") (pintype "bidirectional"))
      (node (ref "R37") (pin "1") (pinfunction "1_1") (pintype "passive"))
      (node (ref "X8") (pin "29") (pinfunction "29_29") (pintype "passive"))
    )
    (net (code "84") (name "/LCD.VSYNC") (class "Default")
      (node (ref "IC9") (pin "21") (pinfunction "VSYNC/VREF_21") (pintype "bidirectional"))
      (node (ref "R35") (pin "1") (pinfunction "1_1") (pintype "passive"))
      (node (ref "X8") (pin "27") (pinfunction "27_27") (pintype "passive"))
    )
    (net (code "85") (name "/LDO_PGOOD") (class "Default")
      (node (ref "IC1") (pin "B20") (pinfunction "PMIC_LDO_PGOOD_B20") (pintype "bidirectional"))
      (node (ref "IC1") (pin "B5") (pinfunction "RTC_PORZ_B5") (pintype "bidirectional"))
    )
    (net (code "86") (name "/LS_BUF_OE") (class "Default")
      (node (ref "IC1") (pin "L18") (pinfunction "MII_RXCLK_L18") (pintype "bidirectional"))
      (node (ref "R131") (pin "2") (pinfunction "2_2") (pintype "passive"))
    )
    (net (code "87") (name "/MCC1_CLK") (class "Default")
      (node (ref "IC1") (pin "U9") (pinfunction "MMC1_CLK_U9") (pintype "bidirectional"))
      (node (ref "IC22") (pin "M6") (pinfunction "CLK_M6") (pintype "bidirectional"))
      (node (ref "R31") (pin "1") (pinfunction "1_1") (pintype "passive"))
      (node (ref "X8") (pin "21") (pinfunction "21_21") (pintype "passive"))
    )
    (net (code "88") (name "/MCC1_CMD") (class "Default")
      (node (ref "IC1") (pin "V9") (pinfunction "MMC1_CMD_V9") (pintype "bidirectional"))
      (node (ref "IC22") (pin "M5") (pinfunction "CMD_M5") (pintype "bidirectional"))
      (node (ref "R30") (pin "1") (pinfunction "1_1") (pintype "passive"))
      (node (ref "X8") (pin "20") (pinfunction "20_20") (pintype "passive"))
    )
    (net (code "89") (name "/MCC1_DAT0") (class "Default")
      (node (ref "IC1") (pin "U7") (pinfunction "MMC1_DAT0_U7") (pintype "bidirectional"))
      (node (ref "IC22") (pin "A3") (pinfunction "DAT0_A3") (pintype "bidirectional"))
      (node (ref "R12") (pin "1") (pinfunction "1_1") (pintype "passive"))
      (node (ref "X8") (pin "25") (pinfunction "25_25") (pintype "passive"))
    )
    (net (code "90") (name "/MCC1_DAT1") (class "Default")
      (node (ref "IC1") (pin "V7") (pinfunction "MMC1_DAT1_V7") (pintype "bidirectional"))
      (node (ref "IC22") (pin "A4") (pinfunction "DAT1_A4") (pintype "bidirectional"))
      (node (ref "R13") (pin "1") (pinfunction "1_1") (pintype "passive"))
      (node (ref "X8") (pin "24") (pinfunction "24_24") (pintype "passive"))
    )
    (net (code "91") (name "/MCC1_DAT2") (class "Default")
      (node (ref "IC1") (pin "R8") (pinfunction "MMC1_DAT2_R8") (pintype "bidirectional"))
      (node (ref "IC22") (pin "A5") (pinfunction "DAT2_A5") (pintype "bidirectional"))
      (node (ref "R16") (pin "1") (pinfunction "1_1") (pintype "passive"))
      (node (ref "X8") (pin "5") (pinfunction "5_5") (pintype "passive"))
    )
    (net (code "92") (name "/MCC1_DAT3") (class "Default")
      (node (ref "IC1") (pin "T8") (pinfunction "MMC1_DAT3_T8") (pintype "bidirectional"))
      (node (ref "IC22") (pin "B2") (pinfunction "DAT3_B2") (pintype "bidirectional"))
      (node (ref "R18") (pin "1") (pinfunction "1_1") (pintype "passive"))
      (node (ref "X8") (pin "6") (pinfunction "6_6") (pintype "passive"))
    )
    (net (code "93") (name "/MCC1_DAT4") (class "Default")
      (node (ref "IC1") (pin "U8") (pinfunction "MMC1_DAT4_U8") (pintype "bidirectional"))
      (node (ref "IC22") (pin "B3") (pinfunction "DAT4_B3") (pintype "bidirectional"))
      (node (ref "R20") (pin "1") (pinfunction "1_1") (pintype "passive"))
      (node (ref "X8") (pin "23") (pinfunction "23_23") (pintype "passive"))
    )
    (net (code "94") (name "/MCC1_DAT5") (class "Default")
      (node (ref "IC1") (pin "V8") (pinfunction "MMC1_DAT5_V8") (pintype "bidirectional"))
      (node (ref "IC22") (pin "B4") (pinfunction "DAT5_B4") (pintype "bidirectional"))
      (node (ref "R23") (pin "1") (pinfunction "1_1") (pintype "passive"))
      (node (ref "X8") (pin "22") (pinfunction "22_22") (pintype "passive"))
    )
    (net (code "95") (name "/MCC1_DAT6") (class "Default")
      (node (ref "IC1") (pin "R9") (pinfunction "MMC1_DAT6_R9") (pintype "bidirectional"))
      (node (ref "IC22") (pin "B5") (pinfunction "DAT6_B5") (pintype "bidirectional"))
      (node (ref "R25") (pin "1") (pinfunction "1_1") (pintype "passive"))
      (node (ref "X8") (pin "3") (pinfunction "3_3") (pintype "passive"))
    )
    (net (code "96") (name "/MCC1_DAT7") (class "Default")
      (node (ref "IC1") (pin "T9") (pinfunction "MMC1_DAT7_T9") (pintype "bidirectional"))
      (node (ref "IC22") (pin "B6") (pinfunction "DAT7_B6") (pintype "bidirectional"))
      (node (ref "R28") (pin "1") (pinfunction "1_1") (pintype "passive"))
      (node (ref "X8") (pin "4") (pinfunction "4_4") (pintype "passive"))
    )
    (net (code "97") (name "/MCU.LCD.CLK") (class "Default")
      (node (ref "IC1") (pin "V5") (pinfunction "LCD_PCLK_V5") (pintype "bidirectional"))
      (node (ref "R34") (pin "2") (pinfunction "2_2") (pintype "passive"))
    )
    (net (code "98") (name "/MCU.LCD.EN") (class "Default")
      (node (ref "IC1") (pin "R6") (pinfunction "LCD_DE_R6") (pintype "bidirectional"))
      (node (ref "R39") (pin "2") (pinfunction "2_2") (pintype "passive"))
    )
    (net (code "99") (name "/MCU.LCD.HS") (class "Default")
      (node (ref "IC1") (pin "R5") (pinfunction "LCD_HSYNC_R5") (pintype "bidirectional"))
      (node (ref "R37") (pin "2") (pinfunction "2_2") (pintype "passive"))
    )
    (net (code "100") (name "/MCU.LCD.VS") (class "Default")
      (node (ref "IC1") (pin "U5") (pinfunction "LCD_VSYNC_U5") (pintype "bidirectional"))
      (node (ref "R35") (pin "2") (pinfunction "2_2") (pintype "passive"))
    )
    (net (code "101") (name "/NC1") (class "Default")
      (node (ref "IC1") (pin "K16") (pinfunction "MII1_TXD1_K16") (pintype "bidirectional"))
    )
    (net (code "102") (name "/NC2") (class "Default")
      (node (ref "IC1") (pin "H17") (pinfunction "MII1_CRS_DV_H17") (pintype "bidirectional"))
    )
    (net (code "103") (name "/NC3") (class "Default")
      (node (ref "IC1") (pin "M16") (pinfunction "MII1_RXD0_M16") (pintype "bidirectional"))
    )
    (net (code "104") (name "/NC4") (class "Default")
      (node (ref "IC1") (pin "J15") (pinfunction "MII1_RXERR_J15") (pintype "bidirectional"))
    )
    (net (code "105") (name "/PMIC_INT") (class "Default")
      (node (ref "IC1") (pin "B18") (pinfunction "EXTIN_B18") (pintype "bidirectional"))
      (node (ref "IC1") (pin "B19") (pinfunction "PMIC_INTN_B19") (pintype "bidirectional"))
    )
    (net (code "106") (name "/PMIC_NWAKEUP") (class "Default")
      (node (ref "IC1") (pin "A19") (pinfunction "PMIC_WAKEUPN_A19") (pintype "bidirectional"))
      (node (ref "IC1") (pin "C5") (pinfunction "EXT_WAKEUP_C5") (pintype "bidirectional"))
    )
    (net (code "107") (name "/PMIC_PGOOD") (class "Default")
      (node (ref "IC1") (pin "A20") (pinfunction "PMIC_PGOOD_A20") (pintype "bidirectional"))
      (node (ref "IC1") (pin "B15") (pinfunction "PORZ_B15") (pintype "bidirectional"))
      (node (ref "IC2") (pin "2") (pinfunction "A_2") (pintype "bidirectional"))
    )
    (net (code "108") (name "/PWR_BUT") (class "Default")
      (node (ref "IC1") (pin "D20") (pinfunction "PWR_BUT_D20") (pintype "bidirectional"))
      (node (ref "POWER") (pin "3") (pinfunction "3_3") (pintype "bidirectional"))
      (node (ref "POWER") (pin "4") (pinfunction "4_4") (pintype "bidirectional"))
      (node (ref "X9") (pin "9") (pinfunction "9_9") (pintype "passive"))
    )
    (net (code "109") (name "/RX<-TX") (class "Default")
      (node (ref "IC17") (pin "3") (pinfunction "2Y_3") (pintype "bidirectional"))
      (node (ref "X1") (pin "5") (pinfunction "5_5") (pintype "passive"))
    )
    (net (code "110") (name "/SD.CD") (class "Default")
      (node (ref "IC1") (pin "C15") (pinfunction "MMC0_CD_C15") (pintype "bidirectional"))
      (node (ref "JTAG1") (pin "19") (pinfunction "EMU4_19") (pintype "bidirectional"))
      (node (ref "R7") (pin "1") (pinfunction "1_1") (pintype "passive"))
      (node (ref "X2") (pin "CD") (pinfunction "CD#_CD") (pintype "bidirectional"))
    )
    (net (code "111") (name "/SD.CLK") (class "Default")
      (node (ref "IC1") (pin "G17") (pinfunction "MMC0_CLK0_G17") (pintype "bidirectional"))
      (node (ref "R3") (pin "1") (pinfunction "1_1") (pintype "passive"))
      (node (ref "X2") (pin "5") (pinfunction "CLK_5") (pintype "bidirectional"))
    )
    (net (code "112") (name "/SD.CMD") (class "Default")
      (node (ref "IC1") (pin "G18") (pinfunction "MMC0_CMD_G18") (pintype "bidirectional"))
      (node (ref "R4") (pin "1") (pinfunction "1_1") (pintype "passive"))
      (node (ref "X2") (pin "3") (pinfunction "CMD/DI_3") (pintype "bidirectional"))
    )
    (net (code "113") (name "/SD.D0") (class "Default")
      (node (ref "IC1") (pin "G16") (pinfunction "MMC0_DAT0_G16") (pintype "bidirectional"))
      (node (ref "R2") (pin "1") (pinfunction "1_1") (pintype "passive"))
      (node (ref "X2") (pin "7") (pinfunction "DAT0/DO_7") (pintype "bidirectional"))
    )
    (net (code "114") (name "/SD.D1") (class "Default")
      (node (ref "IC1") (pin "G15") (pinfunction "MMC0_DAT1_G15") (pintype "bidirectional"))
      (node (ref "R1") (pin "1") (pinfunction "1_1") (pintype "passive"))
      (node (ref "X2") (pin "8") (pinfunction "DAT1_8") (pintype "bidirectional"))
    )
    (net (code "115") (name "/SD.D2") (class "Default")
      (node (ref "IC1") (pin "F18") (pinfunction "MMC0_DAT2_F18") (pintype "bidirectional"))
      (node (ref "R6") (pin "1") (pinfunction "1_1") (pintype "passive"))
      (node (ref "X2") (pin "1") (pinfunction "DAT2_1") (pintype "bidirectional"))
    )
    (net (code "116") (name "/SD.D3") (class "Default")
      (node (ref "IC1") (pin "F17") (pinfunction "MMC0_DAT3_F17") (pintype "bidirectional"))
      (node (ref "R5") (pin "1") (pinfunction "1_1") (pintype "passive"))
      (node (ref "X2") (pin "2") (pinfunction "DAT3/CS_2") (pintype "bidirectional"))
    )
    (net (code "117") (name "/SELECT_5V") (class "Default")
      (node (ref "D2") (pin "K") (pinfunction "K_K") (pintype "bidirectional"))
      (node (ref "D3") (pin "K") (pinfunction "K_K") (pintype "bidirectional"))
      (node (ref "D4") (pin "K") (pinfunction "K_K") (pintype "bidirectional"))
      (node (ref "FB1") (pin "1") (pinfunction "P$1_1") (pintype "bidirectional"))
      (node (ref "R97") (pin "1") (pinfunction "1_1") (pintype "passive"))
      (node (ref "TP23") (pin "TP") (pinfunction "TP_TP") (pintype "input"))
    )
    (net (code "118") (name "/SLOW_CLK") (class "Default")
      (node (ref "IC11") (pin "5") (pinfunction "A4_5") (pintype "bidirectional"))
      (node (ref "R91") (pin "1") (pinfunction "1_1") (pintype "passive"))
    )
    (net (code "119") (name "/SPI1_CS0") (class "Default")
      (node (ref "IC1") (pin "C12") (pinfunction "SPI1_CS0_C12") (pintype "bidirectional"))
      (node (ref "IC9") (pin "25") (pinfunction "AP1_25") (pintype "bidirectional"))
      (node (ref "X9") (pin "28") (pinfunction "28_28") (pintype "passive"))
    )
    (net (code "120") (name "/SPI1_D0") (class "Default")
      (node (ref "IC1") (pin "B13") (pinfunction "SPI1_D0_B13") (pintype "bidirectional"))
      (node (ref "IC9") (pin "24") (pinfunction "AP0_24") (pintype "bidirectional"))
      (node (ref "X9") (pin "29") (pinfunction "29_29") (pintype "passive"))
    )
    (net (code "121") (name "/SPI1_D1") (class "Default")
      (node (ref "IC1") (pin "D12") (pinfunction "SPI1_D1_D12") (pintype "bidirectional"))
      (node (ref "X9") (pin "30") (pinfunction "30_30") (pintype "passive"))
    )
    (net (code "122") (name "/SPI1_SCLK") (class "Default")
      (node (ref "IC1") (pin "A13") (pinfunction "SPI1_CLK_A13") (pintype "bidirectional"))
      (node (ref "IC9") (pin "23") (pinfunction "ACLK_23") (pintype "bidirectional"))
      (node (ref "X9") (pin "31") (pinfunction "31_31") (pintype "passive"))
    )
    (net (code "123") (name "/SYS_RESET#") (class "Default")
      (node (ref "C16") (pin "1") (pinfunction "1_1") (pintype "passive"))
      (node (ref "C21") (pin "1") (pinfunction "1_1") (pintype "passive"))
      (node (ref "IC1") (pin "A10") (pinfunction "SYS_RESETN_A10") (pintype "bidirectional"))
      (node (ref "IC2") (pin "4") (pinfunction "Y_4") (pintype "bidirectional"))
      (node (ref "JTAG1") (pin "15") (pinfunction "SRST_15") (pintype "bidirectional"))
      (node (ref "R32") (pin "2") (pinfunction "2_2") (pintype "passive"))
      (node (ref "RESET") (pin "3") (pinfunction "3_3") (pintype "bidirectional"))
      (node (ref "RESET") (pin "4") (pinfunction "4_4") (pintype "bidirectional"))
      (node (ref "X9") (pin "10") (pinfunction "10_10") (pintype "passive"))
    )
    (net (code "124") (name "/TEST") (class "Default")
      (node (ref "IC9") (pin "49") (pinfunction "TEST_49") (pintype "bidirectional"))
      (node (ref "R114") (pin "2") (pinfunction "2_2") (pintype "passive"))
    )
    (net (code "125") (name "/TIMER4") (class "Default")
      (node (ref "IC1") (pin "R7") (pinfunction "TIMER4_R7") (pintype "bidirectional"))
      (node (ref "X8") (pin "7") (pinfunction "7_7") (pintype "passive"))
    )
    (net (code "126") (name "/TIMER5") (class "Default")
      (node (ref "IC1") (pin "T6") (pinfunction "TIMER5_T6") (pintype "bidirectional"))
      (node (ref "X8") (pin "9") (pinfunction "9_9") (pintype "passive"))
    )
    (net (code "127") (name "/TIMER6") (class "Default")
      (node (ref "IC1") (pin "U6") (pinfunction "TIMER6_U6") (pintype "bidirectional"))
      (node (ref "X8") (pin "10") (pinfunction "10_10") (pintype "passive"))
    )
    (net (code "128") (name "/TIMER7") (class "Default")
      (node (ref "IC1") (pin "T7") (pinfunction "TIMER7_T7") (pintype "bidirectional"))
      (node (ref "X8") (pin "8") (pinfunction "8_8") (pintype "passive"))
    )
    (net (code "129") (name "/TX->RX") (class "Default")
      (node (ref "IC17") (pin "2") (pinfunction "1A_2") (pintype "bidirectional"))
      (node (ref "R123") (pin "1") (pinfunction "1_1") (pintype "passive"))
      (node (ref "X1") (pin "4") (pinfunction "4_4") (pintype "passive"))
    )
    (net (code "130") (name "/TX0+") (class "Default")
      (node (ref "IC8") (pin "5") (pinfunction "TMDS.CH2+_5") (pintype "bidirectional"))
      (node (ref "IC9") (pin "40") (pinfunction "TX0+_40") (pintype "bidirectional"))
      (node (ref "X5") (pin "9") (pinfunction "TMDS.DATA0+_9") (pintype "bidirectional"))
    )
    (net (code "131") (name "/TX0-") (class "Default")
      (node (ref "IC8") (pin "4") (pinfunction "TMDS.CH2-_4") (pintype "bidirectional"))
      (node (ref "IC9") (pin "39") (pinfunction "TX0-_39") (pintype "bidirectional"))
      (node (ref "X5") (pin "11") (pinfunction "TMDS.DATA0-_11") (pintype "bidirectional"))
    )
    (net (code "132") (name "/TX1+") (class "Default")
      (node (ref "IC7") (pin "2") (pinfunction "TMDS.CH1+_2") (pintype "bidirectional"))
      (node (ref "IC9") (pin "43") (pinfunction "TX1+_43") (pintype "bidirectional"))
      (node (ref "X5") (pin "6") (pinfunction "TMDS.DATA1+_6") (pintype "bidirectional"))
    )
    (net (code "133") (name "/TX1-") (class "Default")
      (node (ref "IC7") (pin "1") (pinfunction "TMDS.CH1-_1") (pintype "bidirectional"))
      (node (ref "IC9") (pin "42") (pinfunction "TX1-_42") (pintype "bidirectional"))
      (node (ref "X5") (pin "8") (pinfunction "TMDS.DATA1-_8") (pintype "bidirectional"))
    )
    (net (code "134") (name "/TX2+") (class "Default")
      (node (ref "IC7") (pin "5") (pinfunction "TMDS.CH2+_5") (pintype "bidirectional"))
      (node (ref "IC9") (pin "45") (pinfunction "TX2+_45") (pintype "bidirectional"))
      (node (ref "X5") (pin "3") (pinfunction "TMDS.DATA2+_3") (pintype "bidirectional"))
    )
    (net (code "135") (name "/TX2-") (class "Default")
      (node (ref "IC7") (pin "4") (pinfunction "TMDS.CH2-_4") (pintype "bidirectional"))
      (node (ref "IC9") (pin "44") (pinfunction "TX2-_44") (pintype "bidirectional"))
      (node (ref "X5") (pin "5") (pinfunction "TMDS.DATA2-_5") (pintype "bidirectional"))
    )
    (net (code "136") (name "/TXC+") (class "Default")
      (node (ref "IC8") (pin "2") (pinfunction "TMDS.CH1+_2") (pintype "bidirectional"))
      (node (ref "IC9") (pin "38") (pinfunction "TXC+_38") (pintype "bidirectional"))
      (node (ref "X5") (pin "12") (pinfunction "TMDS.CLOCK+_12") (pintype "bidirectional"))
    )
    (net (code "137") (name "/TXC-") (class "Default")
      (node (ref "IC8") (pin "1") (pinfunction "TMDS.CH1-_1") (pintype "bidirectional"))
      (node (ref "IC9") (pin "37") (pinfunction "TXC-_37") (pintype "bidirectional"))
      (node (ref "X5") (pin "14") (pinfunction "TMDS.CLOCK-_14") (pintype "bidirectional"))
    )
    (net (code "138") (name "/UART0_RST#") (class "Default")
      (node (ref "IC1") (pin "E17") (pinfunction "UART0_RSTN_E17") (pintype "bidirectional"))
      (node (ref "TP6") (pin "TP") (pinfunction "TP_TP") (pintype "input"))
    )
    (net (code "139") (name "/UART0_RXD") (class "Default")
      (node (ref "IC1") (pin "E15") (pinfunction "UART0_RXD_E15") (pintype "bidirectional"))
      (node (ref "IC17") (pin "6") (pinfunction "1Y_6") (pintype "bidirectional"))
    )
    (net (code "140") (name "/UART0_TXD") (class "Default")
      (node (ref "IC1") (pin "E16") (pinfunction "UART0_TXD_E16") (pintype "bidirectional"))
      (node (ref "IC17") (pin "5") (pinfunction "2A_5") (pintype "bidirectional"))
    )
    (net (code "141") (name "/UART1_RXD") (class "Default")
      (node (ref "IC1") (pin "D16") (pinfunction "UART1_RXD_D16") (pintype "bidirectional"))
      (node (ref "X9") (pin "26") (pinfunction "26_26") (pintype "passive"))
    )
    (net (code "142") (name "/UART1_TXD") (class "Default")
      (node (ref "IC1") (pin "D15") (pinfunction "UART1_TXD_D15") (pintype "bidirectional"))
      (node (ref "X9") (pin "24") (pinfunction "24_24") (pintype "passive"))
    )
    (net (code "143") (name "/UART2_RXD") (class "Default")
      (node (ref "IC1") (pin "A17") (pinfunction "UART2_RXD_A17") (pintype "bidirectional"))
      (node (ref "X9") (pin "22") (pinfunction "22_22") (pintype "passive"))
    )
    (net (code "144") (name "/UART2_TXD") (class "Default")
      (node (ref "IC1") (pin "B17") (pinfunction "UART2_TXD_B17") (pintype "bidirectional"))
      (node (ref "X9") (pin "21") (pinfunction "21_21") (pintype "passive"))
    )
    (net (code "145") (name "/UART4_RXD") (class "Default")
      (node (ref "IC1") (pin "T17") (pinfunction "UART4_RXD_T17") (pintype "bidirectional"))
      (node (ref "X9") (pin "11") (pinfunction "11_11") (pintype "passive"))
    )
    (net (code "146") (name "/UART4_TXD") (class "Default")
      (node (ref "IC1") (pin "U17") (pinfunction "UART4_TXD_U17") (pintype "bidirectional"))
      (node (ref "X9") (pin "13") (pinfunction "13_13") (pintype "passive"))
    )
    (net (code "147") (name "/USB.CLIENT.D+") (class "Default")
      (node (ref "IC1") (pin "N17") (pinfunction "USB0_DP_N17") (pintype "bidirectional"))
      (node (ref "IC14") (pin "1") (pinfunction "D+_1") (pintype "bidirectional"))
      (node (ref "X4") (pin "D+") (pinfunction "D+_D+") (pintype "input"))
    )
    (net (code "148") (name "/USB.CLIENT.D-") (class "Default")
      (node (ref "IC1") (pin "N18") (pinfunction "USB0_DM_N18") (pintype "bidirectional"))
      (node (ref "IC14") (pin "2") (pinfunction "D-_2") (pintype "bidirectional"))
      (node (ref "X4") (pin "D-") (pinfunction "D-_D-") (pintype "input"))
    )
    (net (code "149") (name "/USB.CLIENT.ID") (class "Default")
      (node (ref "IC1") (pin "P16") (pinfunction "USB0_ID_P16") (pintype "bidirectional"))
      (node (ref "IC14") (pin "3") (pinfunction "ID_3") (pintype "bidirectional"))
      (node (ref "X4") (pin "ID") (pinfunction "ID_ID") (pintype "input"))
    )
    (net (code "150") (name "/USB.HOST.D+") (class "Default")
      (node (ref "IC1") (pin "R17") (pinfunction "USB1_DP_R17") (pintype "bidirectional"))
      (node (ref "IC15") (pin "1") (pinfunction "D+_1") (pintype "bidirectional"))
      (node (ref "X3") (pin "3") (pinfunction "D+_3") (pintype "bidirectional"))
    )
    (net (code "151") (name "/USB.HOST.D-") (class "Default")
      (node (ref "IC1") (pin "R18") (pinfunction "USB1_DM_R18") (pintype "bidirectional"))
      (node (ref "IC15") (pin "2") (pinfunction "D-_2") (pintype "bidirectional"))
      (node (ref "X3") (pin "2") (pinfunction "D-_2") (pintype "bidirectional"))
    )
    (net (code "152") (name "/USB1_DRVVBUS") (class "Default")
      (node (ref "IC1") (pin "F15") (pinfunction "USB1_DRVVBUS_F15") (pintype "bidirectional"))
      (node (ref "IC12") (pin "4") (pinfunction "EN#_4") (pintype "bidirectional"))
      (node (ref "R19") (pin "1") (pinfunction "1_1") (pintype "passive"))
    )
    (net (code "153") (name "/USB1_OC#") (class "Default")
      (node (ref "IC1") (pin "T16") (pinfunction "(USB1_OCN)GPIO1_26_T16") (pintype "bidirectional"))
      (node (ref "IC12") (pin "5") (pinfunction "OC#_5") (pintype "bidirectional"))
      (node (ref "R122") (pin "2") (pinfunction "2_2") (pintype "passive"))
    )
    (net (code "154") (name "/USB1_VBUS") (class "Default")
      (node (ref "FB4") (pin "2") (pinfunction "P$2_2") (pintype "bidirectional"))
      (node (ref "IC1") (pin "T18") (pinfunction "USB1_VBUS_T18") (pintype "bidirectional"))
    )
    (net (code "155") (name "/USR0") (class "Default")
      (node (ref "IC1") (pin "V15") (pinfunction "USR0_V15") (pintype "bidirectional"))
      (node (ref "R104") (pin "2") (pinfunction "2_2") (pintype "passive"))
    )
    (net (code "156") (name "/USR1") (class "Default")
      (node (ref "IC1") (pin "U15") (pinfunction "USR1_U15") (pintype "bidirectional"))
      (node (ref "R100") (pin "2") (pinfunction "2_2") (pintype "passive"))
    )
    (net (code "157") (name "/USR2") (class "Default")
      (node (ref "IC1") (pin "T15") (pinfunction "USR2_T15") (pintype "bidirectional"))
      (node (ref "R96") (pin "2") (pinfunction "2_2") (pintype "passive"))
    )
    (net (code "158") (name "/USR3") (class "Default")
      (node (ref "IC1") (pin "V16") (pinfunction "USR3_V16") (pintype "bidirectional"))
      (node (ref "R92") (pin "2") (pinfunction "2_2") (pintype "passive"))
    )
    (net (code "159") (name "/VIN_BAT") (class "Default")
      (node (ref "IC1") (pin "Y2") (pinfunction "BAT_1_Y2") (pintype "bidirectional"))
      (node (ref "IC1") (pin "Y3") (pinfunction "BAT_2_Y3") (pintype "bidirectional"))
      (node (ref "TP2") (pin "P$1") (pinfunction "TP_P$1") (pintype "bidirectional"))
    )
    (net (code "160") (name "/WL_EN") (class "Default")
      (node (ref "IC11") (pin "3") (pinfunction "A2_3") (pintype "bidirectional"))
      (node (ref "MOD1") (pin "40") (pinfunction "WLAN_EN_40") (pintype "bidirectional"))
      (node (ref "R10") (pin "1") (pinfunction "1_1") (pintype "passive"))
      (node (ref "T3") (pin "G") (pinfunction "G_G") (pintype "bidirectional"))
    )
    (net (code "161") (name "/WL_EN.SIP") (class "Default")
      (node (ref "IC1") (pin "K18") (pinfunction "MII1_TXCLK_K18") (pintype "bidirectional"))
      (node (ref "R136") (pin "1") (pinfunction "1_1") (pintype "passive"))
    )
    (net (code "162") (name "/WL_IRQ") (class "Default")
      (node (ref "IC11") (pin "9") (pinfunction "A8_9") (pintype "bidirectional"))
      (node (ref "R60") (pin "2") (pinfunction "2_2") (pintype "passive"))
    )
    (net (code "163") (name "/WL_IRQ.SIP") (class "Default")
      (node (ref "IC1") (pin "H18") (pinfunction "MII1_REFCLK_H18") (pintype "bidirectional"))
      (node (ref "R134") (pin "1") (pinfunction "1_1") (pintype "passive"))
    )
    (net (code "164") (name "/WL_SDIO_CLK") (class "Default")
      (node (ref "IC10") (pin "6") (pinfunction "A5_6") (pintype "bidirectional"))
      (node (ref "R103") (pin "2") (pinfunction "2_2") (pintype "passive"))
      (node (ref "R64") (pin "2") (pinfunction "2_2") (pintype "passive"))
    )
    (net (code "165") (name "/WL_SDIO_CLK.SIP") (class "Default")
      (node (ref "IC1") (pin "L15") (pinfunction "MII1_RXD1_L15") (pintype "bidirectional"))
      (node (ref "R126") (pin "1") (pinfunction "1_1") (pintype "passive"))
    )
    (net (code "166") (name "/WL_SDIO_CMD") (class "Default")
      (node (ref "IC10") (pin "7") (pinfunction "A6_7") (pintype "bidirectional"))
      (node (ref "R105") (pin "2") (pinfunction "2_2") (pintype "passive"))
      (node (ref "R62") (pin "2") (pinfunction "2_2") (pintype "passive"))
    )
    (net (code "167") (name "/WL_SDIO_CMD.SIP") (class "Default")
      (node (ref "IC1") (pin "J16") (pinfunction "MII1_TXEN_J16") (pintype "bidirectional"))
      (node (ref "R86") (pin "1") (pinfunction "1_1") (pintype "passive"))
    )
    (net (code "168") (name "/WL_SDIO_D0") (class "Default")
      (node (ref "IC10") (pin "1") (pinfunction "A1_1") (pintype "bidirectional"))
      (node (ref "R66") (pin "2") (pinfunction "2_2") (pintype "passive"))
      (node (ref "R98") (pin "2") (pinfunction "2_2") (pintype "passive"))
    )
    (net (code "169") (name "/WL_SDIO_D0.SIP") (class "Default")
      (node (ref "IC1") (pin "J17") (pinfunction "MII1_RXDV_J17") (pintype "bidirectional"))
      (node (ref "R130") (pin "1") (pinfunction "1_1") (pintype "passive"))
    )
    (net (code "170") (name "/WL_SDIO_D1") (class "Default")
      (node (ref "IC10") (pin "3") (pinfunction "A2_3") (pintype "bidirectional"))
      (node (ref "R68") (pin "2") (pinfunction "2_2") (pintype "passive"))
      (node (ref "R99") (pin "2") (pinfunction "2_2") (pintype "passive"))
    )
    (net (code "171") (name "/WL_SDIO_D1.SIP") (class "Default")
      (node (ref "IC1") (pin "J18") (pinfunction "MII1_TXD3_J18") (pintype "bidirectional"))
      (node (ref "R129") (pin "1") (pinfunction "1_1") (pintype "passive"))
    )
    (net (code "172") (name "/WL_SDIO_D2") (class "Default")
      (node (ref "IC10") (pin "4") (pinfunction "A3_4") (pintype "bidirectional"))
      (node (ref "R101") (pin "2") (pinfunction "2_2") (pintype "passive"))
      (node (ref "R70") (pin "2") (pinfunction "2_2") (pintype "passive"))
    )
    (net (code "173") (name "/WL_SDIO_D2.SIP") (class "Default")
      (node (ref "IC1") (pin "K15") (pinfunction "MII1_TXD2_K15") (pintype "bidirectional"))
      (node (ref "R128") (pin "1") (pinfunction "1_1") (pintype "passive"))
    )
    (net (code "174") (name "/WL_SDIO_D3") (class "Default")
      (node (ref "IC10") (pin "5") (pinfunction "A4_5") (pintype "bidirectional"))
      (node (ref "R102") (pin "2") (pinfunction "2_2") (pintype "passive"))
      (node (ref "R72") (pin "2") (pinfunction "2_2") (pintype "passive"))
    )
    (net (code "175") (name "/WL_SDIO_D3.SIP") (class "Default")
      (node (ref "IC1") (pin "H16") (pinfunction "MII1_COL_H16") (pintype "bidirectional"))
      (node (ref "R127") (pin "1") (pinfunction "1_1") (pintype "passive"))
    )
    (net (code "176") (name "/XDMA_EVENT_INTRO") (class "Default")
      (node (ref "IC13") (pin "1") (pinfunction "CLK_1") (pintype "bidirectional"))
      (node (ref "JTAG1") (pin "17") (pinfunction "EMU2_17") (pintype "bidirectional"))
      (node (ref "R9") (pin "2") (pinfunction "2_2") (pintype "passive"))
    )
    (net (code "177") (name "1.8V-WIFI") (class "Default")
      (node (ref "C11") (pin "+") (pinfunction "+_+") (pintype "passive"))
      (node (ref "C24") (pin "1") (pinfunction "1_1") (pintype "passive"))
      (node (ref "C25") (pin "1") (pinfunction "1_1") (pintype "passive"))
      (node (ref "C43") (pin "1") (pinfunction "1_1") (pintype "passive"))
      (node (ref "C64") (pin "1") (pinfunction "1_1") (pintype "passive"))
      (node (ref "C8") (pin "1") (pinfunction "1_1") (pintype "passive"))
      (node (ref "IC10") (pin "2") (pinfunction "VCCA_2") (pintype "bidirectional"))
      (node (ref "IC11") (pin "2") (pinfunction "VCCA_2") (pintype "bidirectional"))
      (node (ref "IC19") (pin "5") (pinfunction "VOUT_5") (pintype "bidirectional"))
      (node (ref "MOD1") (pin "38") (pinfunction "VIO_38") (pintype "bidirectional"))
      (node (ref "OSC2") (pin "4") (pinfunction "VCC_4") (pintype "bidirectional"))
      (node (ref "R101") (pin "1") (pinfunction "1_1") (pintype "passive"))
      (node (ref "R102") (pin "1") (pinfunction "1_1") (pintype "passive"))
      (node (ref "R103") (pin "1") (pinfunction "1_1") (pintype "passive"))
      (node (ref "R105") (pin "1") (pinfunction "1_1") (pintype "passive"))
      (node (ref "R111") (pin "1") (pinfunction "1_1") (pintype "passive"))
      (node (ref "R90") (pin "1") (pinfunction "1_1") (pintype "passive"))
      (node (ref "R98") (pin "1") (pinfunction "1_1") (pintype "passive"))
      (node (ref "R99") (pin "1") (pinfunction "1_1") (pintype "passive"))
    )
    (net (code "178") (name "3.3V-WIFI") (class "Default")
      (node (ref "C10") (pin "1") (pinfunction "1_1") (pintype "passive"))
      (node (ref "C20") (pin "1") (pinfunction "1_1") (pintype "passive"))
      (node (ref "C23") (pin "+") (pinfunction "+_+") (pintype "passive"))
      (node (ref "C44") (pin "1") (pinfunction "1_1") (pintype "passive"))
      (node (ref "C45") (pin "1") (pinfunction "1_1") (pintype "passive"))
      (node (ref "C61") (pin "1") (pinfunction "1_1") (pintype "passive"))
      (node (ref "C63") (pin "1") (pinfunction "1_1") (pintype "passive"))
      (node (ref "IC10") (pin "19") (pinfunction "VCCB_19") (pintype "bidirectional"))
      (node (ref "IC11") (pin "19") (pinfunction "VCCB_19") (pintype "bidirectional"))
      (node (ref "IC18") (pin "4") (pinfunction "OUT_4") (pintype "bidirectional"))
      (node (ref "IC19") (pin "1") (pinfunction "VIN_1") (pintype "bidirectional"))
      (node (ref "IC19") (pin "3") (pinfunction "EN_3") (pintype "bidirectional"))
      (node (ref "MOD1") (pin "46") (pinfunction "VBAT_IN1_46") (pintype "bidirectional"))
      (node (ref "MOD1") (pin "47") (pinfunction "VBAT_IN2_47") (pintype "bidirectional"))
      (node (ref "R124") (pin "2") (pinfunction "2_2") (pintype "passive"))
      (node (ref "R125") (pin "2") (pinfunction "2_2") (pintype "passive"))
      (node (ref "R93") (pin "1") (pinfunction "1_1") (pintype "passive"))
    )
    (net (code "179") (name "AGND") (class "Default")
      (node (ref "IC1") (pin "A6") (pinfunction "AGND_1_A6") (pintype "bidirectional"))
      (node (ref "IC1") (pin "A9") (pinfunction "AGND_0_A9") (pintype "bidirectional"))
      (node (ref "IC1") (pin "E8") (pinfunction "AGND_E8") (pintype "bidirectional"))
      (node (ref "X9") (pin "34") (pinfunction "34_34") (pintype "passive"))
    )
    (net (code "180") (name "CGND") (class "Default")
      (node (ref "MGT1") (pin "P$1") (pinfunction "P$1_P$1") (pintype "bidirectional"))
      (node (ref "MGT2") (pin "P$1") (pinfunction "P$1_P$1") (pintype "bidirectional"))
      (node (ref "MGT3") (pin "P$1") (pinfunction "P$1_P$1") (pintype "bidirectional"))
      (node (ref "MGT4") (pin "P$1") (pinfunction "P$1_P$1") (pintype "bidirectional"))
      (node (ref "R17") (pin "2") (pinfunction "2_2") (pintype "passive"))
      (node (ref "X2") (pin "CGND1") (pinfunction "CGND1_CGND1") (pintype "bidirectional"))
      (node (ref "X2") (pin "CGND2") (pinfunction "CGND2_CGND2") (pintype "bidirectional"))
      (node (ref "X2") (pin "CGND3") (pinfunction "CGND3_CGND3") (pintype "bidirectional"))
      (node (ref "X2") (pin "CGND4") (pinfunction "CGND4_CGND4") (pintype "bidirectional"))
      (node (ref "X2") (pin "CGND5") (pinfunction "CGND5_CGND5") (pintype "bidirectional"))
      (node (ref "X2") (pin "CGND6") (pinfunction "CGND6_CGND6") (pintype "bidirectional"))
      (node (ref "X3") (pin "5") (pinfunction "CG1_5") (pintype "bidirectional"))
      (node (ref "X3") (pin "6") (pinfunction "CG2_6") (pintype "bidirectional"))
      (node (ref "X4") (pin "CGND1") (pinfunction "SGND1_CGND1") (pintype "bidirectional"))
      (node (ref "X4") (pin "CGND2") (pinfunction "SGND2_CGND2") (pintype "bidirectional"))
      (node (ref "X4") (pin "CGND3") (pinfunction "SGND3_CGND3") (pintype "bidirectional"))
      (node (ref "X4") (pin "CGND4") (pinfunction "SGND4_CGND4") (pintype "bidirectional"))
      (node (ref "X4") (pin "CGND5") (pinfunction "SGND5_CGND5") (pintype "bidirectional"))
      (node (ref "X4") (pin "CGND6") (pinfunction "SGND6_CGND6") (pintype "bidirectional"))
      (node (ref "X5") (pin "CG1") (pinfunction "CG1_CG1") (pintype "bidirectional"))
      (node (ref "X5") (pin "CG2") (pinfunction "CG2_CG2") (pintype "bidirectional"))
      (node (ref "X5") (pin "CG3") (pinfunction "CG3_CG3") (pintype "bidirectional"))
      (node (ref "X5") (pin "CG4") (pinfunction "CG4_CG4") (pintype "bidirectional"))
    )
    (net (code "181") (name "GND") (class "Default")
      (node (ref "ANT1") (pin "GND1") (pinfunction "GND1_GND1") (pintype "bidirectional"))
      (node (ref "ANT1") (pin "GND2") (pinfunction "GND2_GND2") (pintype "bidirectional"))
      (node (ref "ANT2") (pin "GND1") (pinfunction "GND1_GND1") (pintype "bidirectional"))
      (node (ref "ANT2") (pin "GND2") (pinfunction "GND2_GND2") (pintype "bidirectional"))
      (node (ref "C1") (pin "2") (pinfunction "2_2") (pintype "passive"))
      (node (ref "C10") (pin "2") (pinfunction "2_2") (pintype "passive"))
      (node (ref "C11") (pin "-") (pinfunction "-_-") (pintype "passive"))
      (node (ref "C12") (pin "2") (pinfunction "2_2") (pintype "passive"))
      (node (ref "C13") (pin "2") (pinfunction "2_2") (pintype "passive"))
      (node (ref "C14") (pin "2") (pinfunction "2_2") (pintype "passive"))
      (node (ref "C15") (pin "2") (pinfunction "2_2") (pintype "passive"))
      (node (ref "C16") (pin "2") (pinfunction "2_2") (pintype "passive"))
      (node (ref "C17") (pin "2") (pinfunction "2_2") (pintype "passive"))
      (node (ref "C18") (pin "2") (pinfunction "2_2") (pintype "passive"))
      (node (ref "C19") (pin "2") (pinfunction "2_2") (pintype "passive"))
      (node (ref "C2") (pin "2") (pinfunction "2_2") (pintype "passive"))
      (node (ref "C20") (pin "2") (pinfunction "2_2") (pintype "passive"))
      (node (ref "C21") (pin "2") (pinfunction "2_2") (pintype "passive"))
      (node (ref "C22") (pin "2") (pinfunction "2_2") (pintype "passive"))
      (node (ref "C23") (pin "-") (pinfunction "-_-") (pintype "passive"))
      (node (ref "C24") (pin "2") (pinfunction "2_2") (pintype "passive"))
      (node (ref "C25") (pin "2") (pinfunction "2_2") (pintype "passive"))
      (node (ref "C27") (pin "2") (pinfunction "2_2") (pintype "passive"))
      (node (ref "C28") (pin "2") (pinfunction "2_2") (pintype "passive"))
      (node (ref "C29") (pin "2") (pinfunction "2_2") (pintype "passive"))
      (node (ref "C30") (pin "2") (pinfunction "2_2") (pintype "passive"))
      (node (ref "C31") (pin "2") (pinfunction "2_2") (pintype "passive"))
      (node (ref "C32") (pin "2") (pinfunction "2_2") (pintype "passive"))
      (node (ref "C33") (pin "2") (pinfunction "2_2") (pintype "passive"))
      (node (ref "C34") (pin "2") (pinfunction "2_2") (pintype "passive"))
      (node (ref "C35") (pin "2") (pinfunction "2_2") (pintype "passive"))
      (node (ref "C36") (pin "2") (pinfunction "2_2") (pintype "passive"))
      (node (ref "C37") (pin "2") (pinfunction "2_2") (pintype "passive"))
      (node (ref "C38") (pin "2") (pinfunction "2_2") (pintype "passive"))
      (node (ref "C39") (pin "2") (pinfunction "2_2") (pintype "passive"))
      (node (ref "C40") (pin "2") (pinfunction "2_2") (pintype "passive"))
      (node (ref "C41") (pin "2") (pinfunction "2_2") (pintype "passive"))
      (node (ref "C42") (pin "2") (pinfunction "2_2") (pintype "passive"))
      (node (ref "C43") (pin "2") (pinfunction "2_2") (pintype "passive"))
      (node (ref "C44") (pin "2") (pinfunction "2_2") (pintype "passive"))
      (node (ref "C45") (pin "2") (pinfunction "2_2") (pintype "passive"))
      (node (ref "C47") (pin "2") (pinfunction "2_2") (pintype "passive"))
      (node (ref "C48") (pin "2") (pinfunction "2_2") (pintype "passive"))
      (node (ref "C49") (pin "2") (pinfunction "2_2") (pintype "passive"))
      (node (ref "C50") (pin "2") (pinfunction "2_2") (pintype "passive"))
      (node (ref "C51") (pin "2") (pinfunction "2_2") (pintype "passive"))
      (node (ref "C52") (pin "2") (pinfunction "2_2") (pintype "passive"))
      (node (ref "C53") (pin "2") (pinfunction "2_2") (pintype "passive"))
      (node (ref "C54") (pin "2") (pinfunction "2_2") (pintype "passive"))
      (node (ref "C55") (pin "2") (pinfunction "2_2") (pintype "passive"))
      (node (ref "C56") (pin "2") (pinfunction "2_2") (pintype "passive"))
      (node (ref "C57") (pin "2") (pinfunction "2_2") (pintype "passive"))
      (node (ref "C58") (pin "2") (pinfunction "2_2") (pintype "passive"))
      (node (ref "C59") (pin "2") (pinfunction "2_2") (pintype "passive"))
      (node (ref "C61") (pin "2") (pinfunction "2_2") (pintype "passive"))
      (node (ref "C62") (pin "-") (pinfunction "-_-") (pintype "passive"))
      (node (ref "C63") (pin "2") (pinfunction "2_2") (pintype "passive"))
      (node (ref "C64") (pin "2") (pinfunction "2_2") (pintype "passive"))
      (node (ref "C69") (pin "2") (pinfunction "2_2") (pintype "passive"))
      (node (ref "C7") (pin "2") (pinfunction "2_2") (pintype "passive"))
      (node (ref "C8") (pin "2") (pinfunction "2_2") (pintype "passive"))
      (node (ref "C9") (pin "2") (pinfunction "2_2") (pintype "passive"))
      (node (ref "D8") (pin "2") (pinfunction "A2_2") (pintype "passive"))
      (node (ref "IC1") (pin "A1") (pinfunction "DGND1_A1") (pintype "bidirectional"))
      (node (ref "IC1") (pin "A18") (pinfunction "DGND2_A18") (pintype "bidirectional"))
      (node (ref "IC1") (pin "E19") (pinfunction "DGND3_E19") (pintype "bidirectional"))
      (node (ref "IC1") (pin "E20") (pinfunction "DGND4_E20") (pintype "bidirectional"))
      (node (ref "IC1") (pin "F19") (pinfunction "DGND6_F19") (pintype "bidirectional"))
      (node (ref "IC1") (pin "F8") (pinfunction "DGND5_F8") (pintype "bidirectional"))
      (node (ref "IC1") (pin "G11") (pinfunction "DGND9_G11") (pintype "bidirectional"))
      (node (ref "IC1") (pin "G12") (pinfunction "DGND10_G12") (pintype "bidirectional"))
      (node (ref "IC1") (pin "G19") (pinfunction "DGND11_G19") (pintype "bidirectional"))
      (node (ref "IC1") (pin "G8") (pinfunction "DGND7_G8") (pintype "bidirectional"))
      (node (ref "IC1") (pin "G9") (pinfunction "DGND8_G9") (pintype "bidirectional"))
      (node (ref "IC1") (pin "H10") (pinfunction "DGND16_H10") (pintype "bidirectional"))
      (node (ref "IC1") (pin "H12") (pinfunction "DGND17_H12") (pintype "bidirectional"))
      (node (ref "IC1") (pin "H19") (pinfunction "DGND18_H19") (pintype "bidirectional"))
      (node (ref "IC1") (pin "H6") (pinfunction "DGND12_H6") (pintype "bidirectional"))
      (node (ref "IC1") (pin "H7") (pinfunction "DGND13_H7") (pintype "bidirectional"))
      (node (ref "IC1") (pin "H8") (pinfunction "DGND14_H8") (pintype "bidirectional"))
      (node (ref "IC1") (pin "H9") (pinfunction "DGND15_H9") (pintype "bidirectional"))
      (node (ref "IC1") (pin "J10") (pinfunction "DGND23_J10") (pintype "bidirectional"))
      (node (ref "IC1") (pin "J11") (pinfunction "DGND24_J11") (pintype "bidirectional"))
      (node (ref "IC1") (pin "J19") (pinfunction "DGND25_J19") (pintype "bidirectional"))
      (node (ref "IC1") (pin "J20") (pinfunction "DGND26_J20") (pintype "bidirectional"))
      (node (ref "IC1") (pin "J6") (pinfunction "DGND19_J6") (pintype "bidirectional"))
      (node (ref "IC1") (pin "J7") (pinfunction "DGND20_J7") (pintype "bidirectional"))
      (node (ref "IC1") (pin "J8") (pinfunction "DGND21_J8") (pintype "bidirectional"))
      (node (ref "IC1") (pin "J9") (pinfunction "DGND22_J9") (pintype "bidirectional"))
      (node (ref "IC1") (pin "K10") (pinfunction "DGND29_K10") (pintype "bidirectional"))
      (node (ref "IC1") (pin "K11") (pinfunction "DGND30_K11") (pintype "bidirectional"))
      (node (ref "IC1") (pin "K19") (pinfunction "DGND31_K19") (pintype "bidirectional"))
      (node (ref "IC1") (pin "K7") (pinfunction "DGND27_K7") (pintype "bidirectional"))
      (node (ref "IC1") (pin "K9") (pinfunction "DGND28_K9") (pintype "bidirectional"))
      (node (ref "IC1") (pin "L10") (pinfunction "DGND32_L10") (pintype "bidirectional"))
      (node (ref "IC1") (pin "L11") (pinfunction "DGND33_L11") (pintype "bidirectional"))
      (node (ref "IC1") (pin "L12") (pinfunction "DGND34_L12") (pintype "bidirectional"))
      (node (ref "IC1") (pin "L13") (pinfunction "DGND35_L13") (pintype "bidirectional"))
      (node (ref "IC1") (pin "L19") (pinfunction "DGND36_L19") (pintype "bidirectional"))
      (node (ref "IC1") (pin "M10") (pinfunction "DGND42_M10") (pintype "bidirectional"))
      (node (ref "IC1") (pin "M12") (pinfunction "DGND43_M12") (pintype "bidirectional"))
      (node (ref "IC1") (pin "M14") (pinfunction "DGND44_M14") (pintype "bidirectional"))
      (node (ref "IC1") (pin "M19") (pinfunction "DGND45_M19") (pintype "bidirectional"))
      (node (ref "IC1") (pin "M6") (pinfunction "DGND38_M6") (pintype "bidirectional"))
      (node (ref "IC1") (pin "M7") (pinfunction "DGND39_M7") (pintype "bidirectional"))
      (node (ref "IC1") (pin "M8") (pinfunction "DGND40_M8") (pintype "bidirectional"))
      (node (ref "IC1") (pin "M9") (pinfunction "DGND41_M9") (pintype "bidirectional"))
      (node (ref "IC1") (pin "N10") (pinfunction "DGND47_N10") (pintype "bidirectional"))
      (node (ref "IC1") (pin "N11") (pinfunction "DGND48_N11") (pintype "bidirectional"))
      (node (ref "IC1") (pin "N14") (pinfunction "DGND49_N14") (pintype "bidirectional"))
      (node (ref "IC1") (pin "N19") (pinfunction "DGND50_N19") (pintype "bidirectional"))
      (node (ref "IC1") (pin "N20") (pinfunction "DGND51_N20") (pintype "bidirectional"))
      (node (ref "IC1") (pin "N7") (pinfunction "DGND46_N7") (pintype "bidirectional"))
      (node (ref "IC1") (pin "P19") (pinfunction "DGND52_P19") (pintype "bidirectional"))
      (node (ref "IC1") (pin "P20") (pinfunction "DGND53_P20") (pintype "bidirectional"))
      (node (ref "IC1") (pin "R19") (pinfunction "DGND54_R19") (pintype "bidirectional"))
      (node (ref "IC1") (pin "R20") (pinfunction "DGND55_R20") (pintype "bidirectional"))
      (node (ref "IC1") (pin "T19") (pinfunction "DGND56_T19") (pintype "bidirectional"))
      (node (ref "IC1") (pin "T20") (pinfunction "DGND57_T20") (pintype "bidirectional"))
      (node (ref "IC1") (pin "U19") (pinfunction "DGND58_U19") (pintype "bidirectional"))
      (node (ref "IC1") (pin "V1") (pinfunction "DGND59_V1") (pintype "bidirectional"))
      (node (ref "IC1") (pin "V18") (pinfunction "DGND60_V18") (pintype "bidirectional"))
      (node (ref "IC1") (pin "V19") (pinfunction "DGND61_V19") (pintype "bidirectional"))
      (node (ref "IC1") (pin "W10") (pinfunction "DGND70_W10") (pintype "bidirectional"))
      (node (ref "IC1") (pin "W11") (pinfunction "DGND71_W11") (pintype "bidirectional"))
      (node (ref "IC1") (pin "W12") (pinfunction "DGND72_W12") (pintype "bidirectional"))
      (node (ref "IC1") (pin "W13") (pinfunction "DGND73_W13") (pintype "bidirectional"))
      (node (ref "IC1") (pin "W14") (pinfunction "DGND74_W14") (pintype "bidirectional"))
      (node (ref "IC1") (pin "W15") (pinfunction "DGND75_W15") (pintype "bidirectional"))
      (node (ref "IC1") (pin "W16") (pinfunction "DGND76_W16") (pintype "bidirectional"))
      (node (ref "IC1") (pin "W17") (pinfunction "DGND77_W17") (pintype "bidirectional"))
      (node (ref "IC1") (pin "W18") (pinfunction "DGND78_W18") (pintype "bidirectional"))
      (node (ref "IC1") (pin "W19") (pinfunction "DGND79_W19") (pintype "bidirectional"))
      (node (ref "IC1") (pin "W2") (pinfunction "DGND62_W2") (pintype "bidirectional"))
      (node (ref "IC1") (pin "W20") (pinfunction "DGND80_W20") (pintype "bidirectional"))
      (node (ref "IC1") (pin "W3") (pinfunction "DGND63_W3") (pintype "bidirectional"))
      (node (ref "IC1") (pin "W5") (pinfunction "DGND65_W5") (pintype "bidirectional"))
      (node (ref "IC1") (pin "W6") (pinfunction "DGND66_W6") (pintype "bidirectional"))
      (node (ref "IC1") (pin "W7") (pinfunction "DGND67_W7") (pintype "bidirectional"))
      (node (ref "IC1") (pin "W8") (pinfunction "DGND68_W8") (pintype "bidirectional"))
      (node (ref "IC1") (pin "W9") (pinfunction "DGND69_W9") (pintype "bidirectional"))
      (node (ref "IC1") (pin "Y10") (pinfunction "DGND83_Y10") (pintype "bidirectional"))
      (node (ref "IC1") (pin "Y12") (pinfunction "DGND84_Y12") (pintype "bidirectional"))
      (node (ref "IC1") (pin "Y15") (pinfunction "DGND85_Y15") (pintype "bidirectional"))
      (node (ref "IC1") (pin "Y18") (pinfunction "DGND86_Y18") (pintype "bidirectional"))
      (node (ref "IC1") (pin "Y7") (pinfunction "DGND82_Y7") (pintype "bidirectional"))
      (node (ref "IC10") (pin "11") (pinfunction "GND_11") (pintype "bidirectional"))
      (node (ref "IC10") (pin "TP") (pinfunction "TP_TP") (pintype "bidirectional"))
      (node (ref "IC11") (pin "11") (pinfunction "GND_11") (pintype "bidirectional"))
      (node (ref "IC11") (pin "TP") (pinfunction "TP_TP") (pintype "bidirectional"))
      (node (ref "IC12") (pin "1") (pinfunction "GND_1") (pintype "bidirectional"))
      (node (ref "IC12") (pin "9") (pinfunction "THERMAL_9") (pintype "bidirectional"))
      (node (ref "IC13") (pin "4") (pinfunction "GND_4") (pintype "bidirectional"))
      (node (ref "IC14") (pin "4") (pinfunction "GND_4") (pintype "bidirectional"))
      (node (ref "IC15") (pin "4") (pinfunction "GND_4") (pintype "bidirectional"))
      (node (ref "IC17") (pin "1") (pinfunction "1OE#_1") (pintype "bidirectional"))
      (node (ref "IC17") (pin "4") (pinfunction "GND_4") (pintype "bidirectional"))
      (node (ref "IC18") (pin "3") (pinfunction "GND1_3") (pintype "bidirectional"))
      (node (ref "IC18") (pin "6") (pinfunction "GND2_6") (pintype "bidirectional"))
      (node (ref "IC19") (pin "2") (pinfunction "GND_2") (pintype "bidirectional"))
      (node (ref "IC2") (pin "3") (pinfunction "GND_3") (pintype "bidirectional"))
      (node (ref "IC22") (pin "C4") (pinfunction "VSSQ1_C4") (pintype "bidirectional"))
      (node (ref "IC22") (pin "E7") (pinfunction "VSS1_E7") (pintype "bidirectional"))
      (node (ref "IC22") (pin "G5") (pinfunction "VSS2_G5") (pintype "bidirectional"))
      (node (ref "IC22") (pin "H10") (pinfunction "VSS3_H10") (pintype "bidirectional"))
      (node (ref "IC22") (pin "K8") (pinfunction "VSS4_K8") (pintype "bidirectional"))
      (node (ref "IC22") (pin "N2") (pinfunction "VSSQ2_N2") (pintype "bidirectional"))
      (node (ref "IC22") (pin "N5") (pinfunction "VSSQ3_N5") (pintype "bidirectional"))
      (node (ref "IC22") (pin "P4") (pinfunction "VSSQ4_P4") (pintype "bidirectional"))
      (node (ref "IC22") (pin "P6") (pinfunction "VSSQ5_P6") (pintype "bidirectional"))
      (node (ref "IC3") (pin "3") (pinfunction "GND_3") (pintype "bidirectional"))
      (node (ref "IC4") (pin "2") (pinfunction "VSS_2") (pintype "bidirectional"))
      (node (ref "IC7") (pin "3") (pinfunction "GND1_3") (pintype "bidirectional"))
      (node (ref "IC7") (pin "8") (pinfunction "GND2_8") (pintype "bidirectional"))
      (node (ref "IC8") (pin "3") (pinfunction "GND1_3") (pintype "bidirectional"))
      (node (ref "IC8") (pin "8") (pinfunction "GND2_8") (pintype "bidirectional"))
      (node (ref "IC9") (pin "16") (pinfunction "VPC[2]_16") (pintype "bidirectional"))
      (node (ref "IC9") (pin "17") (pinfunction "VPC[1]_17") (pintype "bidirectional"))
      (node (ref "IC9") (pin "18") (pinfunction "VPC[0]_18") (pintype "bidirectional"))
      (node (ref "IC9") (pin "19") (pinfunction "VPP_19") (pintype "bidirectional"))
      (node (ref "IC9") (pin "53") (pinfunction "A0_I2C_53") (pintype "bidirectional"))
      (node (ref "IC9") (pin "54") (pinfunction "A1_I2C_54") (pintype "bidirectional"))
      (node (ref "IC9") (pin "61") (pinfunction "VPA[2]_61") (pintype "bidirectional"))
      (node (ref "IC9") (pin "62") (pinfunction "VPA[1]_62") (pintype "bidirectional"))
      (node (ref "IC9") (pin "63") (pinfunction "VPA[0]_63") (pintype "bidirectional"))
      (node (ref "IC9") (pin "65") (pinfunction "GND.PAD_65") (pintype "bidirectional"))
      (node (ref "IC9") (pin "8") (pinfunction "VPB[1]_8") (pintype "bidirectional"))
      (node (ref "IC9") (pin "9") (pinfunction "VPB[0]_9") (pintype "bidirectional"))
      (node (ref "JTAG1") (pin "10") (pinfunction "GND2_10") (pintype "bidirectional"))
      (node (ref "JTAG1") (pin "12") (pinfunction "GND3_12") (pintype "bidirectional"))
      (node (ref "JTAG1") (pin "16") (pinfunction "GND4_16") (pintype "bidirectional"))
      (node (ref "JTAG1") (pin "20") (pinfunction "GND5_20") (pintype "bidirectional"))
      (node (ref "JTAG1") (pin "4") (pinfunction "TDIS_4") (pintype "bidirectional"))
      (node (ref "JTAG1") (pin "8") (pinfunction "GND1_8") (pintype "bidirectional"))
      (node (ref "MOD1") (pin "1") (pinfunction "GND1_1") (pintype "bidirectional"))
      (node (ref "MOD1") (pin "15") (pinfunction "GND4_15") (pintype "bidirectional"))
      (node (ref "MOD1") (pin "16") (pinfunction "GND5_16") (pintype "bidirectional"))
      (node (ref "MOD1") (pin "17") (pinfunction "GND6_17") (pintype "bidirectional"))
      (node (ref "MOD1") (pin "19") (pinfunction "GND7_19") (pintype "bidirectional"))
      (node (ref "MOD1") (pin "20") (pinfunction "GND8_20") (pintype "bidirectional"))
      (node (ref "MOD1") (pin "23") (pinfunction "GND9_23") (pintype "bidirectional"))
      (node (ref "MOD1") (pin "24") (pinfunction "GND10_24") (pintype "bidirectional"))
      (node (ref "MOD1") (pin "28") (pinfunction "GND11_28") (pintype "bidirectional"))
      (node (ref "MOD1") (pin "29") (pinfunction "GND12_29") (pintype "bidirectional"))
      (node (ref "MOD1") (pin "30") (pinfunction "GND13_30") (pintype "bidirectional"))
      (node (ref "MOD1") (pin "31") (pinfunction "GND14_31") (pintype "bidirectional"))
      (node (ref "MOD1") (pin "33") (pinfunction "GND15_33") (pintype "bidirectional"))
      (node (ref "MOD1") (pin "34") (pinfunction "GND16_34") (pintype "bidirectional"))
      (node (ref "MOD1") (pin "35") (pinfunction "GND17_35") (pintype "bidirectional"))
      (node (ref "MOD1") (pin "37") (pinfunction "GND18_37") (pintype "bidirectional"))
      (node (ref "MOD1") (pin "39") (pinfunction "GND19_39") (pintype "bidirectional"))
      (node (ref "MOD1") (pin "44") (pinfunction "GND20_44") (pintype "bidirectional"))
      (node (ref "MOD1") (pin "45") (pinfunction "GND21_45") (pintype "bidirectional"))
      (node (ref "MOD1") (pin "48") (pinfunction "GND22_48") (pintype "bidirectional"))
      (node (ref "MOD1") (pin "49") (pinfunction "GND23_49") (pintype "bidirectional"))
      (node (ref "MOD1") (pin "54") (pinfunction "GND24_54") (pintype "bidirectional"))
      (node (ref "MOD1") (pin "55") (pinfunction "GND25_55") (pintype "bidirectional"))
      (node (ref "MOD1") (pin "59") (pinfunction "GND26_59") (pintype "bidirectional"))
      (node (ref "MOD1") (pin "61") (pinfunction "GND27_61") (pintype "bidirectional"))
      (node (ref "MOD1") (pin "63") (pinfunction "GND28_63") (pintype "bidirectional"))
      (node (ref "MOD1") (pin "64") (pinfunction "GND29_64") (pintype "bidirectional"))
      (node (ref "MOD1") (pin "7") (pinfunction "GND2_7") (pintype "bidirectional"))
      (node (ref "MOD1") (pin "9") (pinfunction "GND3_9") (pintype "bidirectional"))
      (node (ref "MOD1") (pin "G1") (pinfunction "G1_G1") (pintype "bidirectional"))
      (node (ref "MOD1") (pin "G10") (pinfunction "G10_G10") (pintype "bidirectional"))
      (node (ref "MOD1") (pin "G11") (pinfunction "G11_G11") (pintype "bidirectional"))
      (node (ref "MOD1") (pin "G12") (pinfunction "G12_G12") (pintype "bidirectional"))
      (node (ref "MOD1") (pin "G13") (pinfunction "G13_G13") (pintype "bidirectional"))
      (node (ref "MOD1") (pin "G14") (pinfunction "G14_G14") (pintype "bidirectional"))
      (node (ref "MOD1") (pin "G15") (pinfunction "G15_G15") (pintype "bidirectional"))
      (node (ref "MOD1") (pin "G16") (pinfunction "G16_G16") (pintype "bidirectional"))
      (node (ref "MOD1") (pin "G17") (pinfunction "G17_G17") (pintype "bidirectional"))
      (node (ref "MOD1") (pin "G18") (pinfunction "G18_G18") (pintype "bidirectional"))
      (node (ref "MOD1") (pin "G19") (pinfunction "G19_G19") (pintype "bidirectional"))
      (node (ref "MOD1") (pin "G2") (pinfunction "G2_G2") (pintype "bidirectional"))
      (node (ref "MOD1") (pin "G20") (pinfunction "G20_G20") (pintype "bidirectional"))
      (node (ref "MOD1") (pin "G21") (pinfunction "G21_G21") (pintype "bidirectional"))
      (node (ref "MOD1") (pin "G22") (pinfunction "G22_G22") (pintype "bidirectional"))
      (node (ref "MOD1") (pin "G23") (pinfunction "G23_G23") (pintype "bidirectional"))
      (node (ref "MOD1") (pin "G24") (pinfunction "G24_G24") (pintype "bidirectional"))
      (node (ref "MOD1") (pin "G25") (pinfunction "G25_G25") (pintype "bidirectional"))
      (node (ref "MOD1") (pin "G26") (pinfunction "G26_G26") (pintype "bidirectional"))
      (node (ref "MOD1") (pin "G27") (pinfunction "G27_G27") (pintype "bidirectional"))
      (node (ref "MOD1") (pin "G28") (pinfunction "G28_G28") (pintype "bidirectional"))
      (node (ref "MOD1") (pin "G29") (pinfunction "G29_G29") (pintype "bidirectional"))
      (node (ref "MOD1") (pin "G3") (pinfunction "G3_G3") (pintype "bidirectional"))
      (node (ref "MOD1") (pin "G30") (pinfunction "G30_G30") (pintype "bidirectional"))
      (node (ref "MOD1") (pin "G31") (pinfunction "G31_G31") (pintype "bidirectional"))
      (node (ref "MOD1") (pin "G32") (pinfunction "G32_G32") (pintype "bidirectional"))
      (node (ref "MOD1") (pin "G33") (pinfunction "G33_G33") (pintype "bidirectional"))
      (node (ref "MOD1") (pin "G34") (pinfunction "G34_G34") (pintype "bidirectional"))
      (node (ref "MOD1") (pin "G35") (pinfunction "G35_G35") (pintype "bidirectional"))
      (node (ref "MOD1") (pin "G36") (pinfunction "G36_G36") (pintype "bidirectional"))
      (node (ref "MOD1") (pin "G4") (pinfunction "G4_G4") (pintype "bidirectional"))
      (node (ref "MOD1") (pin "G5") (pinfunction "G5_G5") (pintype "bidirectional"))
      (node (ref "MOD1") (pin "G6") (pinfunction "G6_G6") (pintype "bidirectional"))
      (node (ref "MOD1") (pin "G7") (pinfunction "G7_G7") (pintype "bidirectional"))
      (node (ref "MOD1") (pin "G8") (pinfunction "G8_G8") (pintype "bidirectional"))
      (node (ref "MOD1") (pin "G9") (pinfunction "G9_G9") (pintype "bidirectional"))
      (node (ref "OSC1") (pin "2") (pinfunction "GND_2") (pintype "bidirectional"))
      (node (ref "OSC2") (pin "2") (pinfunction "GND_2") (pintype "bidirectional"))
      (node (ref "POWER") (pin "1") (pinfunction "1_1") (pintype "bidirectional"))
      (node (ref "POWER") (pin "2") (pinfunction "2_2") (pintype "bidirectional"))
      (node (ref "R10") (pin "2") (pinfunction "2_2") (pintype "passive"))
      (node (ref "R106") (pin "2") (pinfunction "2_2") (pintype "passive"))
      (node (ref "R108") (pin "2") (pinfunction "2_2") (pintype "passive"))
      (node (ref "R109") (pin "2") (pinfunction "2_2") (pintype "passive"))
      (node (ref "R11") (pin "2") (pinfunction "2_2") (pintype "passive"))
      (node (ref "R114") (pin "1") (pinfunction "1_1") (pintype "passive"))
      (node (ref "R119") (pin "2") (pinfunction "2_2") (pintype "passive"))
      (node (ref "R123") (pin "2") (pinfunction "2_2") (pintype "passive"))
      (node (ref "R17") (pin "1") (pinfunction "1_1") (pintype "passive"))
      (node (ref "R19") (pin "2") (pinfunction "2_2") (pintype "passive"))
      (node (ref "R22") (pin "2") (pinfunction "2_2") (pintype "passive"))
      (node (ref "R24") (pin "1") (pinfunction "1_1") (pintype "passive"))
      (node (ref "R27") (pin "2") (pinfunction "2_2") (pintype "passive"))
      (node (ref "R52") (pin "2") (pinfunction "2_2") (pintype "passive"))
      (node (ref "R55") (pin "1") (pinfunction "1_1") (pintype "passive"))
      (node (ref "R57") (pin "1") (pinfunction "1_1") (pintype "passive"))
      (node (ref "R61") (pin "1") (pinfunction "1_1") (pintype "passive"))
      (node (ref "R63") (pin "1") (pinfunction "1_1") (pintype "passive"))
      (node (ref "R65") (pin "1") (pinfunction "1_1") (pintype "passive"))
      (node (ref "R67") (pin "1") (pinfunction "1_1") (pintype "passive"))
      (node (ref "R69") (pin "1") (pinfunction "1_1") (pintype "passive"))
      (node (ref "R71") (pin "1") (pinfunction "1_1") (pintype "passive"))
      (node (ref "R73") (pin "1") (pinfunction "1_1") (pintype "passive"))
      (node (ref "R75") (pin "1") (pinfunction "1_1") (pintype "passive"))
      (node (ref "R85") (pin "1") (pinfunction "1_1") (pintype "passive"))
      (node (ref "R87") (pin "1") (pinfunction "1_1") (pintype "passive"))
      (node (ref "R94") (pin "2") (pinfunction "2_2") (pintype "passive"))
      (node (ref "R95") (pin "2") (pinfunction "2_2") (pintype "passive"))
      (node (ref "RESET") (pin "1") (pinfunction "1_1") (pintype "bidirectional"))
      (node (ref "RESET") (pin "2") (pinfunction "2_2") (pintype "bidirectional"))
      (node (ref "S2") (pin "3") (pinfunction "3_3") (pintype "bidirectional"))
      (node (ref "S2") (pin "4") (pinfunction "4_4") (pintype "bidirectional"))
      (node (ref "T3") (pin "S") (pinfunction "S_S") (pintype "bidirectional"))
      (node (ref "T4") (pin "S") (pinfunction "S_S") (pintype "bidirectional"))
      (node (ref "TP5") (pin "P$1") (pinfunction "TP_P$1") (pintype "bidirectional"))
      (node (ref "USR0") (pin "K") (pinfunction "K_K") (pintype "passive"))
      (node (ref "USR1") (pin "K") (pinfunction "K_K") (pintype "passive"))
      (node (ref "USR2") (pin "K") (pinfunction "K_K") (pintype "passive"))
      (node (ref "USR3") (pin "K") (pinfunction "K_K") (pintype "passive"))
      (node (ref "X1") (pin "1") (pinfunction "1_1") (pintype "passive"))
      (node (ref "X12") (pin "OUT") (pinfunction "OUT_OUT") (pintype "bidirectional"))
      (node (ref "X2") (pin "6") (pinfunction "VSS_6") (pintype "bidirectional"))
      (node (ref "X2") (pin "GND") (pinfunction "GND_GND") (pintype "bidirectional"))
      (node (ref "X3") (pin "4") (pinfunction "GND_4") (pintype "bidirectional"))
      (node (ref "X4") (pin "GND") (pinfunction "GND_GND") (pintype "input"))
      (node (ref "X5") (pin "10") (pinfunction "TMDS.DATA0.SHIELD_10") (pintype "bidirectional"))
      (node (ref "X5") (pin "13") (pinfunction "TMDS.CLOCK.SHIELD_13") (pintype "bidirectional"))
      (node (ref "X5") (pin "16") (pinfunction "DDC/CEC.GND_16") (pintype "bidirectional"))
      (node (ref "X5") (pin "4") (pinfunction "TMDS.DATA2.SHIELD_4") (pintype "bidirectional"))
      (node (ref "X5") (pin "7") (pinfunction "TMDS.DATA1.SHIELD_7") (pintype "bidirectional"))
      (node (ref "X8") (pin "1") (pinfunction "1_1") (pintype "passive"))
      (node (ref "X8") (pin "2") (pinfunction "2_2") (pintype "passive"))
      (node (ref "X9") (pin "1") (pinfunction "1_1") (pintype "passive"))
      (node (ref "X9") (pin "2") (pinfunction "2_2") (pintype "passive"))
      (node (ref "X9") (pin "43") (pinfunction "43_43") (pintype "passive"))
      (node (ref "X9") (pin "44") (pinfunction "44_44") (pintype "passive"))
      (node (ref "X9") (pin "45") (pinfunction "45_45") (pintype "passive"))
      (node (ref "X9") (pin "46") (pinfunction "46_46") (pintype "passive"))
    )
    (net (code "182") (name "HDMI_1V8") (class "Default")
      (node (ref "C50") (pin "1") (pinfunction "1_1") (pintype "passive"))
      (node (ref "C51") (pin "1") (pinfunction "1_1") (pintype "passive"))
      (node (ref "C52") (pin "1") (pinfunction "1_1") (pintype "passive"))
      (node (ref "C53") (pin "1") (pinfunction "1_1") (pintype "passive"))
      (node (ref "C54") (pin "1") (pinfunction "1_1") (pintype "passive"))
      (node (ref "C55") (pin "1") (pinfunction "1_1") (pintype "passive"))
      (node (ref "C56") (pin "1") (pinfunction "1_1") (pintype "passive"))
      (node (ref "C57") (pin "1") (pinfunction "1_1") (pintype "passive"))
      (node (ref "FB2") (pin "2") (pinfunction "P$2_2") (pintype "bidirectional"))
      (node (ref "IC9") (pin "14") (pinfunction "VDDD1(IO)(1V8)_14") (pintype "bidirectional"))
      (node (ref "IC9") (pin "29") (pinfunction "VDDDC2_29") (pintype "bidirectional"))
      (node (ref "IC9") (pin "35") (pinfunction "VDDA(1V8)_35") (pintype "bidirectional"))
      (node (ref "IC9") (pin "36") (pinfunction "VDDA1(TX)(1V8)_36") (pintype "bidirectional"))
      (node (ref "IC9") (pin "41") (pinfunction "VDDA2(TX)(1V8)_41") (pintype "bidirectional"))
      (node (ref "IC9") (pin "46") (pinfunction "VDDA3(TX)(1V8)_46") (pintype "bidirectional"))
      (node (ref "IC9") (pin "47") (pinfunction "VDDA1(PLL)(1V8)_47") (pintype "bidirectional"))
      (node (ref "IC9") (pin "48") (pinfunction "VDDA2(PLL)(1V8)_48") (pintype "bidirectional"))
      (node (ref "IC9") (pin "5") (pinfunction "VDDDC1_5") (pintype "bidirectional"))
      (node (ref "IC9") (pin "55") (pinfunction "VDDD2(IO)(1V8)_55") (pintype "bidirectional"))
    )
    (net (code "183") (name "Net-(ANT1-PadSIG)") (class "Default")
      (node (ref "ANT1") (pin "SIG") (pinfunction "SIG_SIG") (pintype "bidirectional"))
      (node (ref "C46") (pin "1") (pinfunction "1_1") (pintype "passive"))
    )
    (net (code "184") (name "Net-(ANT2-PadSIG)") (class "Default")
      (node (ref "ANT2") (pin "SIG") (pinfunction "SIG_SIG") (pintype "bidirectional"))
      (node (ref "C60") (pin "1") (pinfunction "1_1") (pintype "passive"))
    )
    (net (code "185") (name "Net-(BT-PadA)") (class "Default")
      (node (ref "BT") (pin "A") (pinfunction "A_A") (pintype "passive"))
      (node (ref "R124") (pin "1") (pinfunction "1_1") (pintype "passive"))
    )
    (net (code "186") (name "Net-(BT-PadK)") (class "Default")
      (node (ref "BT") (pin "K") (pinfunction "K_K") (pintype "passive"))
      (node (ref "T4") (pin "D") (pinfunction "D_D") (pintype "bidirectional"))
    )
    (net (code "187") (name "Net-(D1-ANODE)") (class "Default")
      (node (ref "D1") (pin "A") (pinfunction "ANODE_A") (pintype "bidirectional"))
      (node (ref "R120") (pin "2") (pinfunction "2_2") (pintype "passive"))
    )
    (net (code "188") (name "Net-(FB3-P$1)") (class "Default")
      (node (ref "C58") (pin "1") (pinfunction "1_1") (pintype "passive"))
      (node (ref "FB3") (pin "1") (pinfunction "P$1_1") (pintype "bidirectional"))
      (node (ref "FB4") (pin "1") (pinfunction "P$1_1") (pintype "bidirectional"))
      (node (ref "IC12") (pin "6") (pinfunction "OUT1_6") (pintype "bidirectional"))
      (node (ref "IC12") (pin "7") (pinfunction "OUT2_7") (pintype "bidirectional"))
      (node (ref "IC12") (pin "8") (pinfunction "OUT3_8") (pintype "bidirectional"))
      (node (ref "IC15") (pin "6") (pinfunction "VBUS_6") (pintype "bidirectional"))
    )
    (net (code "189") (name "Net-(FB3-P$2)") (class "Default")
      (node (ref "FB3") (pin "2") (pinfunction "P$2_2") (pintype "bidirectional"))
      (node (ref "X3") (pin "1") (pinfunction "VBUS_1") (pintype "bidirectional"))
    )
    (net (code "190") (name "Net-(IC1A-(EMMC_RSTN)GPIO1_20)") (class "Default")
      (node (ref "IC1") (pin "R14") (pinfunction "(EMMC_RSTN)GPIO1_20_R14") (pintype "bidirectional"))
      (node (ref "IC3") (pin "2") (pinfunction "A_2") (pintype "bidirectional"))
    )
    (net (code "191") (name "Net-(IC1A-CLKOUT1)") (class "Default")
      (node (ref "IC1") (pin "A15") (pinfunction "CLKOUT1_A15") (pintype "bidirectional"))
      (node (ref "R9") (pin "1") (pinfunction "1_1") (pintype "passive"))
    )
    (net (code "192") (name "Net-(IC1A-CLKOUT2)") (class "Default")
      (node (ref "IC1") (pin "D14") (pinfunction "CLKOUT2_D14") (pintype "bidirectional"))
      (node (ref "R15") (pin "2") (pinfunction "2_2") (pintype "passive"))
    )
    (net (code "193") (name "Net-(IC1A-DGND0)") (class "Default")
      (node (ref "C3") (pin "2") (pinfunction "2_2") (pintype "passive"))
      (node (ref "C4") (pin "2") (pinfunction "2_2") (pintype "passive"))
      (node (ref "IC1") (pin "L20") (pinfunction "DGND0_L20") (pintype "bidirectional"))
    )
    (net (code "194") (name "Net-(IC1A-DGND1)") (class "Default")
      (node (ref "C5") (pin "2") (pinfunction "2_2") (pintype "passive"))
      (node (ref "C6") (pin "2") (pinfunction "2_2") (pintype "passive"))
      (node (ref "IC1") (pin "G20") (pinfunction "DGND1_G20") (pintype "bidirectional"))
    )
    (net (code "195") (name "Net-(IC1A-GPIO3_20)") (class "Default")
      (node (ref "IC1") (pin "D13") (pinfunction "GPIO3_20_D13") (pintype "bidirectional"))
      (node (ref "R14") (pin "2") (pinfunction "2_2") (pintype "passive"))
    )
    (net (code "196") (name "Net-(IC1A-OSC0_IN)") (class "Default")
      (node (ref "C3") (pin "1") (pinfunction "1_1") (pintype "passive"))
      (node (ref "IC1") (pin "M20") (pinfunction "OSC0_IN_M20") (pintype "bidirectional"))
      (node (ref "Q4") (pin "2") (pinfunction "P$2_2") (pintype "passive"))
      (node (ref "R8") (pin "2") (pinfunction "2_2") (pintype "passive"))
    )
    (net (code "197") (name "Net-(IC1A-OSC0_OUT)") (class "Default")
      (node (ref "C4") (pin "1") (pinfunction "1_1") (pintype "passive"))
      (node (ref "IC1") (pin "K20") (pinfunction "OSC0_OUT_K20") (pintype "bidirectional"))
      (node (ref "Q4") (pin "1") (pinfunction "P$1_1") (pintype "passive"))
      (node (ref "R8") (pin "1") (pinfunction "1_1") (pintype "passive"))
    )
    (net (code "198") (name "Net-(IC1A-OSC1_IN)") (class "Default")
      (node (ref "C5") (pin "1") (pinfunction "1_1") (pintype "passive"))
      (node (ref "IC1") (pin "H20") (pinfunction "OSC1_IN_H20") (pintype "bidirectional"))
      (node (ref "Q2") (pin "P$1") (pinfunction "P$1_P$1") (pintype "passive"))
      (node (ref "R56") (pin "2") (pinfunction "2_2") (pintype "passive"))
    )
    (net (code "199") (name "Net-(IC1A-OSC1_OUT)") (class "Default")
      (node (ref "C6") (pin "1") (pinfunction "1_1") (pintype "passive"))
      (node (ref "IC1") (pin "F20") (pinfunction "OSC1_OUT_F20") (pintype "bidirectional"))
      (node (ref "Q2") (pin "P$2") (pinfunction "P$2_P$2") (pintype "passive"))
      (node (ref "R56") (pin "1") (pinfunction "1_1") (pintype "passive"))
    )
    (net (code "200") (name "Net-(IC1B-AIN7)") (class "Default")
      (node (ref "IC1") (pin "C9") (pinfunction "AIN7_C9") (pintype "bidirectional"))
      (node (ref "R21") (pin "2") (pinfunction "2_2") (pintype "passive"))
      (node (ref "R22") (pin "1") (pinfunction "1_1") (pintype "passive"))
    )
    (net (code "201") (name "Net-(IC1B-GPIO0_7)") (class "Default")
      (node (ref "IC1") (pin "C18") (pinfunction "GPIO0_7_C18") (pintype "bidirectional"))
      (node (ref "R36") (pin "2") (pinfunction "2_2") (pintype "passive"))
    )
    (net (code "202") (name "Net-(IC1B-GPIO3_18)") (class "Default")
      (node (ref "IC1") (pin "B12") (pinfunction "GPIO3_18_B12") (pintype "bidirectional"))
      (node (ref "R38") (pin "2") (pinfunction "2_2") (pintype "passive"))
    )
    (net (code "203") (name "Net-(IC1B-USB0_VBUS)") (class "Default")
      (node (ref "IC1") (pin "P15") (pinfunction "USB0_VBUS_P15") (pintype "bidirectional"))
      (node (ref "R26") (pin "1") (pinfunction "1_1") (pintype "passive"))
    )
    (net (code "204") (name "Net-(IC1B-USB1_ID)") (class "Default")
      (node (ref "IC1") (pin "P17") (pinfunction "USB1_ID_P17") (pintype "bidirectional"))
      (node (ref "R27") (pin "1") (pinfunction "1_1") (pintype "passive"))
    )
    (net (code "205") (name "Net-(IC1C-PMIC_POWER_EN)") (class "Default")
      (node (ref "IC1") (pin "C6") (pinfunction "PMIC_POWER_EN_C6") (pintype "bidirectional"))
      (node (ref "IC1") (pin "D19") (pinfunction "PWR_EN_D19") (pintype "bidirectional"))
    )
    (net (code "206") (name "Net-(IC1E-RTC_KALDO_ENN)") (class "Default")
      (node (ref "IC1") (pin "B4") (pinfunction "RTC_KALDO_ENN_B4") (pintype "bidirectional"))
      (node (ref "R24") (pin "2") (pinfunction "2_2") (pintype "passive"))
    )
    (net (code "207") (name "Net-(IC3-Y)") (class "Default")
      (node (ref "IC3") (pin "4") (pinfunction "Y_4") (pintype "bidirectional"))
      (node (ref "R29") (pin "2") (pinfunction "2_2") (pintype "passive"))
    )
    (net (code "208") (name "Net-(IC4-WP)") (class "Default")
      (node (ref "IC4") (pin "5") (pinfunction "WP_5") (pintype "bidirectional"))
      (node (ref "R40") (pin "2") (pinfunction "2_2") (pintype "passive"))
      (node (ref "TP1") (pin "P$1") (pinfunction "TP_P$1") (pintype "bidirectional"))
    )
    (net (code "209") (name "Net-(IC5-C)") (class "Default")
      (node (ref "IC5") (pin "2") (pinfunction "C_2") (pintype "passive"))
      (node (ref "R44") (pin "2") (pinfunction "2_2") (pintype "passive"))
      (node (ref "R45") (pin "1") (pinfunction "1_1") (pintype "passive"))
      (node (ref "T1") (pin "B") (pinfunction "B_B") (pintype "passive"))
    )
    (net (code "210") (name "Net-(IC5-FB)") (class "Default")
      (node (ref "IC5") (pin "1") (pinfunction "FB_1") (pintype "passive"))
      (node (ref "R45") (pin "2") (pinfunction "2_2") (pintype "passive"))
      (node (ref "R46") (pin "2") (pinfunction "2_2") (pintype "passive"))
      (node (ref "R47") (pin "1") (pinfunction "1_1") (pintype "passive"))
    )
    (net (code "211") (name "Net-(IC6-C)") (class "Default")
      (node (ref "IC6") (pin "2") (pinfunction "C_2") (pintype "passive"))
      (node (ref "R48") (pin "2") (pinfunction "2_2") (pintype "passive"))
      (node (ref "R49") (pin "1") (pinfunction "1_1") (pintype "passive"))
      (node (ref "T2") (pin "B") (pinfunction "B_B") (pintype "passive"))
    )
    (net (code "212") (name "Net-(IC6-FB)") (class "Default")
      (node (ref "IC6") (pin "1") (pinfunction "FB_1") (pintype "passive"))
      (node (ref "R49") (pin "2") (pinfunction "2_2") (pintype "passive"))
      (node (ref "R50") (pin "2") (pinfunction "2_2") (pintype "passive"))
      (node (ref "R51") (pin "1") (pinfunction "1_1") (pintype "passive"))
    )
    (net (code "213") (name "Net-(IC9-DSCL)") (class "Default")
      (node (ref "IC9") (pin "33") (pinfunction "DSCL_33") (pintype "bidirectional"))
      (node (ref "R115") (pin "2") (pinfunction "2_2") (pintype "passive"))
      (node (ref "X5") (pin "17") (pinfunction "SCL_17") (pintype "bidirectional"))
    )
    (net (code "214") (name "Net-(IC9-DSDA)") (class "Default")
      (node (ref "IC9") (pin "32") (pinfunction "DSDA_32") (pintype "bidirectional"))
      (node (ref "R118") (pin "2") (pinfunction "2_2") (pintype "passive"))
      (node (ref "X5") (pin "18") (pinfunction "SDA_18") (pintype "bidirectional"))
    )
    (net (code "215") (name "Net-(IC10-B1)") (class "Default")
      (node (ref "IC10") (pin "20") (pinfunction "B1_20") (pintype "bidirectional"))
      (node (ref "R130") (pin "2") (pinfunction "2_2") (pintype "passive"))
    )
    (net (code "216") (name "Net-(IC10-B2)") (class "Default")
      (node (ref "IC10") (pin "18") (pinfunction "B2_18") (pintype "bidirectional"))
      (node (ref "R129") (pin "2") (pinfunction "2_2") (pintype "passive"))
    )
    (net (code "217") (name "Net-(IC10-B3)") (class "Default")
      (node (ref "IC10") (pin "17") (pinfunction "B3_17") (pintype "bidirectional"))
      (node (ref "R128") (pin "2") (pinfunction "2_2") (pintype "passive"))
    )
    (net (code "218") (name "Net-(IC10-B4)") (class "Default")
      (node (ref "IC10") (pin "16") (pinfunction "B4_16") (pintype "bidirectional"))
      (node (ref "R127") (pin "2") (pinfunction "2_2") (pintype "passive"))
    )
    (net (code "219") (name "Net-(IC10-B5)") (class "Default")
      (node (ref "IC10") (pin "15") (pinfunction "B5_15") (pintype "bidirectional"))
      (node (ref "R126") (pin "2") (pinfunction "2_2") (pintype "passive"))
    )
    (net (code "220") (name "Net-(IC10-B6)") (class "Default")
      (node (ref "IC10") (pin "14") (pinfunction "B6_14") (pintype "bidirectional"))
      (node (ref "R86") (pin "2") (pinfunction "2_2") (pintype "passive"))
    )
    (net (code "221") (name "Net-(IC10-OE)") (class "Default")
      (node (ref "IC10") (pin "10") (pinfunction "OE_10") (pintype "bidirectional"))
      (node (ref "IC11") (pin "10") (pinfunction "OE_10") (pintype "bidirectional"))
      (node (ref "R106") (pin "1") (pinfunction "1_1") (pintype "passive"))
      (node (ref "R131") (pin "1") (pinfunction "1_1") (pintype "passive"))
    )
    (net (code "222") (name "Net-(IC11-B2)") (class "Default")
      (node (ref "IC11") (pin "18") (pinfunction "B2_18") (pintype "bidirectional"))
      (node (ref "R136") (pin "2") (pinfunction "2_2") (pintype "passive"))
    )
    (net (code "223") (name "Net-(IC11-B3)") (class "Default")
      (node (ref "IC11") (pin "17") (pinfunction "B3_17") (pintype "bidirectional"))
      (node (ref "R135") (pin "2") (pinfunction "2_2") (pintype "passive"))
    )
    (net (code "224") (name "Net-(IC11-B8)") (class "Default")
      (node (ref "IC11") (pin "12") (pinfunction "B8_12") (pintype "bidirectional"))
      (node (ref "R134") (pin "2") (pinfunction "2_2") (pintype "passive"))
    )
    (net (code "225") (name "Net-(IC13-Q)") (class "Default")
      (node (ref "IC13") (pin "5") (pinfunction "Q_5") (pintype "bidirectional"))
      (node (ref "R113") (pin "1") (pinfunction "1_1") (pintype "passive"))
    )
    (net (code "226") (name "Net-(IC18-ADJ)") (class "Default")
      (node (ref "IC18") (pin "5") (pinfunction "ADJ_5") (pintype "bidirectional"))
      (node (ref "R93") (pin "2") (pinfunction "2_2") (pintype "passive"))
      (node (ref "R94") (pin "1") (pinfunction "1_1") (pintype "passive"))
    )
    (net (code "227") (name "Net-(IC18-SHDN#)") (class "Default")
      (node (ref "IC18") (pin "1") (pinfunction "SHDN#_1") (pintype "bidirectional"))
      (node (ref "R89") (pin "2") (pinfunction "2_2") (pintype "passive"))
      (node (ref "R97") (pin "2") (pinfunction "2_2") (pintype "passive"))
    )
    (net (code "228") (name "Net-(IC22-VDDI)") (class "Default")
      (node (ref "C69") (pin "1") (pinfunction "1_1") (pintype "passive"))
      (node (ref "C7") (pin "1") (pinfunction "1_1") (pintype "passive"))
      (node (ref "IC22") (pin "C2") (pinfunction "VDDI_C2") (pintype "bidirectional"))
    )
    (net (code "229") (name "Net-(MOD1-BT_AUD_CLK)") (class "Default")
      (node (ref "MOD1") (pin "60") (pinfunction "BT_AUD_CLK_60") (pintype "bidirectional"))
      (node (ref "TP19") (pin "TP") (pinfunction "TP_TP") (pintype "input"))
    )
    (net (code "230") (name "Net-(MOD1-BT_AUD_FSYNC)") (class "Default")
      (node (ref "MOD1") (pin "58") (pinfunction "BT_AUD_FSYNC_58") (pintype "bidirectional"))
      (node (ref "TP18") (pin "TP") (pinfunction "TP_TP") (pintype "input"))
    )
    (net (code "231") (name "Net-(MOD1-BT_AUD_IN)") (class "Default")
      (node (ref "MOD1") (pin "56") (pinfunction "BT_AUD_IN_56") (pintype "bidirectional"))
      (node (ref "TP16") (pin "TP") (pinfunction "TP_TP") (pintype "input"))
    )
    (net (code "232") (name "Net-(MOD1-BT_AUD_OUT)") (class "Default")
      (node (ref "MOD1") (pin "57") (pinfunction "BT_AUD_OUT_57") (pintype "bidirectional"))
      (node (ref "TP17") (pin "TP") (pinfunction "TP_TP") (pintype "input"))
    )
    (net (code "233") (name "Net-(MOD1-BT_HCI_CTS)") (class "Default")
      (node (ref "MOD1") (pin "51") (pinfunction "BT_HCI_CTS_51") (pintype "bidirectional"))
      (node (ref "R141") (pin "1") (pinfunction "1_1") (pintype "passive"))
    )
    (net (code "234") (name "Net-(MOD1-BT_HCI_RTS)") (class "Default")
      (node (ref "MOD1") (pin "50") (pinfunction "BT_HCI_RTS_50") (pintype "bidirectional"))
      (node (ref "R140") (pin "1") (pinfunction "1_1") (pintype "passive"))
    )
    (net (code "235") (name "Net-(MOD1-BT_HCI_RX)") (class "Default")
      (node (ref "MOD1") (pin "53") (pinfunction "BT_HCI_RX_53") (pintype "bidirectional"))
      (node (ref "R143") (pin "1") (pinfunction "1_1") (pintype "passive"))
    )
    (net (code "236") (name "Net-(MOD1-BT_HCI_TX)") (class "Default")
      (node (ref "MOD1") (pin "52") (pinfunction "BT_HCI_TX_52") (pintype "bidirectional"))
      (node (ref "R142") (pin "1") (pinfunction "1_1") (pintype "passive"))
    )
    (net (code "237") (name "Net-(MOD1-BT_UART_DBG)") (class "Default")
      (node (ref "MOD1") (pin "43") (pinfunction "BT_UART_DBG_43") (pintype "bidirectional"))
      (node (ref "TP15") (pin "TP") (pinfunction "TP_TP") (pintype "input"))
    )
    (net (code "238") (name "Net-(MOD1-GPIO1)") (class "Default")
      (node (ref "MOD1") (pin "27") (pinfunction "GPIO1_27") (pintype "bidirectional"))
      (node (ref "TP13") (pin "TP") (pinfunction "TP_TP") (pintype "input"))
    )
    (net (code "239") (name "Net-(MOD1-GPIO2)") (class "Default")
      (node (ref "MOD1") (pin "26") (pinfunction "GPIO2_26") (pintype "bidirectional"))
      (node (ref "TP12") (pin "TP") (pinfunction "TP_TP") (pintype "input"))
    )
    (net (code "240") (name "Net-(MOD1-RF_ANT1)") (class "Default")
      (node (ref "C46") (pin "2") (pinfunction "2_2") (pintype "passive"))
      (node (ref "MOD1") (pin "32") (pinfunction "RF_ANT1_32") (pintype "bidirectional"))
    )
    (net (code "241") (name "Net-(MOD1-RF_ANT2)") (class "Default")
      (node (ref "C60") (pin "2") (pinfunction "2_2") (pintype "passive"))
      (node (ref "MOD1") (pin "18") (pinfunction "RF_ANT2_18") (pintype "bidirectional"))
    )
    (net (code "242") (name "Net-(MOD1-WLAN_IRQ)") (class "Default")
      (node (ref "MOD1") (pin "14") (pinfunction "WLAN_IRQ_14") (pintype "bidirectional"))
      (node (ref "R111") (pin "2") (pinfunction "2_2") (pintype "passive"))
      (node (ref "R60") (pin "1") (pinfunction "1_1") (pintype "passive"))
    )
    (net (code "243") (name "Net-(MOD1-WL_SDIO_CLK)") (class "Default")
      (node (ref "MOD1") (pin "8") (pinfunction "WL_SDIO_CLK_8") (pintype "bidirectional"))
      (node (ref "R64") (pin "1") (pinfunction "1_1") (pintype "passive"))
    )
    (net (code "244") (name "Net-(MOD1-WL_SDIO_CMD)") (class "Default")
      (node (ref "MOD1") (pin "6") (pinfunction "WL_SDIO_CMD_6") (pintype "bidirectional"))
      (node (ref "R62") (pin "1") (pinfunction "1_1") (pintype "passive"))
    )
    (net (code "245") (name "Net-(MOD1-WL_SDIO_D0)") (class "Default")
      (node (ref "MOD1") (pin "10") (pinfunction "WL_SDIO_D0_10") (pintype "bidirectional"))
      (node (ref "R66") (pin "1") (pinfunction "1_1") (pintype "passive"))
    )
    (net (code "246") (name "Net-(MOD1-WL_SDIO_D1)") (class "Default")
      (node (ref "MOD1") (pin "11") (pinfunction "WL_SDIO_D1_11") (pintype "bidirectional"))
      (node (ref "R68") (pin "1") (pinfunction "1_1") (pintype "passive"))
    )
    (net (code "247") (name "Net-(MOD1-WL_SDIO_D2)") (class "Default")
      (node (ref "MOD1") (pin "12") (pinfunction "WL_SDIO_D2_12") (pintype "bidirectional"))
      (node (ref "R70") (pin "1") (pinfunction "1_1") (pintype "passive"))
    )
    (net (code "248") (name "Net-(MOD1-WL_SDIO_D3)") (class "Default")
      (node (ref "MOD1") (pin "13") (pinfunction "WL_SDIO_D3_13") (pintype "bidirectional"))
      (node (ref "R72") (pin "1") (pinfunction "1_1") (pintype "passive"))
    )
    (net (code "249") (name "Net-(MOD1-WL_UART_DBG)") (class "Default")
      (node (ref "MOD1") (pin "42") (pinfunction "WL_UART_DBG_42") (pintype "bidirectional"))
      (node (ref "TP14") (pin "TP") (pinfunction "TP_TP") (pintype "input"))
    )
    (net (code "250") (name "Net-(OSC1-OUT)") (class "Default")
      (node (ref "OSC1") (pin "3") (pinfunction "OUT_3") (pintype "bidirectional"))
      (node (ref "R110") (pin "1") (pinfunction "1_1") (pintype "passive"))
    )
    (net (code "251") (name "Net-(OSC2-EN)") (class "Default")
      (node (ref "OSC2") (pin "1") (pinfunction "EN_1") (pintype "bidirectional"))
      (node (ref "R90") (pin "2") (pinfunction "2_2") (pintype "passive"))
    )
    (net (code "252") (name "Net-(PWR-PadK)") (class "Default")
      (node (ref "PWR") (pin "K") (pinfunction "K_K") (pintype "passive"))
      (node (ref "R55") (pin "2") (pinfunction "2_2") (pintype "passive"))
    )
    (net (code "253") (name "Net-(R88-Pad2)") (class "Default")
      (node (ref "R88") (pin "2") (pinfunction "2_2") (pintype "passive"))
      (node (ref "S2") (pin "1") (pinfunction "1_1") (pintype "bidirectional"))
      (node (ref "S2") (pin "2") (pinfunction "2_2") (pintype "bidirectional"))
    )
    (net (code "254") (name "Net-(R92-Pad1)") (class "Default")
      (node (ref "R92") (pin "1") (pinfunction "1_1") (pintype "passive"))
      (node (ref "USR3") (pin "A") (pinfunction "A_A") (pintype "passive"))
    )
    (net (code "255") (name "Net-(R96-Pad1)") (class "Default")
      (node (ref "R96") (pin "1") (pinfunction "1_1") (pintype "passive"))
      (node (ref "USR2") (pin "A") (pinfunction "A_A") (pintype "passive"))
    )
    (net (code "256") (name "Net-(R100-Pad1)") (class "Default")
      (node (ref "R100") (pin "1") (pinfunction "1_1") (pintype "passive"))
      (node (ref "USR1") (pin "A") (pinfunction "A_A") (pintype "passive"))
    )
    (net (code "257") (name "Net-(R104-Pad1)") (class "Default")
      (node (ref "R104") (pin "1") (pinfunction "1_1") (pintype "passive"))
      (node (ref "USR0") (pin "A") (pinfunction "A_A") (pintype "passive"))
    )
    (net (code "258") (name "Net-(R125-Pad1)") (class "Default")
      (node (ref "R125") (pin "1") (pinfunction "1_1") (pintype "passive"))
      (node (ref "WL") (pin "A") (pinfunction "A_A") (pintype "passive"))
    )
    (net (code "259") (name "Net-(T3-PadD)") (class "Default")
      (node (ref "T3") (pin "D") (pinfunction "D_D") (pintype "bidirectional"))
      (node (ref "WL") (pin "K") (pinfunction "K_K") (pintype "passive"))
    )
    (net (code "260") (name "SYS_5V") (class "Default")
      (node (ref "C62") (pin "+") (pinfunction "+_+") (pintype "passive"))
      (node (ref "D2") (pin "A") (pinfunction "A_A") (pintype "bidirectional"))
      (node (ref "F1") (pin "2") (pinfunction "2_2") (pintype "passive"))
      (node (ref "IC1") (pin "W4") (pinfunction "SYS_5V_1_W4") (pintype "bidirectional"))
      (node (ref "IC1") (pin "Y4") (pinfunction "SYS_5V_2_Y4") (pintype "bidirectional"))
      (node (ref "IC12") (pin "2") (pinfunction "IN1_2") (pintype "bidirectional"))
      (node (ref "IC12") (pin "3") (pinfunction "IN2_3") (pintype "bidirectional"))
      (node (ref "X9") (pin "7") (pinfunction "7_7") (pintype "passive"))
      (node (ref "X9") (pin "8") (pinfunction "8_8") (pintype "passive"))
    )
    (net (code "261") (name "USB_DC") (class "Default")
      (node (ref "C59") (pin "1") (pinfunction "1_1") (pintype "passive"))
      (node (ref "D4") (pin "A") (pinfunction "A_A") (pintype "bidirectional"))
      (node (ref "IC1") (pin "Y8") (pinfunction "VIN_USB_0_Y8") (pintype "bidirectional"))
      (node (ref "IC1") (pin "Y9") (pinfunction "VIN_USB_1_Y9") (pintype "bidirectional"))
      (node (ref "IC14") (pin "6") (pinfunction "VBUS_6") (pintype "bidirectional"))
      (node (ref "R26") (pin "2") (pinfunction "2_2") (pintype "passive"))
      (node (ref "X4") (pin "VBUS") (pinfunction "VBUS_VBUS") (pintype "input"))
    )
    (net (code "262") (name "VDDS_DDR") (class "Default")
      (node (ref "IC1") (pin "H5") (pinfunction "VDDS_DDR4_H5") (pintype "bidirectional"))
    )
    (net (code "263") (name "VDDS_PLL") (class "Default")
      (node (ref "IC1") (pin "E7") (pinfunction "VDD_PLL1_E7") (pintype "bidirectional"))
    )
    (net (code "264") (name "VDD_1V8") (class "Default")
      (node (ref "FB2") (pin "1") (pinfunction "P$1_1") (pintype "bidirectional"))
      (node (ref "IC1") (pin "D10") (pinfunction "VDD_1V84_D10") (pintype "bidirectional"))
      (node (ref "IC1") (pin "E9") (pinfunction "VDD_1V83_E9") (pintype "bidirectional"))
      (node (ref "IC1") (pin "N16") (pinfunction "VDD_1V8_0_N16") (pintype "bidirectional"))
      (node (ref "IC1") (pin "R16") (pinfunction "VDD_1V8_1_R16") (pintype "bidirectional"))
      (node (ref "IC2") (pin "5") (pinfunction "VCC_5") (pintype "bidirectional"))
      (node (ref "IC5") (pin "3") (pinfunction "A_3") (pintype "passive"))
      (node (ref "IC6") (pin "3") (pinfunction "A_3") (pintype "passive"))
      (node (ref "R47") (pin "2") (pinfunction "2_2") (pintype "passive"))
      (node (ref "R51") (pin "2") (pinfunction "2_2") (pintype "passive"))
      (node (ref "T1") (pin "C") (pinfunction "C_C") (pintype "passive"))
      (node (ref "T2") (pin "C") (pinfunction "C_C") (pintype "passive"))
    )
    (net (code "265") (name "VDD_3V3A") (class "Default")
      (node (ref "IC1") (pin "N5") (pinfunction "VDD_3V3A18_N5") (pintype "bidirectional"))
      (node (ref "IC1") (pin "P5") (pinfunction "VDD_3V3A17_P5") (pintype "bidirectional"))
      (node (ref "IC1") (pin "P6") (pinfunction "VDD_3V3A16_P6") (pintype "bidirectional"))
      (node (ref "IC1") (pin "P7") (pinfunction "VDD_3V3A15_P7") (pintype "bidirectional"))
      (node (ref "R44") (pin "1") (pinfunction "1_1") (pintype "passive"))
      (node (ref "R46") (pin "1") (pinfunction "1_1") (pintype "passive"))
      (node (ref "T1") (pin "E") (pinfunction "E_E") (pintype "passive"))
    )
    (net (code "266") (name "VDD_3V3AUX") (class "Default")
      (node (ref "IC1") (pin "Y11") (pinfunction "VDD_3V3AUX_Y11") (pintype "bidirectional"))
      (node (ref "PWR") (pin "A") (pinfunction "A_A") (pintype "passive"))
    )
    (net (code "267") (name "VDD_3V3B") (class "Default")
      (node (ref "C1") (pin "1") (pinfunction "1_1") (pintype "passive"))
      (node (ref "C12") (pin "1") (pinfunction "1_1") (pintype "passive"))
      (node (ref "C13") (pin "1") (pinfunction "1_1") (pintype "passive"))
      (node (ref "C14") (pin "1") (pinfunction "1_1") (pintype "passive"))
      (node (ref "C15") (pin "1") (pinfunction "1_1") (pintype "passive"))
      (node (ref "C17") (pin "1") (pinfunction "1_1") (pintype "passive"))
      (node (ref "C18") (pin "1") (pinfunction "1_1") (pintype "passive"))
      (node (ref "C2") (pin "1") (pinfunction "1_1") (pintype "passive"))
      (node (ref "C22") (pin "1") (pinfunction "1_1") (pintype "passive"))
      (node (ref "C47") (pin "1") (pinfunction "1_1") (pintype "passive"))
      (node (ref "C48") (pin "1") (pinfunction "1_1") (pintype "passive"))
      (node (ref "C49") (pin "1") (pinfunction "1_1") (pintype "passive"))
      (node (ref "C9") (pin "1") (pinfunction "1_1") (pintype "passive"))
      (node (ref "IC1") (pin "U20") (pinfunction "VDD_3V3B_0_U20") (pintype "bidirectional"))
      (node (ref "IC1") (pin "V20") (pinfunction "VDD_3V3B_1_V20") (pintype "bidirectional"))
      (node (ref "IC13") (pin "6") (pinfunction "CLR#_6") (pintype "bidirectional"))
      (node (ref "IC13") (pin "7") (pinfunction "PRE#_7") (pintype "bidirectional"))
      (node (ref "IC13") (pin "8") (pinfunction "VCC_8") (pintype "bidirectional"))
      (node (ref "IC17") (pin "7") (pinfunction "2OE_7") (pintype "bidirectional"))
      (node (ref "IC17") (pin "8") (pinfunction "VCC_8") (pintype "bidirectional"))
      (node (ref "IC22") (pin "C6") (pinfunction "VCCQ1_C6") (pintype "bidirectional"))
      (node (ref "IC22") (pin "E6") (pinfunction "VCC1_E6") (pintype "bidirectional"))
      (node (ref "IC22") (pin "F5") (pinfunction "VCC2_F5") (pintype "bidirectional"))
      (node (ref "IC22") (pin "J10") (pinfunction "VCC3_J10") (pintype "bidirectional"))
      (node (ref "IC22") (pin "K9") (pinfunction "VCC4_K9") (pintype "bidirectional"))
      (node (ref "IC22") (pin "M4") (pinfunction "VCCQ2_M4") (pintype "bidirectional"))
      (node (ref "IC22") (pin "N4") (pinfunction "VCCQ3_N4") (pintype "bidirectional"))
      (node (ref "IC22") (pin "P3") (pinfunction "VCCQ4_P3") (pintype "bidirectional"))
      (node (ref "IC22") (pin "P5") (pinfunction "VCCQ5_P5") (pintype "bidirectional"))
      (node (ref "IC3") (pin "5") (pinfunction "VCC_5") (pintype "bidirectional"))
      (node (ref "IC4") (pin "4") (pinfunction "VCC_4") (pintype "bidirectional"))
      (node (ref "JTAG1") (pin "5") (pinfunction "TVDD_5") (pintype "bidirectional"))
      (node (ref "OSC1") (pin "4") (pinfunction "VCC_4") (pintype "bidirectional"))
      (node (ref "R1") (pin "2") (pinfunction "2_2") (pintype "passive"))
      (node (ref "R12") (pin "2") (pinfunction "2_2") (pintype "passive"))
      (node (ref "R120") (pin "1") (pinfunction "1_1") (pintype "passive"))
      (node (ref "R121") (pin "1") (pinfunction "1_1") (pintype "passive"))
      (node (ref "R122") (pin "1") (pinfunction "1_1") (pintype "passive"))
      (node (ref "R13") (pin "2") (pinfunction "2_2") (pintype "passive"))
      (node (ref "R16") (pin "2") (pinfunction "2_2") (pintype "passive"))
      (node (ref "R18") (pin "2") (pinfunction "2_2") (pintype "passive"))
      (node (ref "R2") (pin "2") (pinfunction "2_2") (pintype "passive"))
      (node (ref "R20") (pin "2") (pinfunction "2_2") (pintype "passive"))
      (node (ref "R21") (pin "1") (pinfunction "1_1") (pintype "passive"))
      (node (ref "R23") (pin "2") (pinfunction "2_2") (pintype "passive"))
      (node (ref "R25") (pin "2") (pinfunction "2_2") (pintype "passive"))
      (node (ref "R28") (pin "2") (pinfunction "2_2") (pintype "passive"))
      (node (ref "R3") (pin "2") (pinfunction "2_2") (pintype "passive"))
      (node (ref "R30") (pin "2") (pinfunction "2_2") (pintype "passive"))
      (node (ref "R31") (pin "2") (pinfunction "2_2") (pintype "passive"))
      (node (ref "R32") (pin "1") (pinfunction "1_1") (pintype "passive"))
      (node (ref "R33") (pin "2") (pinfunction "2_2") (pintype "passive"))
      (node (ref "R4") (pin "2") (pinfunction "2_2") (pintype "passive"))
      (node (ref "R40") (pin "1") (pinfunction "1_1") (pintype "passive"))
      (node (ref "R41") (pin "1") (pinfunction "1_1") (pintype "passive"))
      (node (ref "R42") (pin "1") (pinfunction "1_1") (pintype "passive"))
      (node (ref "R43") (pin "1") (pinfunction "1_1") (pintype "passive"))
      (node (ref "R48") (pin "1") (pinfunction "1_1") (pintype "passive"))
      (node (ref "R5") (pin "2") (pinfunction "2_2") (pintype "passive"))
      (node (ref "R50") (pin "1") (pinfunction "1_1") (pintype "passive"))
      (node (ref "R53") (pin "1") (pinfunction "1_1") (pintype "passive"))
      (node (ref "R58") (pin "2") (pinfunction "2_2") (pintype "passive"))
      (node (ref "R6") (pin "2") (pinfunction "2_2") (pintype "passive"))
      (node (ref "R7") (pin "2") (pinfunction "2_2") (pintype "passive"))
      (node (ref "R76") (pin "2") (pinfunction "2_2") (pintype "passive"))
      (node (ref "R78") (pin "2") (pinfunction "2_2") (pintype "passive"))
      (node (ref "R80") (pin "2") (pinfunction "2_2") (pintype "passive"))
      (node (ref "R82") (pin "2") (pinfunction "2_2") (pintype "passive"))
      (node (ref "R89") (pin "1") (pinfunction "1_1") (pintype "passive"))
      (node (ref "T2") (pin "E") (pinfunction "E_E") (pintype "passive"))
      (node (ref "X2") (pin "4") (pinfunction "VDD_4") (pintype "bidirectional"))
      (node (ref "X9") (pin "3") (pinfunction "3_3") (pintype "passive"))
      (node (ref "X9") (pin "4") (pinfunction "4_4") (pintype "passive"))
    )
    (net (code "268") (name "VDD_5V") (class "Default")
      (node (ref "D3") (pin "A") (pinfunction "A_A") (pintype "bidirectional"))
      (node (ref "IC1") (pin "Y5") (pinfunction "VIN_5V_0_Y5") (pintype "bidirectional"))
      (node (ref "IC1") (pin "Y6") (pinfunction "VIN_5V_1_Y6") (pintype "bidirectional"))
      (node (ref "X12") (pin "IN") (pinfunction "IN_IN") (pintype "bidirectional"))
      (node (ref "X9") (pin "5") (pinfunction "5_5") (pintype "passive"))
      (node (ref "X9") (pin "6") (pinfunction "6_6") (pintype "passive"))
    )
    (net (code "269") (name "VDD_ADC") (class "Default")
      (node (ref "IC1") (pin "A4") (pinfunction "VDD_ADC_1_A4") (pintype "bidirectional"))
      (node (ref "IC1") (pin "A5") (pinfunction "VDD_ADC_0_A5") (pintype "bidirectional"))
      (node (ref "IC1") (pin "B9") (pinfunction "VREFP_ADC_B9") (pintype "bidirectional"))
      (node (ref "IC1") (pin "D8") (pinfunction "VDDA_ADC_D8") (pintype "bidirectional"))
      (node (ref "X9") (pin "32") (pinfunction "32_32") (pintype "passive"))
    )
    (net (code "270") (name "VDD_CORE") (class "Default")
      (node (ref "IC1") (pin "F6") (pinfunction "VDD_CORE1_F6") (pintype "bidirectional"))
    )
    (net (code "271") (name "VDD_MPU") (class "Default")
      (node (ref "IC1") (pin "F10") (pinfunction "VDD_MPU0_F10") (pintype "bidirectional"))
    )
    (net (code "272") (name "VDD_RTC") (class "Default")
      (node (ref "IC1") (pin "N6") (pinfunction "VDD_RTC4_N6") (pintype "bidirectional"))
    )
    (net (code "273") (name "unconnected-(D8-A1-Pad1)") (class "Default")
      (node (ref "D8") (pin "1") (pinfunction "A1_1") (pintype "passive"))
    )
    (net (code "274") (name "unconnected-(FUD1-PadP$1)") (class "Default")
      (node (ref "FUD1") (pin "P$1") (pinfunction "P$1_P$1") (pintype "no_connect"))
    )
    (net (code "275") (name "unconnected-(FUD2-PadP$1)") (class "Default")
      (node (ref "FUD2") (pin "P$1") (pinfunction "P$1_P$1") (pintype "no_connect"))
    )
    (net (code "276") (name "unconnected-(FUD3-PadP$1)") (class "Default")
      (node (ref "FUD3") (pin "P$1") (pinfunction "P$1_P$1") (pintype "no_connect"))
    )
    (net (code "277") (name "unconnected-(FUD4-PadP$1)") (class "Default")
      (node (ref "FUD4") (pin "P$1") (pinfunction "P$1_P$1") (pintype "no_connect"))
    )
    (net (code "278") (name "unconnected-(FUD5-PadP$1)") (class "Default")
      (node (ref "FUD5") (pin "P$1") (pinfunction "P$1_P$1") (pintype "no_connect"))
    )
    (net (code "279") (name "unconnected-(FUD6-PadP$1)") (class "Default")
      (node (ref "FUD6") (pin "P$1") (pinfunction "P$1_P$1") (pintype "no_connect"))
    )
    (net (code "280") (name "unconnected-(IC1B-UART0_CTSN-PadE18)") (class "Default")
      (node (ref "IC1") (pin "E18") (pinfunction "UART0_CTSN_E18") (pintype "bidirectional"))
    )
    (net (code "281") (name "unconnected-(IC1B-USB0_CE-PadM15)") (class "Default")
      (node (ref "IC1") (pin "M15") (pinfunction "USB0_CE_M15") (pintype "bidirectional"))
    )
    (net (code "282") (name "unconnected-(IC1B-USB0_DRVVBUS-PadF16)") (class "Default")
      (node (ref "IC1") (pin "F16") (pinfunction "USB0_DRVVBUS_F16") (pintype "bidirectional"))
    )
    (net (code "283") (name "unconnected-(IC1B-USB1_CE-PadP18)") (class "Default")
      (node (ref "IC1") (pin "P18") (pinfunction "USB1_CE_P18") (pintype "bidirectional"))
    )
    (net (code "284") (name "unconnected-(IC1C-L1_IN-PadY14)") (class "Default")
      (node (ref "IC1") (pin "Y14") (pinfunction "L1_IN_Y14") (pintype "bidirectional"))
    )
    (net (code "285") (name "unconnected-(IC1C-L2_IN-PadY17)") (class "Default")
      (node (ref "IC1") (pin "Y17") (pinfunction "L2_IN_Y17") (pintype "bidirectional"))
    )
    (net (code "286") (name "unconnected-(IC1C-L3_IN-PadY20)") (class "Default")
      (node (ref "IC1") (pin "Y20") (pinfunction "L3_IN_Y20") (pintype "bidirectional"))
    )
    (net (code "287") (name "unconnected-(IC1C-VDDS_DDR-PadY13)") (class "Default")
      (node (ref "IC1") (pin "Y13") (pinfunction "VDDS_DDR_Y13") (pintype "bidirectional"))
    )
    (net (code "288") (name "unconnected-(IC1C-VDD_CORE-PadY19)") (class "Default")
      (node (ref "IC1") (pin "Y19") (pinfunction "VDD_CORE_Y19") (pintype "bidirectional"))
    )
    (net (code "289") (name "unconnected-(IC1C-VDD_MPU-PadY16)") (class "Default")
      (node (ref "IC1") (pin "Y16") (pinfunction "VDD_MPU_Y16") (pintype "bidirectional"))
    )
    (net (code "290") (name "unconnected-(IC1D-NC1-PadB1)") (class "Default")
      (node (ref "IC1") (pin "B1") (pinfunction "NC1_B1") (pintype "bidirectional"))
    )
    (net (code "291") (name "unconnected-(IC1D-NC2-PadB2)") (class "Default")
      (node (ref "IC1") (pin "B2") (pinfunction "NC2_B2") (pintype "bidirectional"))
    )
    (net (code "292") (name "unconnected-(IC1D-NC3-PadB3)") (class "Default")
      (node (ref "IC1") (pin "B3") (pinfunction "NC3_B3") (pintype "bidirectional"))
    )
    (net (code "293") (name "unconnected-(IC1D-NC4-PadC1)") (class "Default")
      (node (ref "IC1") (pin "C1") (pinfunction "NC4_C1") (pintype "bidirectional"))
    )
    (net (code "294") (name "unconnected-(IC1D-NC5-PadC2)") (class "Default")
      (node (ref "IC1") (pin "C2") (pinfunction "NC5_C2") (pintype "bidirectional"))
    )
    (net (code "295") (name "unconnected-(IC1D-NC6-PadC3)") (class "Default")
      (node (ref "IC1") (pin "C3") (pinfunction "NC6_C3") (pintype "bidirectional"))
    )
    (net (code "296") (name "unconnected-(IC1D-NC12-PadC4)") (class "Default")
      (node (ref "IC1") (pin "C4") (pinfunction "NC12_C4") (pintype "bidirectional"))
    )
    (net (code "297") (name "unconnected-(IC1D-NC20-PadD1)") (class "Default")
      (node (ref "IC1") (pin "D1") (pinfunction "NC20_D1") (pintype "bidirectional"))
    )
    (net (code "298") (name "unconnected-(IC1D-NC21-PadD2)") (class "Default")
      (node (ref "IC1") (pin "D2") (pinfunction "NC21_D2") (pintype "bidirectional"))
    )
    (net (code "299") (name "unconnected-(IC1D-NC22-PadD3)") (class "Default")
      (node (ref "IC1") (pin "D3") (pinfunction "NC22_D3") (pintype "bidirectional"))
    )
    (net (code "300") (name "unconnected-(IC1D-NC23-PadD4)") (class "Default")
      (node (ref "IC1") (pin "D4") (pinfunction "NC23_D4") (pintype "bidirectional"))
    )
    (net (code "301") (name "unconnected-(IC1D-NC24-PadD5)") (class "Default")
      (node (ref "IC1") (pin "D5") (pinfunction "NC24_D5") (pintype "bidirectional"))
    )
    (net (code "302") (name "unconnected-(IC1D-NC31-PadE1)") (class "Default")
      (node (ref "IC1") (pin "E1") (pinfunction "NC31_E1") (pintype "bidirectional"))
    )
    (net (code "303") (name "unconnected-(IC1D-NC32-PadE2)") (class "Default")
      (node (ref "IC1") (pin "E2") (pinfunction "NC32_E2") (pintype "bidirectional"))
    )
    (net (code "304") (name "unconnected-(IC1D-NC33-PadE3)") (class "Default")
      (node (ref "IC1") (pin "E3") (pinfunction "NC33_E3") (pintype "bidirectional"))
    )
    (net (code "305") (name "unconnected-(IC1D-NC34-PadE4)") (class "Default")
      (node (ref "IC1") (pin "E4") (pinfunction "NC34_E4") (pintype "bidirectional"))
    )
    (net (code "306") (name "unconnected-(IC1D-NC45-PadF1)") (class "Default")
      (node (ref "IC1") (pin "F1") (pinfunction "NC45_F1") (pintype "bidirectional"))
    )
    (net (code "307") (name "unconnected-(IC1D-NC46-PadF2)") (class "Default")
      (node (ref "IC1") (pin "F2") (pinfunction "NC46_F2") (pintype "bidirectional"))
    )
    (net (code "308") (name "unconnected-(IC1D-NC47-PadF3)") (class "Default")
      (node (ref "IC1") (pin "F3") (pinfunction "NC47_F3") (pintype "bidirectional"))
    )
    (net (code "309") (name "unconnected-(IC1D-NC48-PadF4)") (class "Default")
      (node (ref "IC1") (pin "F4") (pinfunction "NC48_F4") (pintype "bidirectional"))
    )
    (net (code "310") (name "unconnected-(IC1D-NC58-PadG1)") (class "Default")
      (node (ref "IC1") (pin "G1") (pinfunction "NC58_G1") (pintype "bidirectional"))
    )
    (net (code "311") (name "unconnected-(IC1D-NC59-PadG2)") (class "Default")
      (node (ref "IC1") (pin "G2") (pinfunction "NC59_G2") (pintype "bidirectional"))
    )
    (net (code "312") (name "unconnected-(IC1D-NC60-PadG3)") (class "Default")
      (node (ref "IC1") (pin "G3") (pinfunction "NC60_G3") (pintype "bidirectional"))
    )
    (net (code "313") (name "unconnected-(IC1D-NC61-PadG4)") (class "Default")
      (node (ref "IC1") (pin "G4") (pinfunction "NC61_G4") (pintype "bidirectional"))
    )
    (net (code "314") (name "unconnected-(IC1D-NC68-PadH1)") (class "Default")
      (node (ref "IC1") (pin "H1") (pinfunction "NC68_H1") (pintype "bidirectional"))
    )
    (net (code "315") (name "unconnected-(IC1D-NC69-PadH2)") (class "Default")
      (node (ref "IC1") (pin "H2") (pinfunction "NC69_H2") (pintype "bidirectional"))
    )
    (net (code "316") (name "unconnected-(IC1D-NC70-PadH3)") (class "Default")
      (node (ref "IC1") (pin "H3") (pinfunction "NC70_H3") (pintype "bidirectional"))
    )
    (net (code "317") (name "unconnected-(IC1D-NC71-PadH4)") (class "Default")
      (node (ref "IC1") (pin "H4") (pinfunction "NC71_H4") (pintype "bidirectional"))
    )
    (net (code "318") (name "unconnected-(IC1D-NC76-PadJ1)") (class "Default")
      (node (ref "IC1") (pin "J1") (pinfunction "NC76_J1") (pintype "bidirectional"))
    )
    (net (code "319") (name "unconnected-(IC1D-NC77-PadJ2)") (class "Default")
      (node (ref "IC1") (pin "J2") (pinfunction "NC77_J2") (pintype "bidirectional"))
    )
    (net (code "320") (name "unconnected-(IC1D-NC78-PadJ3)") (class "Default")
      (node (ref "IC1") (pin "J3") (pinfunction "NC78_J3") (pintype "bidirectional"))
    )
    (net (code "321") (name "unconnected-(IC1D-NC79-PadJ4)") (class "Default")
      (node (ref "IC1") (pin "J4") (pinfunction "NC79_J4") (pintype "bidirectional"))
    )
    (net (code "322") (name "unconnected-(IC1D-NC84-PadK1)") (class "Default")
      (node (ref "IC1") (pin "K1") (pinfunction "NC84_K1") (pintype "bidirectional"))
    )
    (net (code "323") (name "unconnected-(IC1D-NC85-PadK2)") (class "Default")
      (node (ref "IC1") (pin "K2") (pinfunction "NC85_K2") (pintype "bidirectional"))
    )
    (net (code "324") (name "unconnected-(IC1D-NC86-PadK3)") (class "Default")
      (node (ref "IC1") (pin "K3") (pinfunction "NC86_K3") (pintype "bidirectional"))
    )
    (net (code "325") (name "unconnected-(IC1D-NC87-PadK4)") (class "Default")
      (node (ref "IC1") (pin "K4") (pinfunction "NC87_K4") (pintype "bidirectional"))
    )
    (net (code "326") (name "unconnected-(IC1D-NC94-PadL1)") (class "Default")
      (node (ref "IC1") (pin "L1") (pinfunction "NC94_L1") (pintype "bidirectional"))
    )
    (net (code "327") (name "unconnected-(IC1D-NC95-PadL2)") (class "Default")
      (node (ref "IC1") (pin "L2") (pinfunction "NC95_L2") (pintype "bidirectional"))
    )
    (net (code "328") (name "unconnected-(IC1D-NC96-PadL3)") (class "Default")
      (node (ref "IC1") (pin "L3") (pinfunction "NC96_L3") (pintype "bidirectional"))
    )
    (net (code "329") (name "unconnected-(IC1D-NC97-PadL4)") (class "Default")
      (node (ref "IC1") (pin "L4") (pinfunction "NC97_L4") (pintype "bidirectional"))
    )
    (net (code "330") (name "unconnected-(IC1D-NC104-PadM1)") (class "Default")
      (node (ref "IC1") (pin "M1") (pinfunction "NC104_M1") (pintype "bidirectional"))
    )
    (net (code "331") (name "unconnected-(IC1D-NC105-PadM2)") (class "Default")
      (node (ref "IC1") (pin "M2") (pinfunction "NC105_M2") (pintype "bidirectional"))
    )
    (net (code "332") (name "unconnected-(IC1D-NC106-PadM3)") (class "Default")
      (node (ref "IC1") (pin "M3") (pinfunction "NC106_M3") (pintype "bidirectional"))
    )
    (net (code "333") (name "unconnected-(IC1D-NC107-PadM4)") (class "Default")
      (node (ref "IC1") (pin "M4") (pinfunction "NC107_M4") (pintype "bidirectional"))
    )
    (net (code "334") (name "unconnected-(IC1D-NC111-PadN1)") (class "Default")
      (node (ref "IC1") (pin "N1") (pinfunction "NC111_N1") (pintype "bidirectional"))
    )
    (net (code "335") (name "unconnected-(IC1D-NC112-PadN2)") (class "Default")
      (node (ref "IC1") (pin "N2") (pinfunction "NC112_N2") (pintype "bidirectional"))
    )
    (net (code "336") (name "unconnected-(IC1D-NC113-PadN3)") (class "Default")
      (node (ref "IC1") (pin "N3") (pinfunction "NC113_N3") (pintype "bidirectional"))
    )
    (net (code "337") (name "unconnected-(IC1D-NC114-PadN4)") (class "Default")
      (node (ref "IC1") (pin "N4") (pinfunction "NC114_N4") (pintype "bidirectional"))
    )
    (net (code "338") (name "unconnected-(IC1D-NC121-PadP1)") (class "Default")
      (node (ref "IC1") (pin "P1") (pinfunction "NC121_P1") (pintype "bidirectional"))
    )
    (net (code "339") (name "unconnected-(IC1D-NC122-PadP2)") (class "Default")
      (node (ref "IC1") (pin "P2") (pinfunction "NC122_P2") (pintype "bidirectional"))
    )
    (net (code "340") (name "unconnected-(IC1D-NC123-PadP3)") (class "Default")
      (node (ref "IC1") (pin "P3") (pinfunction "NC123_P3") (pintype "bidirectional"))
    )
    (net (code "341") (name "unconnected-(IC1D-NC124-PadP4)") (class "Default")
      (node (ref "IC1") (pin "P4") (pinfunction "NC124_P4") (pintype "bidirectional"))
    )
    (net (code "342") (name "unconnected-(IC1D-NC136-PadU11)") (class "Default")
      (node (ref "IC1") (pin "U11") (pinfunction "NC136_U11") (pintype "bidirectional"))
    )
    (net (code "343") (name "unconnected-(IC1D-NC137-PadV10)") (class "Default")
      (node (ref "IC1") (pin "V10") (pinfunction "NC137_V10") (pintype "bidirectional"))
    )
    (net (code "344") (name "unconnected-(IC1D-NC138-PadV11)") (class "Default")
      (node (ref "IC1") (pin "V11") (pinfunction "NC138_V11") (pintype "bidirectional"))
    )
    (net (code "345") (name "unconnected-(IC1E-CAP_VBB_MPU-PadC10)") (class "Default")
      (node (ref "IC1") (pin "C10") (pinfunction "CAP_VBB_MPU_C10") (pintype "bidirectional"))
    )
    (net (code "346") (name "unconnected-(IC1E-CAP_VDD_RTC-PadD6)") (class "Default")
      (node (ref "IC1") (pin "D6") (pinfunction "CAP_VDD_RTC_D6") (pintype "bidirectional"))
    )
    (net (code "347") (name "unconnected-(IC1E-CAP_VDD_SRAM_COR-PadD9)") (class "Default")
      (node (ref "IC1") (pin "D9") (pinfunction "CAP_VDD_SRAM_COR_D9") (pintype "bidirectional"))
    )
    (net (code "348") (name "unconnected-(IC1E-CAP_VDD_SRAM_MPU-PadD11)") (class "Default")
      (node (ref "IC1") (pin "D11") (pinfunction "CAP_VDD_SRAM_MPU_D11") (pintype "bidirectional"))
    )
    (net (code "349") (name "unconnected-(IC1E-TESTOUT-PadA3)") (class "Default")
      (node (ref "IC1") (pin "A3") (pinfunction "TESTOUT_A3") (pintype "bidirectional"))
    )
    (net (code "350") (name "unconnected-(IC1E-VDDS_DDR1-PadE5)") (class "Default")
      (node (ref "IC1") (pin "E5") (pinfunction "VDDS_DDR1_E5") (pintype "bidirectional"))
    )
    (net (code "351") (name "unconnected-(IC1E-VDDS_DDR2-PadF5)") (class "Default")
      (node (ref "IC1") (pin "F5") (pinfunction "VDDS_DDR2_F5") (pintype "bidirectional"))
    )
    (net (code "352") (name "unconnected-(IC1E-VDDS_DDR3-PadG5)") (class "Default")
      (node (ref "IC1") (pin "G5") (pinfunction "VDDS_DDR3_G5") (pintype "bidirectional"))
    )
    (net (code "353") (name "unconnected-(IC1E-VDDS_DDR5-PadJ5)") (class "Default")
      (node (ref "IC1") (pin "J5") (pinfunction "VDDS_DDR5_J5") (pintype "bidirectional"))
    )
    (net (code "354") (name "unconnected-(IC1E-VDDS_DDR6-PadK5)") (class "Default")
      (node (ref "IC1") (pin "K5") (pinfunction "VDDS_DDR6_K5") (pintype "bidirectional"))
    )
    (net (code "355") (name "unconnected-(IC1E-VDDS_DDR7-PadL5)") (class "Default")
      (node (ref "IC1") (pin "L5") (pinfunction "VDDS_DDR7_L5") (pintype "bidirectional"))
    )
    (net (code "356") (name "unconnected-(IC1E-VDD_3V3A1-PadF14)") (class "Default")
      (node (ref "IC1") (pin "F14") (pinfunction "VDD_3V3A1_F14") (pintype "bidirectional"))
    )
    (net (code "357") (name "unconnected-(IC1E-VDD_3V3A2-PadG14)") (class "Default")
      (node (ref "IC1") (pin "G14") (pinfunction "VDD_3V3A2_G14") (pintype "bidirectional"))
    )
    (net (code "358") (name "unconnected-(IC1E-VDD_3V3A3-PadH14)") (class "Default")
      (node (ref "IC1") (pin "H14") (pinfunction "VDD_3V3A3_H14") (pintype "bidirectional"))
    )
    (net (code "359") (name "unconnected-(IC1E-VDD_3V3A4-PadJ14)") (class "Default")
      (node (ref "IC1") (pin "J14") (pinfunction "VDD_3V3A4_J14") (pintype "bidirectional"))
    )
    (net (code "360") (name "unconnected-(IC1E-VDD_3V3A5-PadK14)") (class "Default")
      (node (ref "IC1") (pin "K14") (pinfunction "VDD_3V3A5_K14") (pintype "bidirectional"))
    )
    (net (code "361") (name "unconnected-(IC1E-VDD_3V3A6-PadL14)") (class "Default")
      (node (ref "IC1") (pin "L14") (pinfunction "VDD_3V3A6_L14") (pintype "bidirectional"))
    )
    (net (code "362") (name "unconnected-(IC1E-VDD_3V3A7-PadN15)") (class "Default")
      (node (ref "IC1") (pin "N15") (pinfunction "VDD_3V3A7_N15") (pintype "bidirectional"))
    )
    (net (code "363") (name "unconnected-(IC1E-VDD_3V3A8-PadR15)") (class "Default")
      (node (ref "IC1") (pin "R15") (pinfunction "VDD_3V3A8_R15") (pintype "bidirectional"))
    )
    (net (code "364") (name "unconnected-(IC1E-VDD_3V3A9-PadP13)") (class "Default")
      (node (ref "IC1") (pin "P13") (pinfunction "VDD_3V3A9_P13") (pintype "bidirectional"))
    )
    (net (code "365") (name "unconnected-(IC1E-VDD_3V3A10-PadP12)") (class "Default")
      (node (ref "IC1") (pin "P12") (pinfunction "VDD_3V3A10_P12") (pintype "bidirectional"))
    )
    (net (code "366") (name "unconnected-(IC1E-VDD_3V3A11-PadP11)") (class "Default")
      (node (ref "IC1") (pin "P11") (pinfunction "VDD_3V3A11_P11") (pintype "bidirectional"))
    )
    (net (code "367") (name "unconnected-(IC1E-VDD_3V3A12-PadP10)") (class "Default")
      (node (ref "IC1") (pin "P10") (pinfunction "VDD_3V3A12_P10") (pintype "bidirectional"))
    )
    (net (code "368") (name "unconnected-(IC1E-VDD_3V3A14-PadP8)") (class "Default")
      (node (ref "IC1") (pin "P8") (pinfunction "VDD_3V3A14_P8") (pintype "bidirectional"))
    )
    (net (code "369") (name "unconnected-(IC1E-VDD_3V3A19-PadE13)") (class "Default")
      (node (ref "IC1") (pin "E13") (pinfunction "VDD_3V3A19_E13") (pintype "bidirectional"))
    )
    (net (code "370") (name "unconnected-(IC1E-VDD_3V3A20-PadE12)") (class "Default")
      (node (ref "IC1") (pin "E12") (pinfunction "VDD_3V3A20_E12") (pintype "bidirectional"))
    )
    (net (code "371") (name "unconnected-(IC1E-VDD_3V3A21-PadE11)") (class "Default")
      (node (ref "IC1") (pin "E11") (pinfunction "VDD_3V3A21_E11") (pintype "bidirectional"))
    )
    (net (code "372") (name "unconnected-(IC1E-VDD_3V3A22-PadE10)") (class "Default")
      (node (ref "IC1") (pin "E10") (pinfunction "VDD_3V3A22_E10") (pintype "bidirectional"))
    )
    (net (code "373") (name "unconnected-(IC1E-VDD_CORE2-PadF7)") (class "Default")
      (node (ref "IC1") (pin "F7") (pinfunction "VDD_CORE2_F7") (pintype "bidirectional"))
    )
    (net (code "374") (name "unconnected-(IC1E-VDD_CORE3-PadG6)") (class "Default")
      (node (ref "IC1") (pin "G6") (pinfunction "VDD_CORE3_G6") (pintype "bidirectional"))
    )
    (net (code "375") (name "unconnected-(IC1E-VDD_CORE4-PadG7)") (class "Default")
      (node (ref "IC1") (pin "G7") (pinfunction "VDD_CORE4_G7") (pintype "bidirectional"))
    )
    (net (code "376") (name "unconnected-(IC1E-VDD_CORE5-PadG10)") (class "Default")
      (node (ref "IC1") (pin "G10") (pinfunction "VDD_CORE5_G10") (pintype "bidirectional"))
    )
    (net (code "377") (name "unconnected-(IC1E-VDD_CORE6-PadH11)") (class "Default")
      (node (ref "IC1") (pin "H11") (pinfunction "VDD_CORE6_H11") (pintype "bidirectional"))
    )
    (net (code "378") (name "unconnected-(IC1E-VDD_CORE7-PadJ12)") (class "Default")
      (node (ref "IC1") (pin "J12") (pinfunction "VDD_CORE7_J12") (pintype "bidirectional"))
    )
    (net (code "379") (name "unconnected-(IC1E-VDD_CORE8-PadK6)") (class "Default")
      (node (ref "IC1") (pin "K6") (pinfunction "VDD_CORE8_K6") (pintype "bidirectional"))
    )
    (net (code "380") (name "unconnected-(IC1E-VDD_CORE9-PadK8)") (class "Default")
      (node (ref "IC1") (pin "K8") (pinfunction "VDD_CORE9_K8") (pintype "bidirectional"))
    )
    (net (code "381") (name "unconnected-(IC1E-VDD_CORE10-PadK12)") (class "Default")
      (node (ref "IC1") (pin "K12") (pinfunction "VDD_CORE10_K12") (pintype "bidirectional"))
    )
    (net (code "382") (name "unconnected-(IC1E-VDD_CORE11-PadL6)") (class "Default")
      (node (ref "IC1") (pin "L6") (pinfunction "VDD_CORE11_L6") (pintype "bidirectional"))
    )
    (net (code "383") (name "unconnected-(IC1E-VDD_CORE12-PadL7)") (class "Default")
      (node (ref "IC1") (pin "L7") (pinfunction "VDD_CORE12_L7") (pintype "bidirectional"))
    )
    (net (code "384") (name "unconnected-(IC1E-VDD_CORE13-PadL8)") (class "Default")
      (node (ref "IC1") (pin "L8") (pinfunction "VDD_CORE13_L8") (pintype "bidirectional"))
    )
    (net (code "385") (name "unconnected-(IC1E-VDD_CORE14-PadL9)") (class "Default")
      (node (ref "IC1") (pin "L9") (pinfunction "VDD_CORE14_L9") (pintype "bidirectional"))
    )
    (net (code "386") (name "unconnected-(IC1E-VDD_CORE15-PadM11)") (class "Default")
      (node (ref "IC1") (pin "M11") (pinfunction "VDD_CORE15_M11") (pintype "bidirectional"))
    )
    (net (code "387") (name "unconnected-(IC1E-VDD_CORE16-PadM13)") (class "Default")
      (node (ref "IC1") (pin "M13") (pinfunction "VDD_CORE16_M13") (pintype "bidirectional"))
    )
    (net (code "388") (name "unconnected-(IC1E-VDD_CORE17-PadN8)") (class "Default")
      (node (ref "IC1") (pin "N8") (pinfunction "VDD_CORE17_N8") (pintype "bidirectional"))
    )
    (net (code "389") (name "unconnected-(IC1E-VDD_CORE18-PadN9)") (class "Default")
      (node (ref "IC1") (pin "N9") (pinfunction "VDD_CORE18_N9") (pintype "bidirectional"))
    )
    (net (code "390") (name "unconnected-(IC1E-VDD_CORE19-PadN12)") (class "Default")
      (node (ref "IC1") (pin "N12") (pinfunction "VDD_CORE19_N12") (pintype "bidirectional"))
    )
    (net (code "391") (name "unconnected-(IC1E-VDD_CORE20-PadN13)") (class "Default")
      (node (ref "IC1") (pin "N13") (pinfunction "VDD_CORE20_N13") (pintype "bidirectional"))
    )
    (net (code "392") (name "unconnected-(IC1E-VDD_MPU1-PadF11)") (class "Default")
      (node (ref "IC1") (pin "F11") (pinfunction "VDD_MPU1_F11") (pintype "bidirectional"))
    )
    (net (code "393") (name "unconnected-(IC1E-VDD_MPU2-PadF12)") (class "Default")
      (node (ref "IC1") (pin "F12") (pinfunction "VDD_MPU2_F12") (pintype "bidirectional"))
    )
    (net (code "394") (name "unconnected-(IC1E-VDD_MPU3-PadF13)") (class "Default")
      (node (ref "IC1") (pin "F13") (pinfunction "VDD_MPU3_F13") (pintype "bidirectional"))
    )
    (net (code "395") (name "unconnected-(IC1E-VDD_MPU4-PadG13)") (class "Default")
      (node (ref "IC1") (pin "G13") (pinfunction "VDD_MPU4_G13") (pintype "bidirectional"))
    )
    (net (code "396") (name "unconnected-(IC1E-VDD_MPU5-PadH13)") (class "Default")
      (node (ref "IC1") (pin "H13") (pinfunction "VDD_MPU5_H13") (pintype "bidirectional"))
    )
    (net (code "397") (name "unconnected-(IC1E-VDD_MPU6-PadJ13)") (class "Default")
      (node (ref "IC1") (pin "J13") (pinfunction "VDD_MPU6_J13") (pintype "bidirectional"))
    )
    (net (code "398") (name "unconnected-(IC1E-VDD_MPU_MON-PadA2)") (class "Default")
      (node (ref "IC1") (pin "A2") (pinfunction "VDD_MPU_MON_A2") (pintype "bidirectional"))
    )
    (net (code "399") (name "unconnected-(IC1E-VDD_PLL2-PadR10)") (class "Default")
      (node (ref "IC1") (pin "R10") (pinfunction "VDD_PLL2_R10") (pintype "bidirectional"))
    )
    (net (code "400") (name "unconnected-(IC1E-VDD_PLL3-PadR11)") (class "Default")
      (node (ref "IC1") (pin "R11") (pinfunction "VDD_PLL3_R11") (pintype "bidirectional"))
    )
    (net (code "401") (name "unconnected-(IC1E-VDD_PLL4-PadH15)") (class "Default")
      (node (ref "IC1") (pin "H15") (pinfunction "VDD_PLL4_H15") (pintype "bidirectional"))
    )
    (net (code "402") (name "unconnected-(IC1E-VDD_RTC1-PadD7)") (class "Default")
      (node (ref "IC1") (pin "D7") (pinfunction "VDD_RTC1_D7") (pintype "bidirectional"))
    )
    (net (code "403") (name "unconnected-(IC1E-VDD_RTC2-PadE6)") (class "Default")
      (node (ref "IC1") (pin "E6") (pinfunction "VDD_RTC2_E6") (pintype "bidirectional"))
    )
    (net (code "404") (name "unconnected-(IC1E-VDD_RTC3-PadF9)") (class "Default")
      (node (ref "IC1") (pin "F9") (pinfunction "VDD_RTC3_F9") (pintype "bidirectional"))
    )
    (net (code "405") (name "unconnected-(IC1E-VDD_RTC5-PadP14)") (class "Default")
      (node (ref "IC1") (pin "P14") (pinfunction "VDD_RTC5_P14") (pintype "bidirectional"))
    )
    (net (code "406") (name "unconnected-(IC1E-VDD_RTC6-PadK13)") (class "Default")
      (node (ref "IC1") (pin "K13") (pinfunction "VDD_RTC6_K13") (pintype "bidirectional"))
    )
    (net (code "407") (name "unconnected-(IC1E-VDD_RTC7-PadE14)") (class "Default")
      (node (ref "IC1") (pin "E14") (pinfunction "VDD_RTC7_E14") (pintype "bidirectional"))
    )
    (net (code "408") (name "unconnected-(IC1E-VDD_RTC8-PadP9)") (class "Default")
      (node (ref "IC1") (pin "P9") (pinfunction "VDD_RTC8_P9") (pintype "bidirectional"))
    )
    (net (code "409") (name "unconnected-(IC1E-VPP-PadM5)") (class "Default")
      (node (ref "IC1") (pin "M5") (pinfunction "VPP_M5") (pintype "bidirectional"))
    )
    (net (code "410") (name "unconnected-(IC7-NC1-Pad6)") (class "Default")
      (node (ref "IC7") (pin "6") (pinfunction "NC1_6") (pintype "bidirectional"))
    )
    (net (code "411") (name "unconnected-(IC7-NC2-Pad7)") (class "Default")
      (node (ref "IC7") (pin "7") (pinfunction "NC2_7") (pintype "bidirectional"))
    )
    (net (code "412") (name "unconnected-(IC7-NC3-Pad9)") (class "Default")
      (node (ref "IC7") (pin "9") (pinfunction "NC3_9") (pintype "bidirectional"))
    )
    (net (code "413") (name "unconnected-(IC7-NC4-Pad10)") (class "Default")
      (node (ref "IC7") (pin "10") (pinfunction "NC4_10") (pintype "bidirectional"))
    )
    (net (code "414") (name "unconnected-(IC8-NC1-Pad6)") (class "Default")
      (node (ref "IC8") (pin "6") (pinfunction "NC1_6") (pintype "bidirectional"))
    )
    (net (code "415") (name "unconnected-(IC8-NC2-Pad7)") (class "Default")
      (node (ref "IC8") (pin "7") (pinfunction "NC2_7") (pintype "bidirectional"))
    )
    (net (code "416") (name "unconnected-(IC8-NC3-Pad9)") (class "Default")
      (node (ref "IC8") (pin "9") (pinfunction "NC3_9") (pintype "bidirectional"))
    )
    (net (code "417") (name "unconnected-(IC8-NC4-Pad10)") (class "Default")
      (node (ref "IC8") (pin "10") (pinfunction "NC4_10") (pintype "bidirectional"))
    )
    (net (code "418") (name "unconnected-(IC9-AP2-Pad26)") (class "Default")
      (node (ref "IC9") (pin "26") (pinfunction "AP2_26") (pintype "bidirectional"))
    )
    (net (code "419") (name "unconnected-(IC9-AP4-Pad28)") (class "Default")
      (node (ref "IC9") (pin "28") (pinfunction "AP4_28") (pintype "bidirectional"))
    )
    (net (code "420") (name "unconnected-(IC10-A7-Pad8)") (class "Default")
      (node (ref "IC10") (pin "8") (pinfunction "A7_8") (pintype "bidirectional"))
    )
    (net (code "421") (name "unconnected-(IC10-A8-Pad9)") (class "Default")
      (node (ref "IC10") (pin "9") (pinfunction "A8_9") (pintype "bidirectional"))
    )
    (net (code "422") (name "unconnected-(IC10-B7-Pad13)") (class "Default")
      (node (ref "IC10") (pin "13") (pinfunction "B7_13") (pintype "bidirectional"))
    )
    (net (code "423") (name "unconnected-(IC10-B8-Pad12)") (class "Default")
      (node (ref "IC10") (pin "12") (pinfunction "B8_12") (pintype "bidirectional"))
    )
    (net (code "424") (name "unconnected-(IC14-NC-Pad5)") (class "Default")
      (node (ref "IC14") (pin "5") (pinfunction "NC_5") (pintype "bidirectional"))
    )
    (net (code "425") (name "unconnected-(IC15-ID-Pad3)") (class "Default")
      (node (ref "IC15") (pin "3") (pinfunction "ID_3") (pintype "bidirectional"))
    )
    (net (code "426") (name "unconnected-(IC15-NC-Pad5)") (class "Default")
      (node (ref "IC15") (pin "5") (pinfunction "NC_5") (pintype "bidirectional"))
    )
    (net (code "427") (name "unconnected-(IC19-NC{slash}ADJ-Pad4)") (class "Default")
      (node (ref "IC19") (pin "4") (pinfunction "NC/ADJ_4") (pintype "bidirectional"))
    )
    (net (code "428") (name "unconnected-(JTAG1-NC-Pad6)") (class "Default")
      (node (ref "JTAG1") (pin "6") (pinfunction "NC_6") (pintype "bidirectional"))
    )
    (net (code "429") (name "unconnected-(MOD1-GPIO4-Pad25)") (class "Default")
      (node (ref "MOD1") (pin "25") (pinfunction "GPIO4_25") (pintype "bidirectional"))
    )
    (net (code "430") (name "unconnected-(MOD1-GPIO9-Pad3)") (class "Default")
      (node (ref "MOD1") (pin "3") (pinfunction "GPIO9_3") (pintype "bidirectional"))
    )
    (net (code "431") (name "unconnected-(MOD1-GPIO10-Pad4)") (class "Default")
      (node (ref "MOD1") (pin "4") (pinfunction "GPIO10_4") (pintype "bidirectional"))
    )
    (net (code "432") (name "unconnected-(MOD1-GPIO11-Pad2)") (class "Default")
      (node (ref "MOD1") (pin "2") (pinfunction "GPIO11_2") (pintype "bidirectional"))
    )
    (net (code "433") (name "unconnected-(MOD1-GPIO12-Pad5)") (class "Default")
      (node (ref "MOD1") (pin "5") (pinfunction "GPIO12_5") (pintype "bidirectional"))
    )
    (net (code "434") (name "unconnected-(MOD1-RESERVED1-Pad21)") (class "Default")
      (node (ref "MOD1") (pin "21") (pinfunction "RESERVED1_21") (pintype "bidirectional"))
    )
    (net (code "435") (name "unconnected-(MOD1-RESERVED2-Pad22)") (class "Default")
      (node (ref "MOD1") (pin "22") (pinfunction "RESERVED2_22") (pintype "bidirectional"))
    )
    (net (code "436") (name "unconnected-(MOD1-RESERVED3-Pad62)") (class "Default")
      (node (ref "MOD1") (pin "62") (pinfunction "RESERVED3_62") (pintype "bidirectional"))
    )
    (net (code "437") (name "unconnected-(X1-Pad2)") (class "Default")
      (node (ref "X1") (pin "2") (pinfunction "2_2") (pintype "passive"))
    )
    (net (code "438") (name "unconnected-(X1-Pad3)") (class "Default")
      (node (ref "X1") (pin "3") (pinfunction "3_3") (pintype "passive"))
    )
    (net (code "439") (name "unconnected-(X1-Pad6)") (class "Default")
      (node (ref "X1") (pin "6") (pinfunction "6_6") (pintype "passive"))
    )
    (net (code "440") (name "unconnected-(X5-NC-Pad2)") (class "Default")
      (node (ref "X5") (pin "2") (pinfunction "NC_2") (pintype "bidirectional"))
    )
    (net (code "441") (name "unconnected-(X12-PadOUT_CON)") (class "Default")
      (node (ref "X12") (pin "OUT_CON") (pinfunction "OUT_CON_OUT_CON") (pintype "bidirectional"))
    )
  )
)
